# perspection-v1.net
KiCad netlist of a schematic drawn in EAGLE
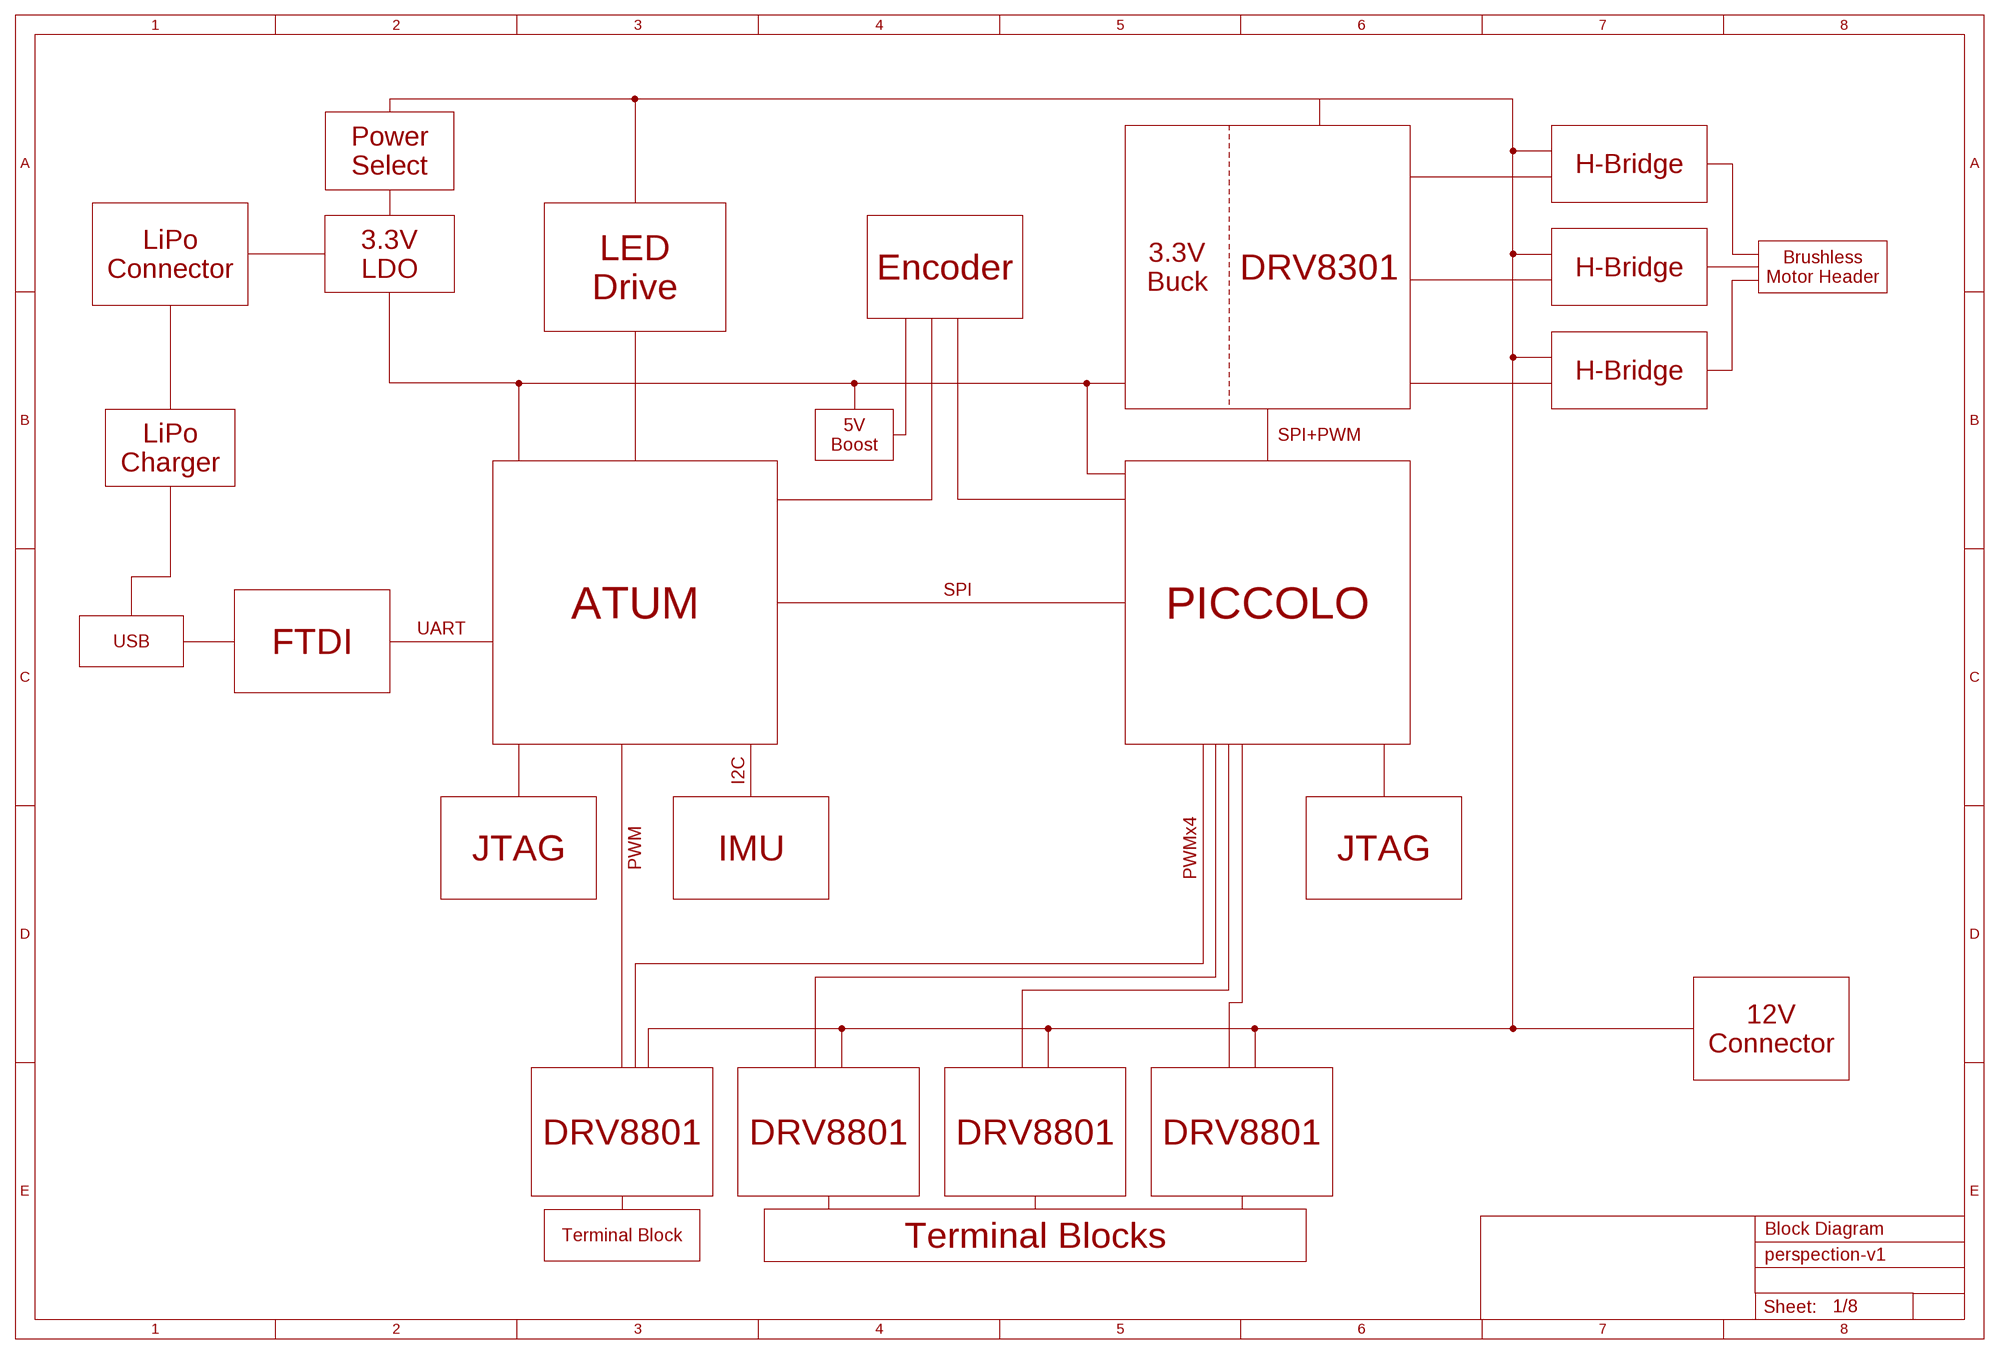
[diagram p0: schematic, sheet 1]
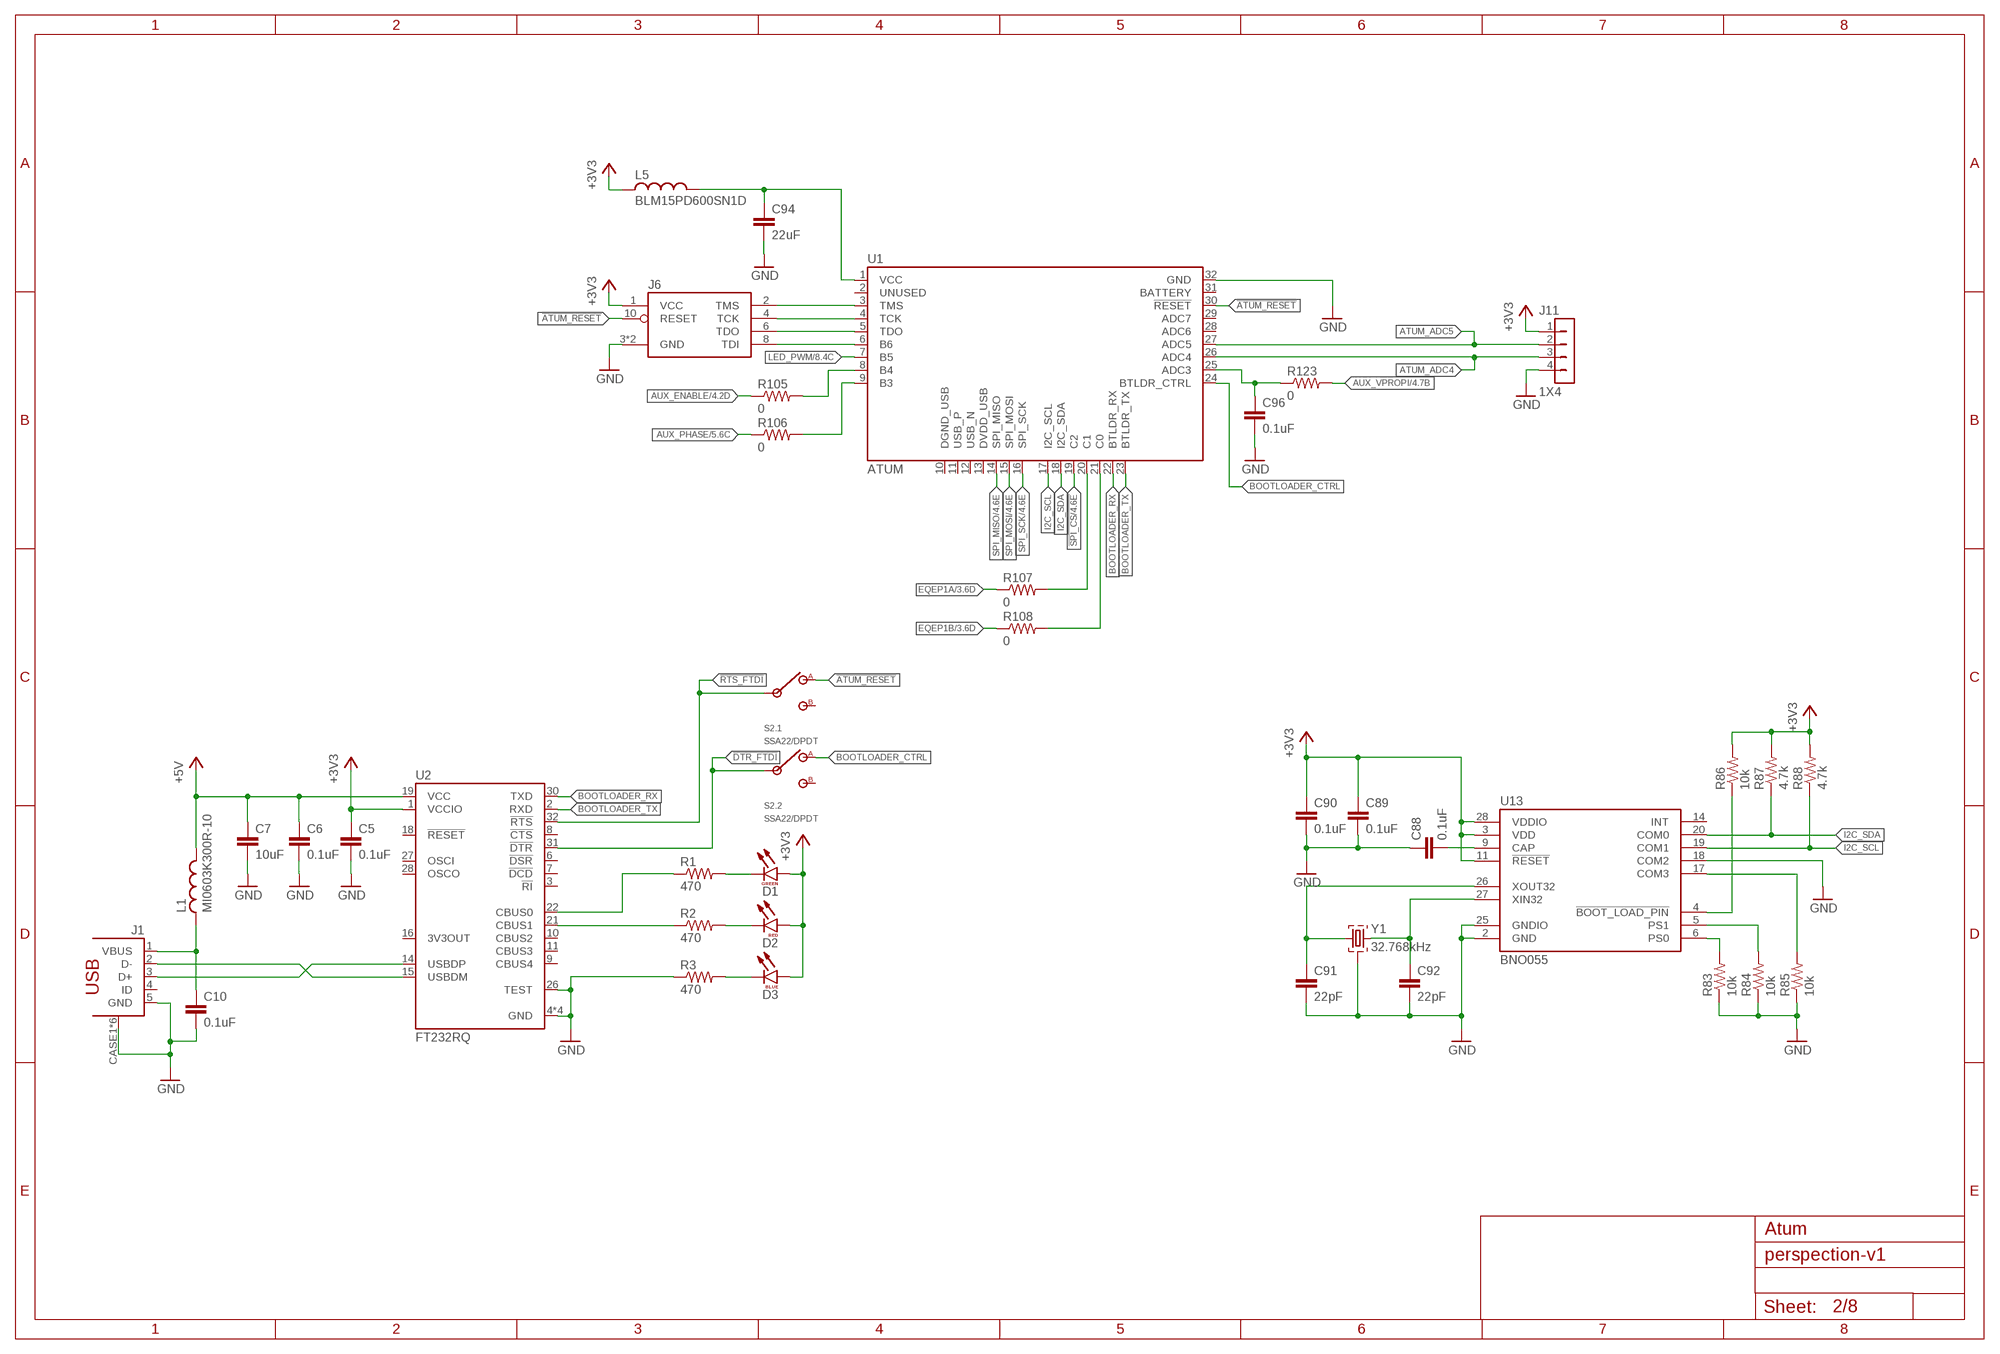
[diagram p1: schematic, sheet 2]
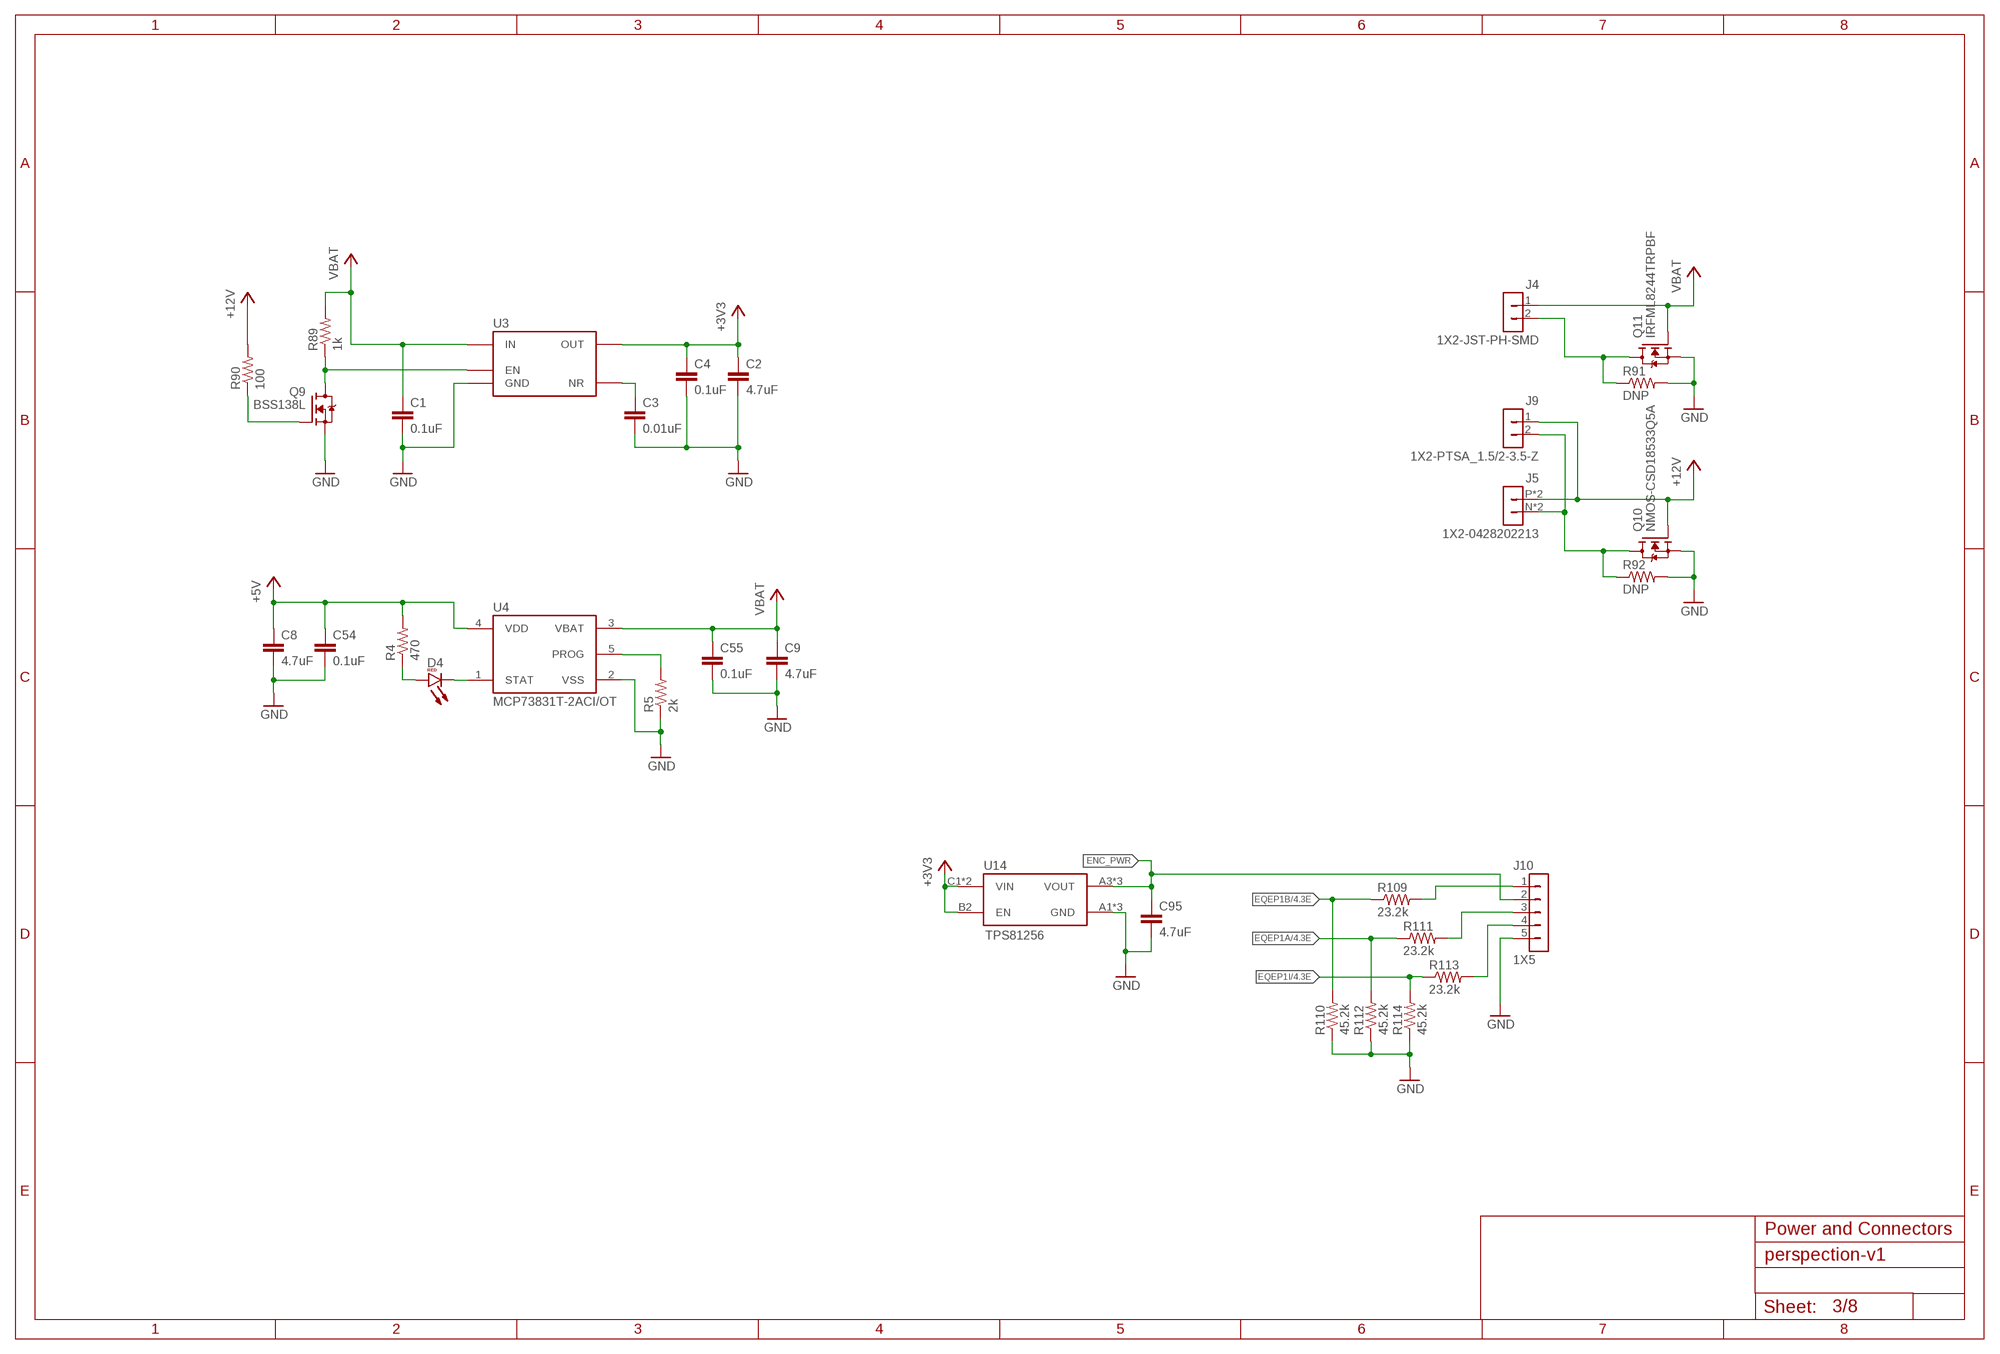
[diagram p2: schematic, sheet 3]
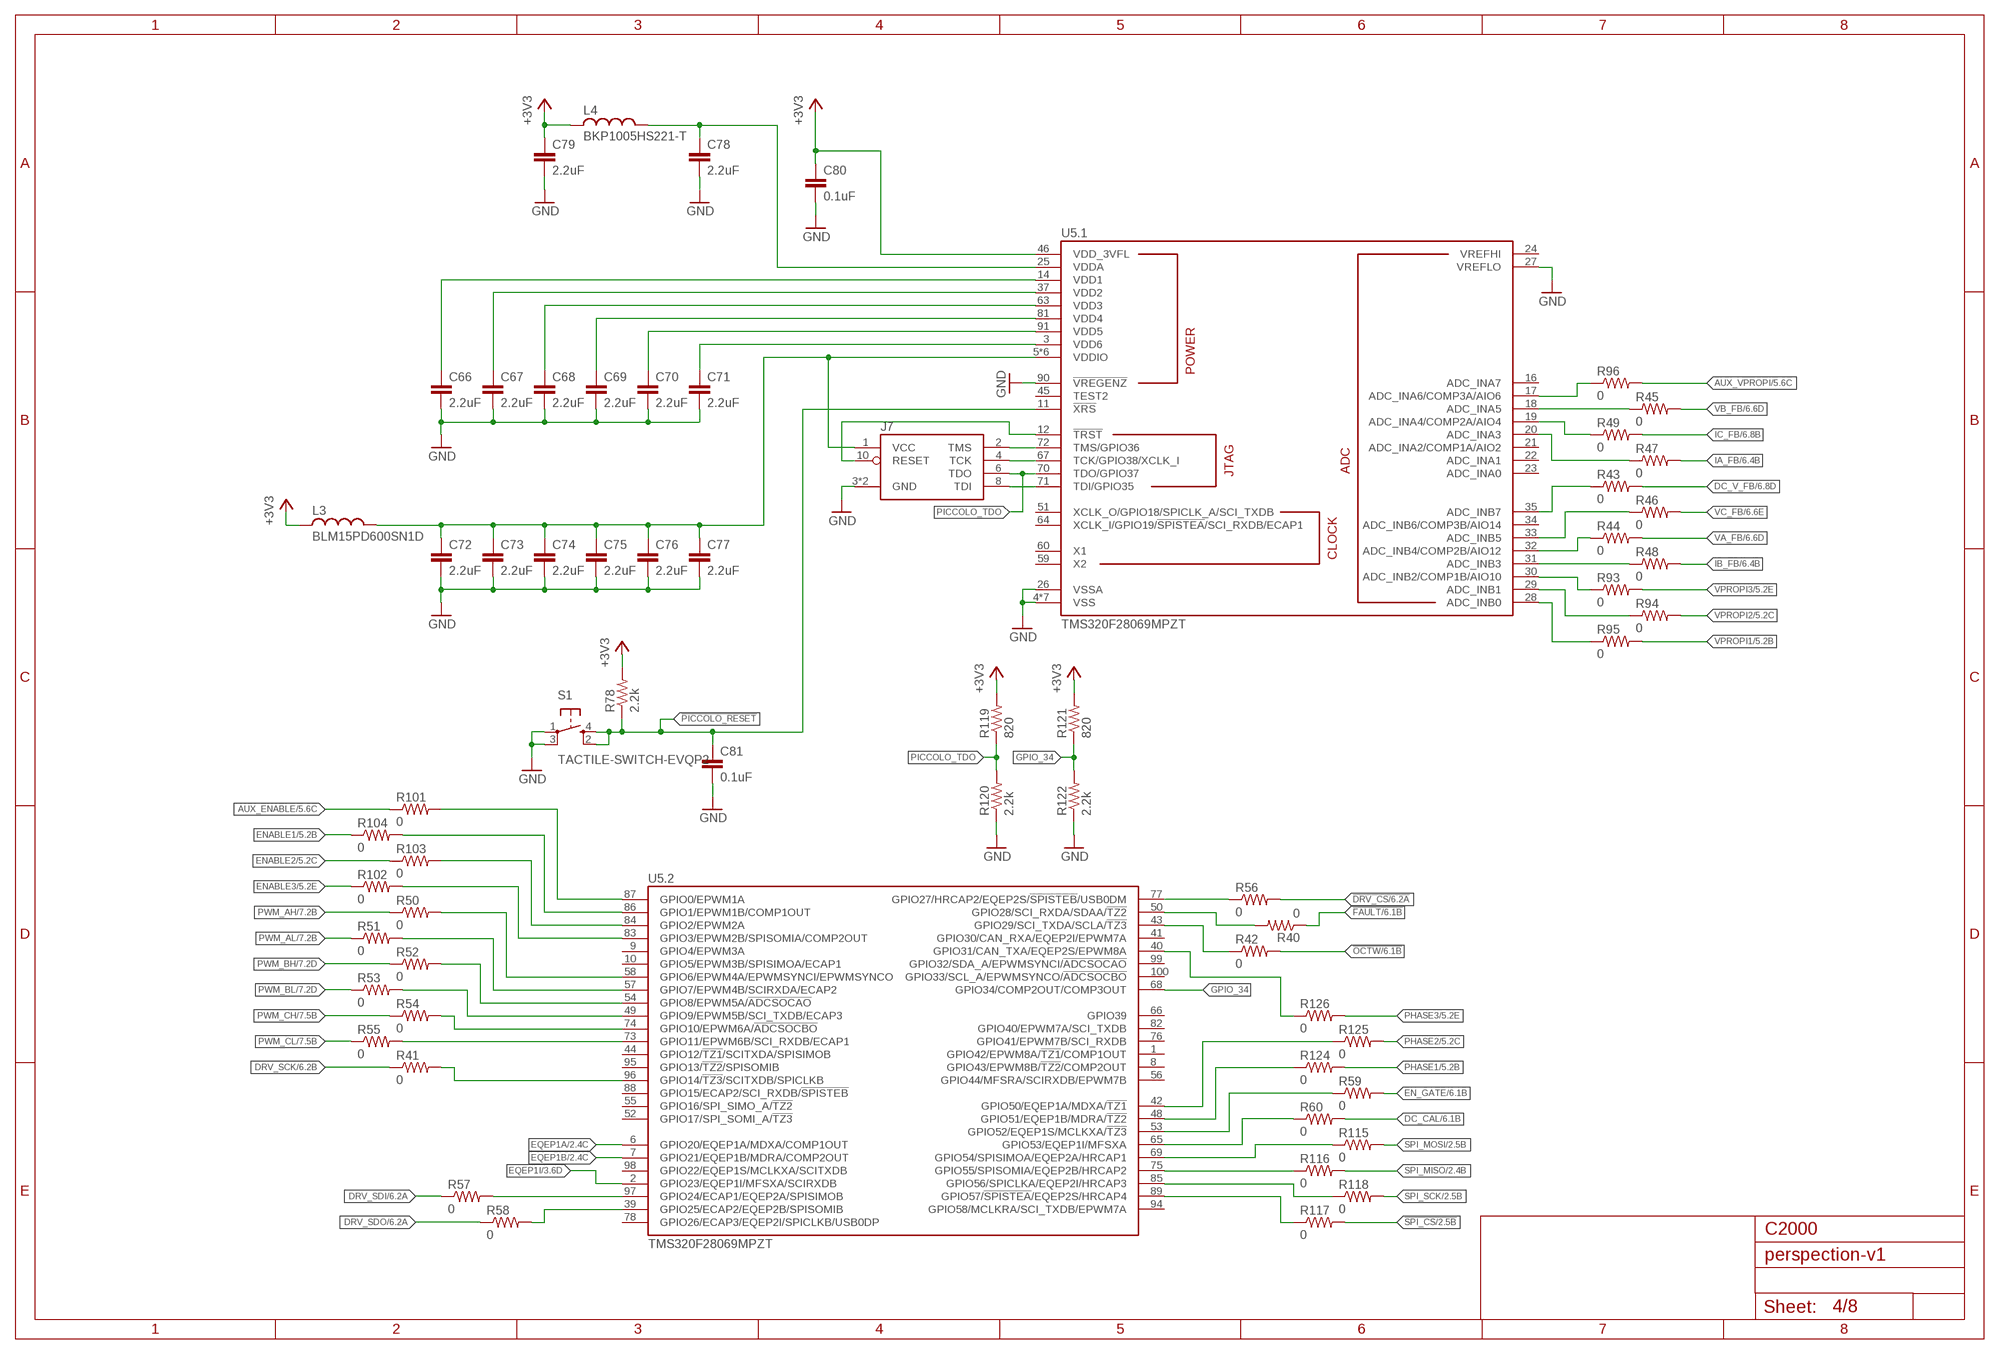
[diagram p3: schematic, sheet 4]
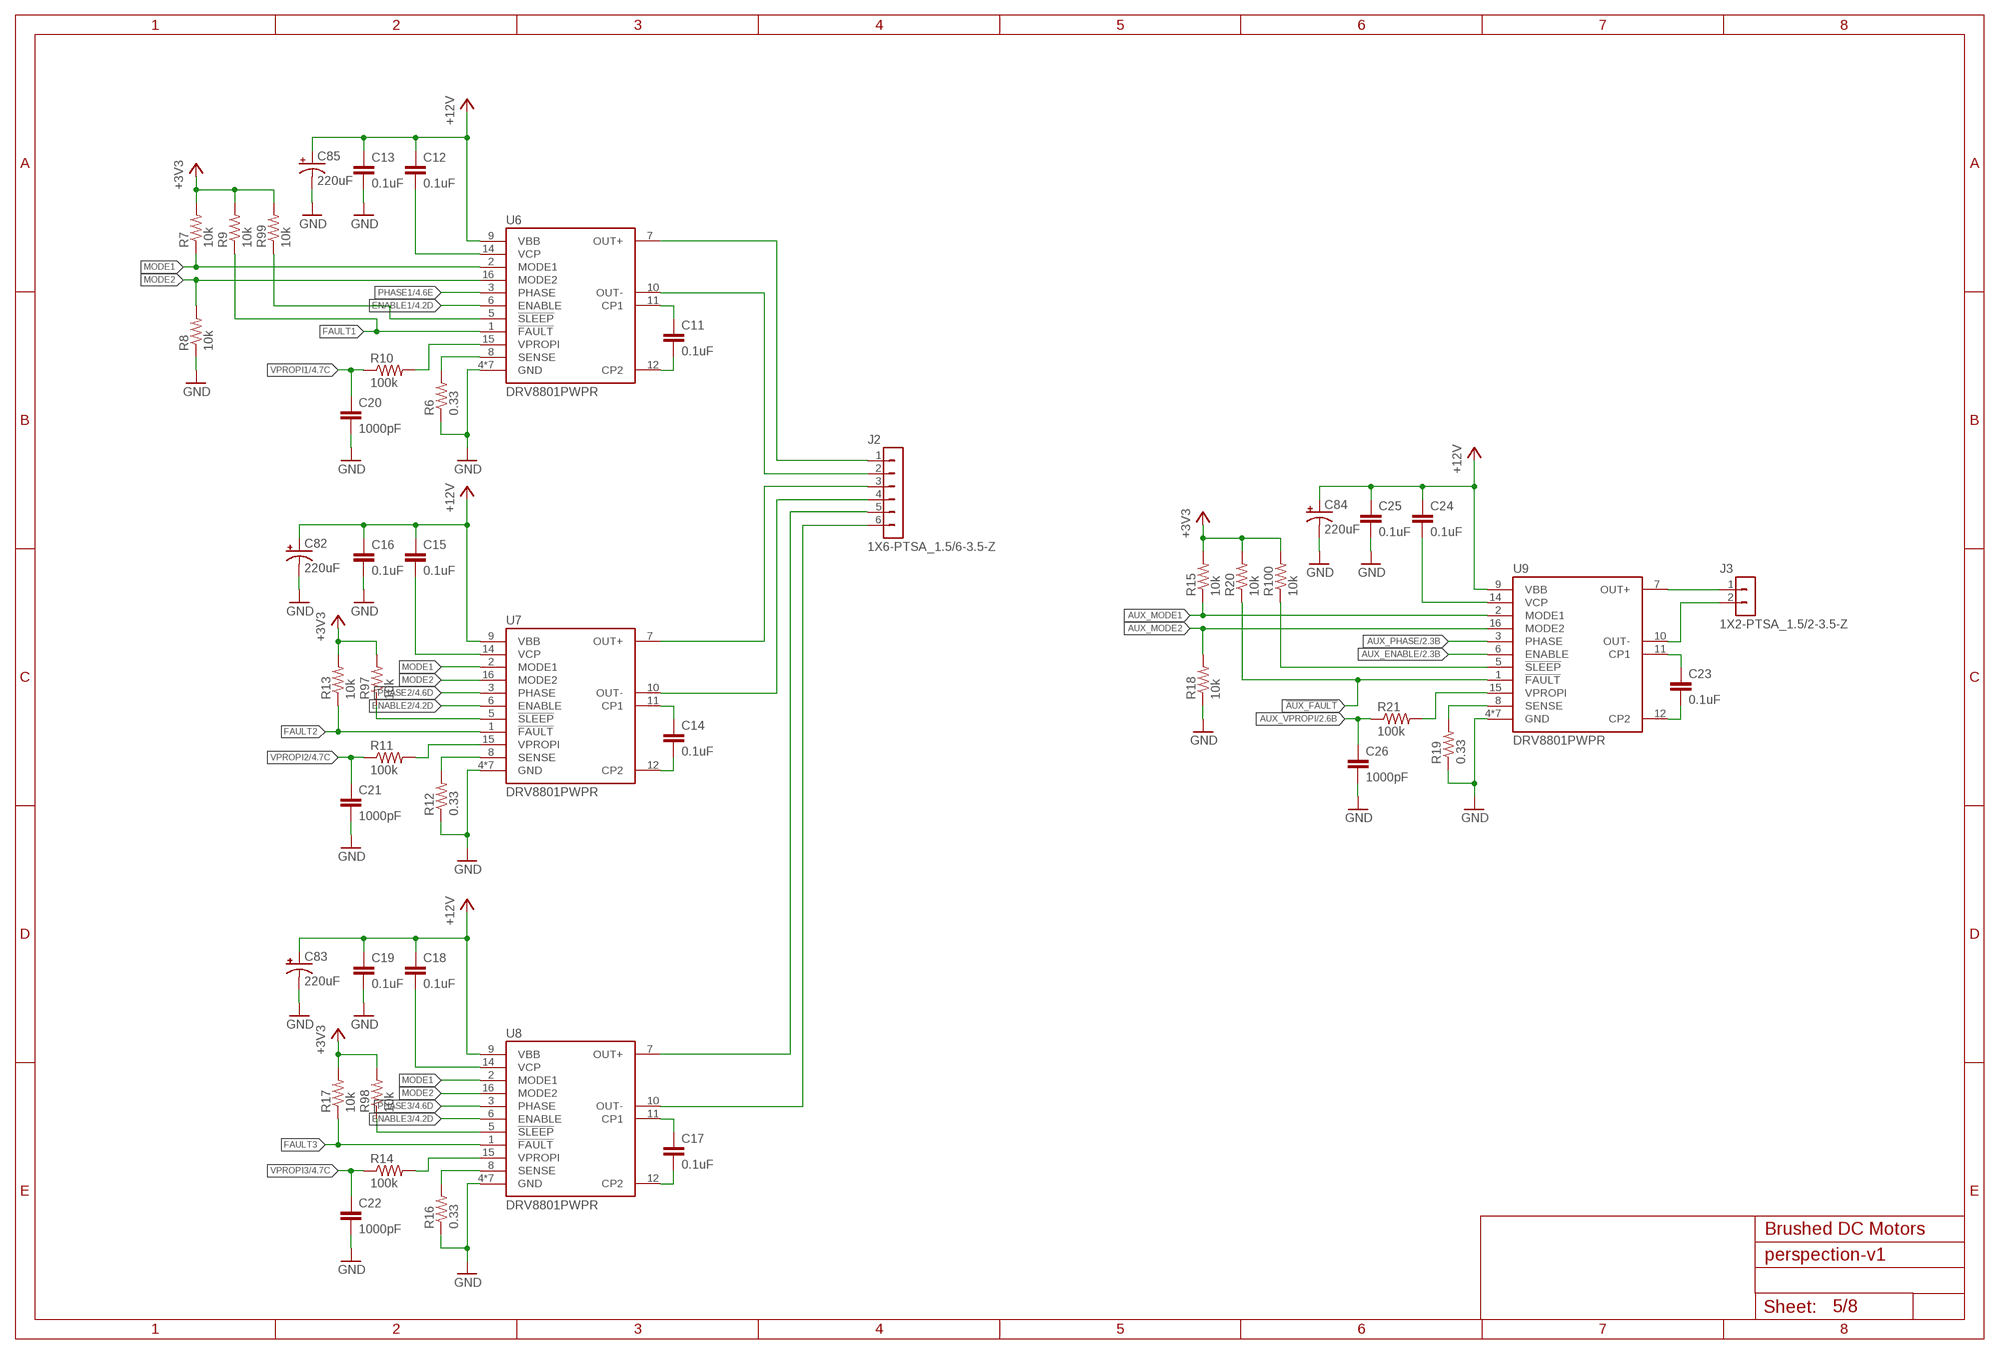
[diagram p4: schematic, sheet 5]
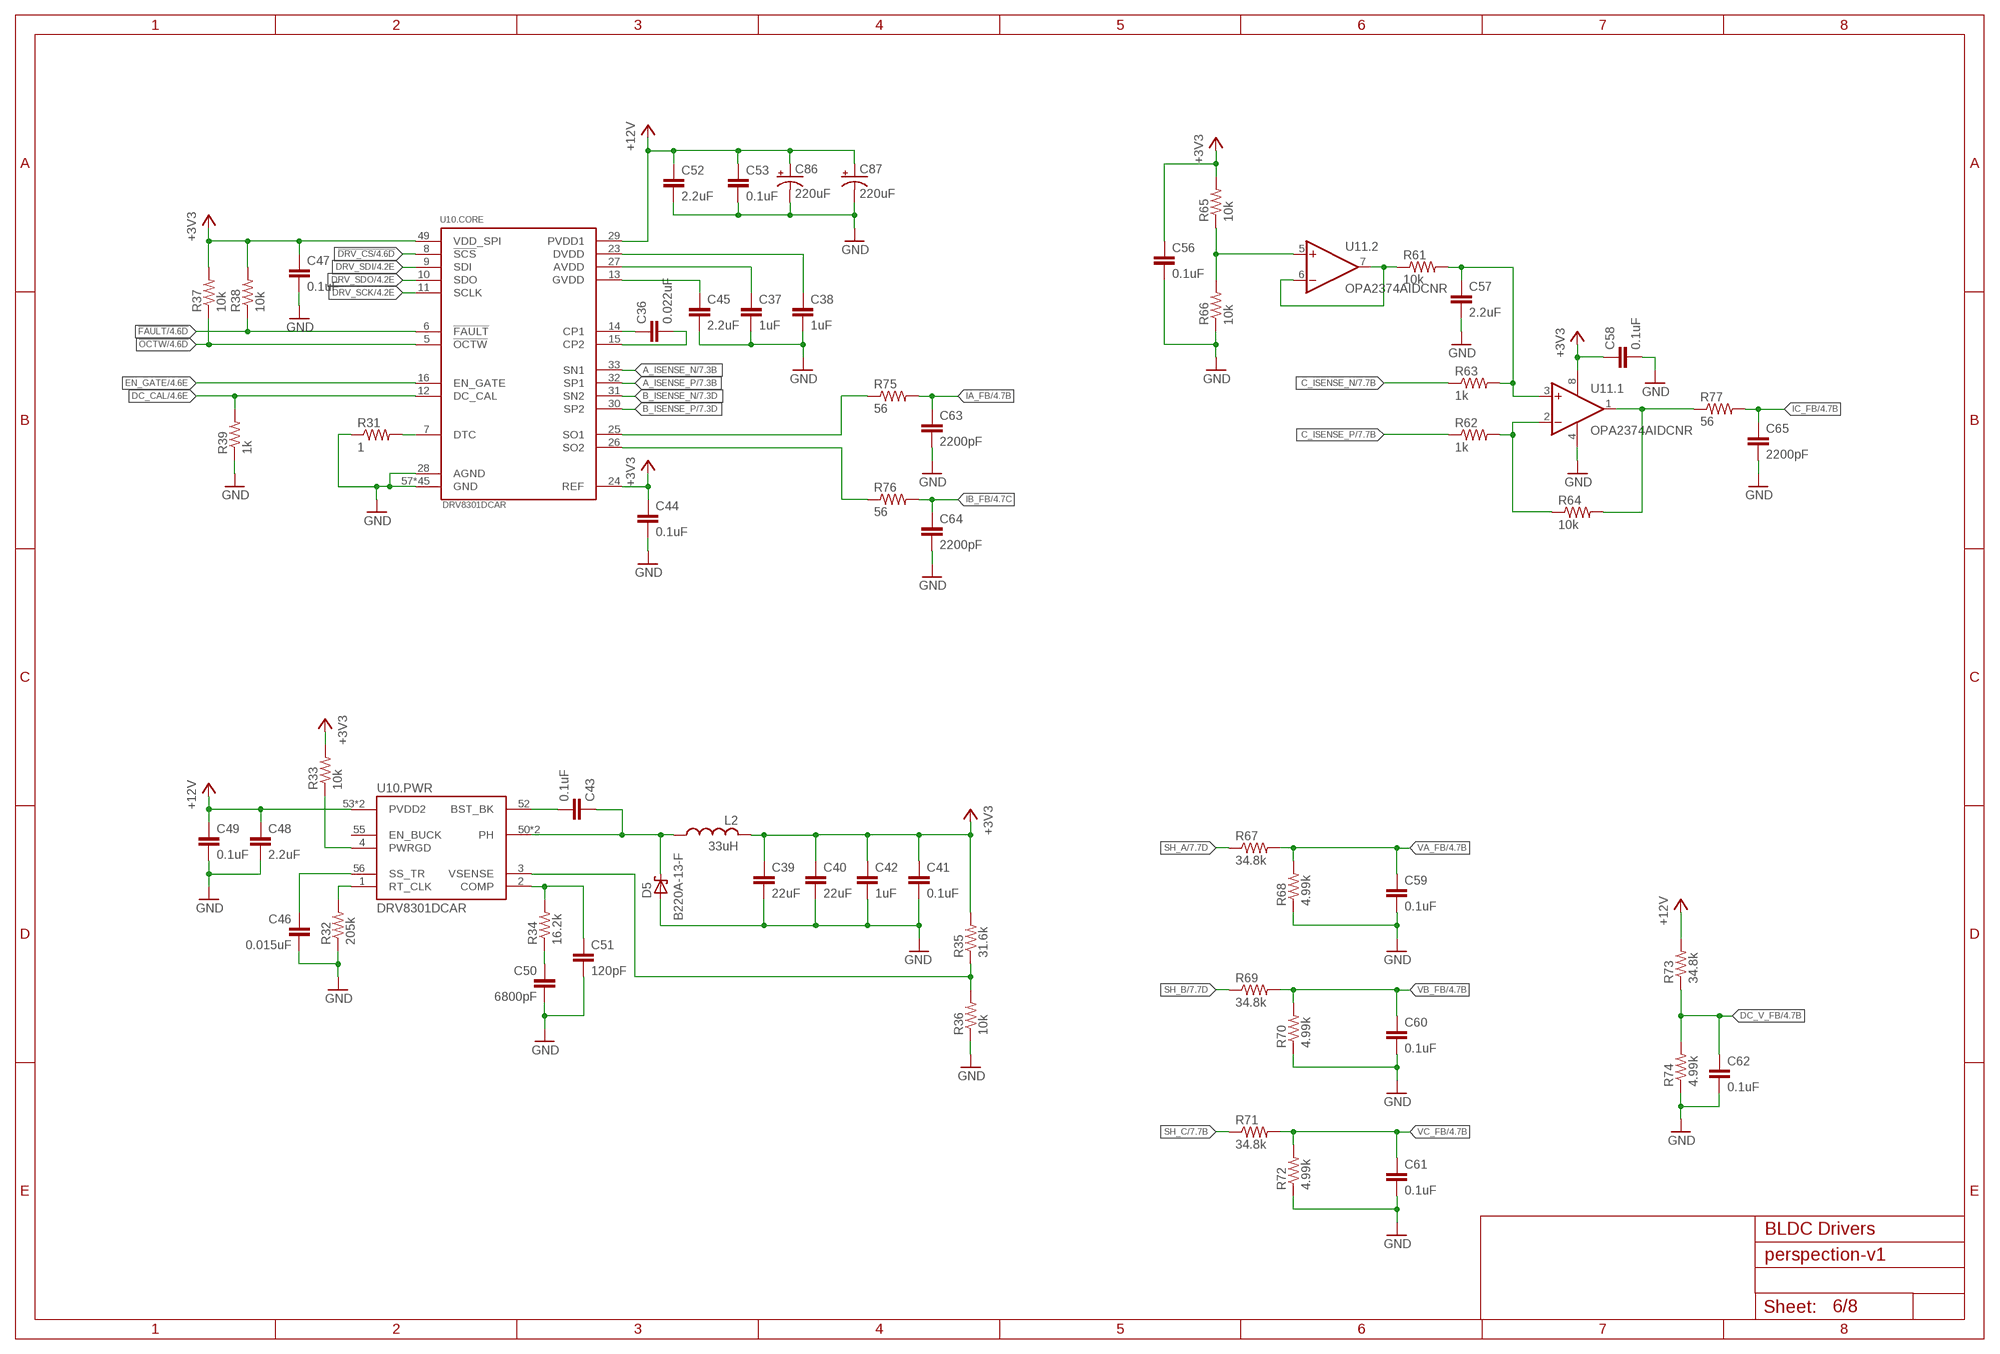
[diagram p5: schematic, sheet 6]
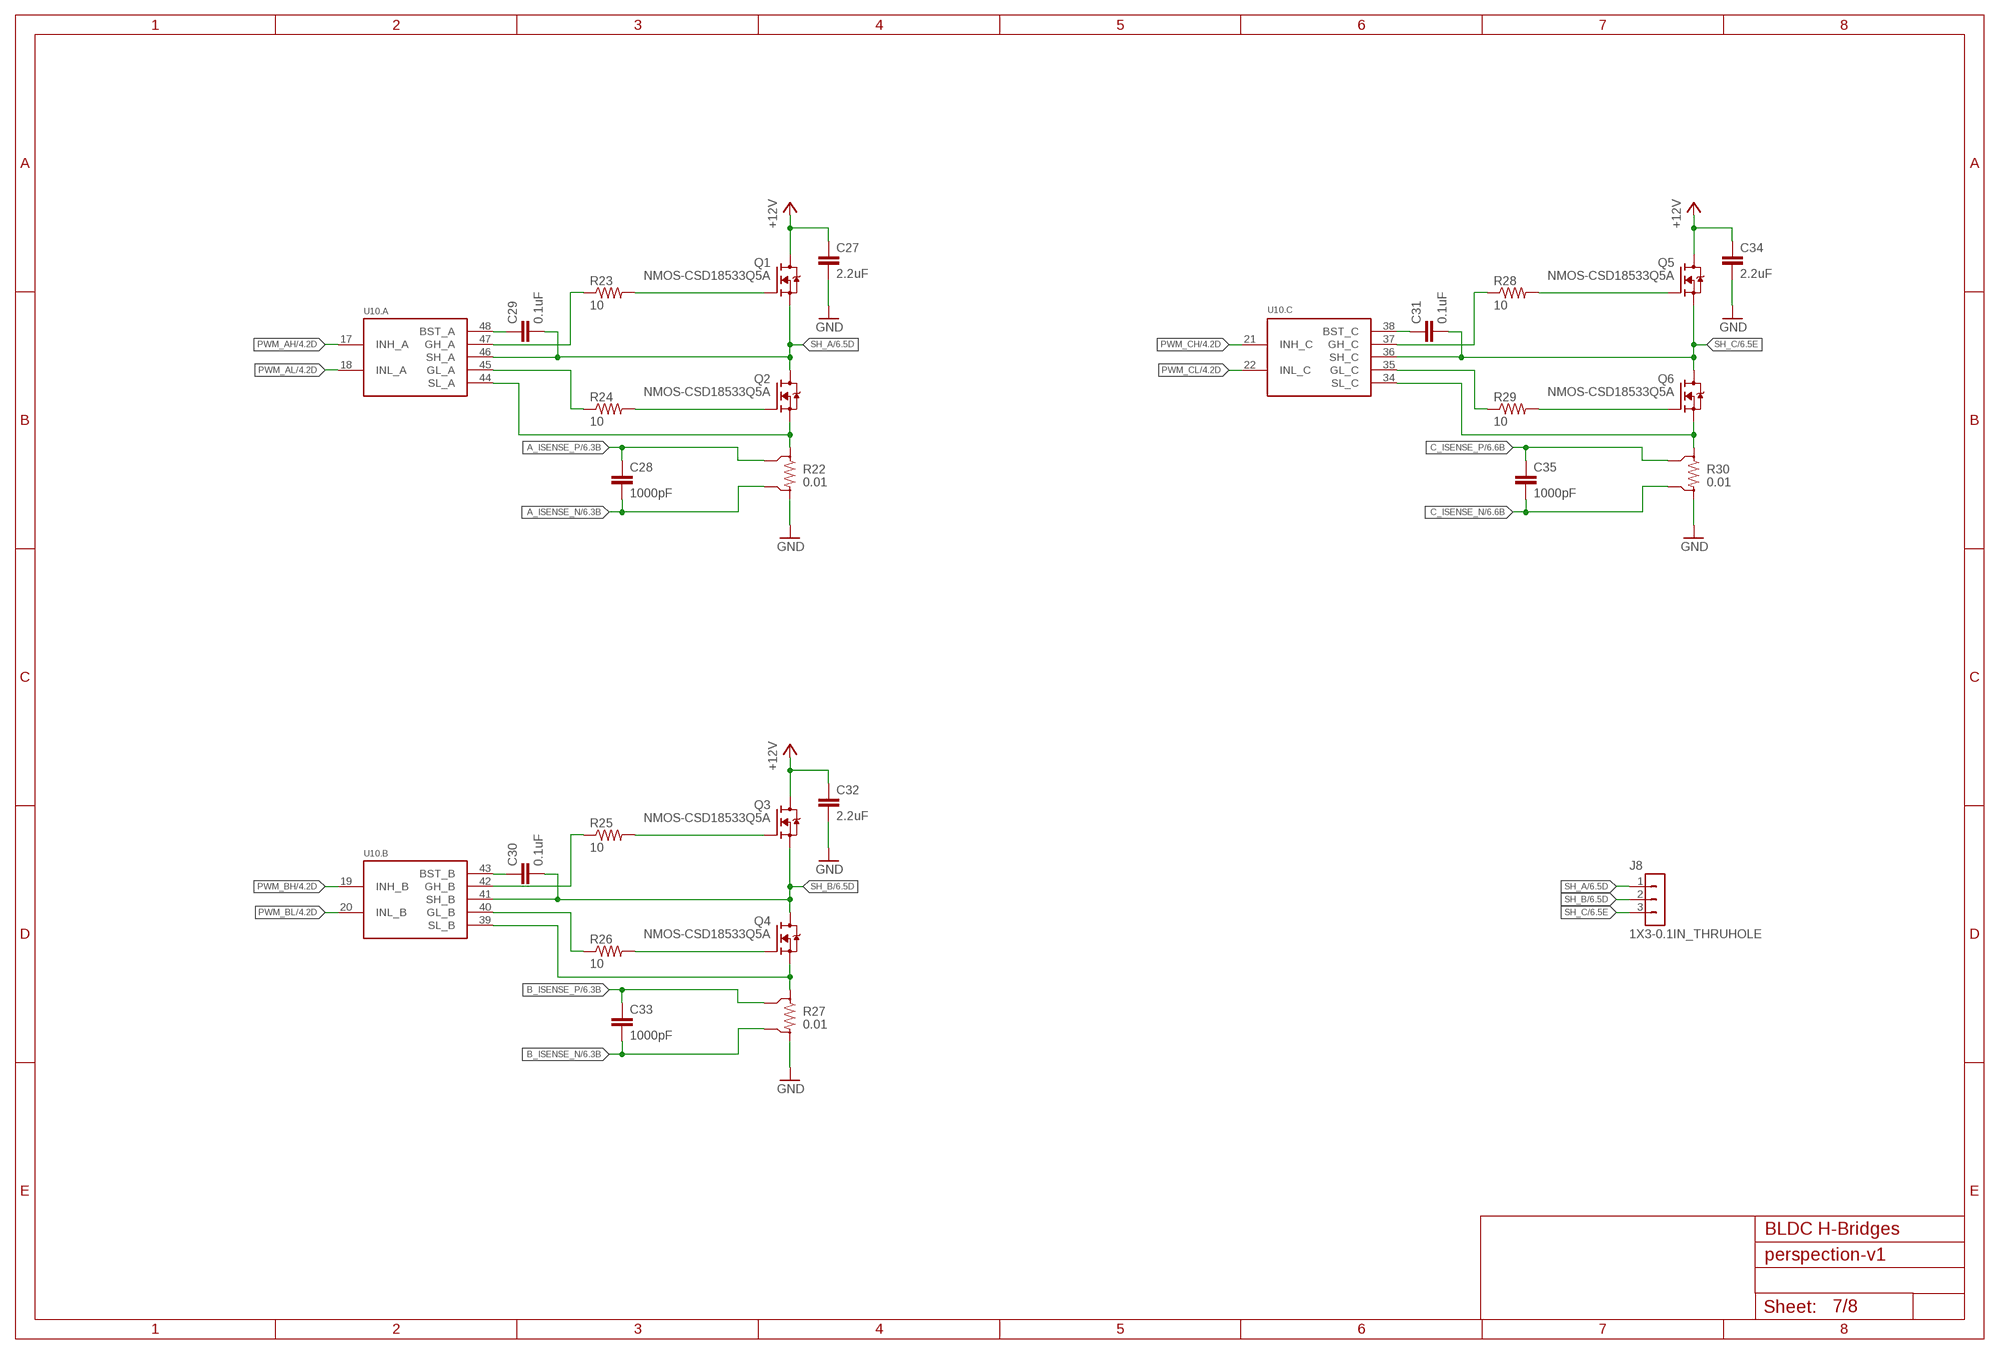
[diagram p6: schematic, sheet 7]
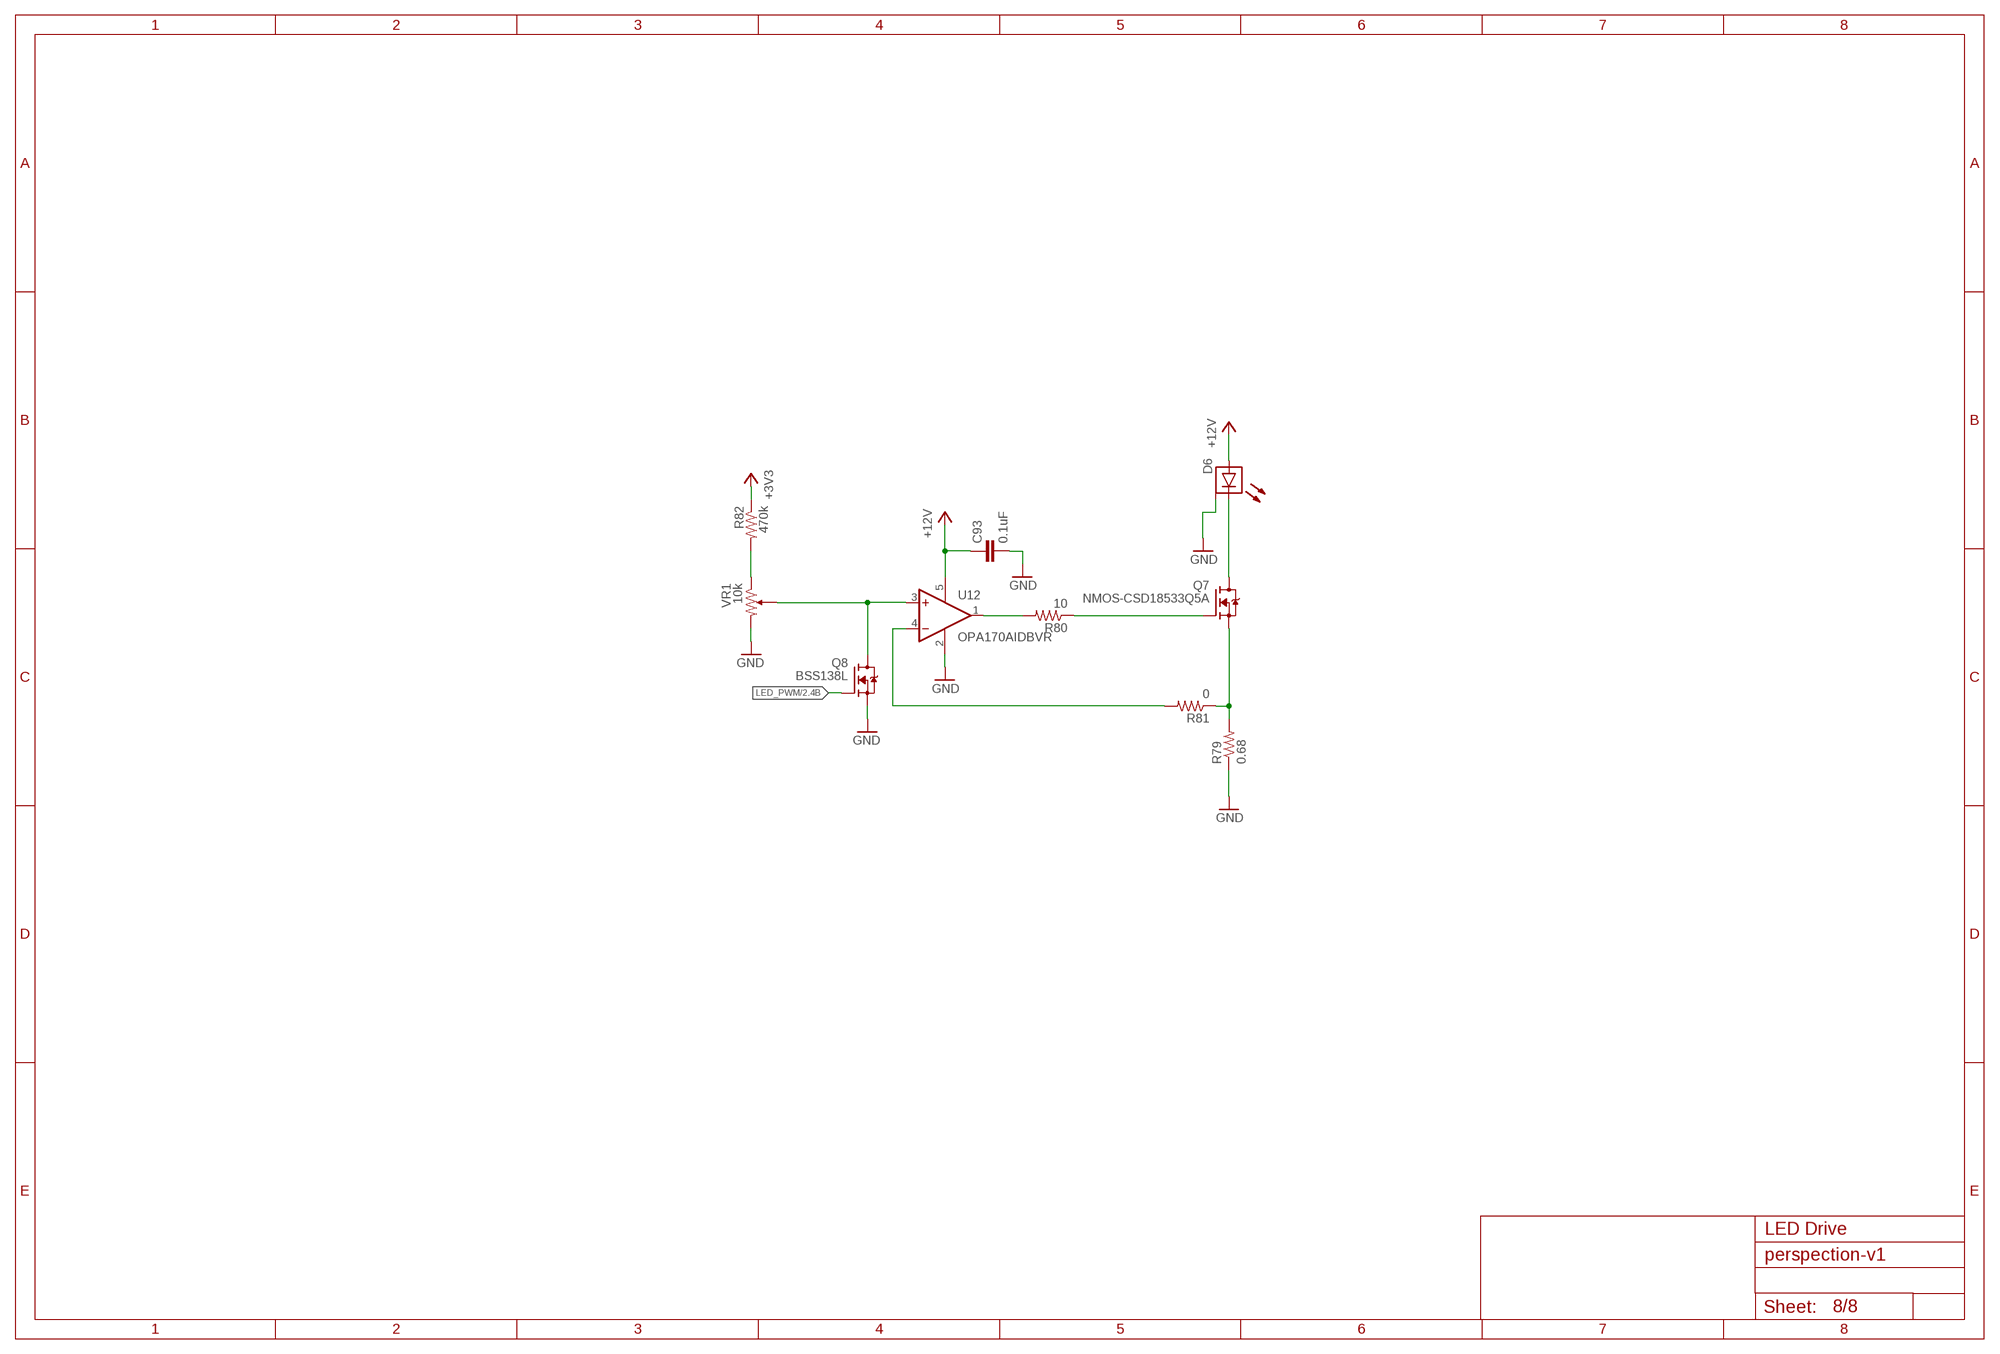
[diagram p7: schematic, sheet 8]

(export (version "E")
  (design (tool "Eeschema 10.0.6"))
  (components
    (comp (ref "C5")
      (value "0.1uF")
      (footprint "eagle-import:C0402")
      (libsource (lib "eagle-import") (part "C0402"))
    )
    (comp (ref "C6")
      (value "0.1uF")
      (footprint "eagle-import:C0402")
      (libsource (lib "eagle-import") (part "C0402"))
    )
    (comp (ref "C7")
      (value "10uF")
      (footprint "eagle-import:C1206")
      (libsource (lib "eagle-import") (part "C1206"))
    )
    (comp (ref "C10")
      (value "0.1uF")
      (footprint "eagle-import:C0402")
      (libsource (lib "eagle-import") (part "C0402"))
    )
    (comp (ref "C88")
      (value "0.1uF")
      (footprint "eagle-import:C0402")
      (libsource (lib "eagle-import") (part "C0402"))
    )
    (comp (ref "C89")
      (value "0.1uF")
      (footprint "eagle-import:C0402")
      (libsource (lib "eagle-import") (part "C0402"))
    )
    (comp (ref "C90")
      (value "0.1uF")
      (footprint "eagle-import:C0402")
      (libsource (lib "eagle-import") (part "C0402"))
    )
    (comp (ref "C91")
      (value "22pF")
      (footprint "eagle-import:C0402")
      (libsource (lib "eagle-import") (part "C0402"))
    )
    (comp (ref "C92")
      (value "22pF")
      (footprint "eagle-import:C0402")
      (libsource (lib "eagle-import") (part "C0402"))
    )
    (comp (ref "C94")
      (value "22uF")
      (footprint "eagle-import:C1206")
      (libsource (lib "eagle-import") (part "C1206"))
    )
    (comp (ref "C96")
      (value "0.1uF")
      (footprint "eagle-import:C0402")
      (libsource (lib "eagle-import") (part "C0402"))
    )
    (comp (ref "D1")
      (value "LED0603")
      (footprint "eagle-import:LED0603")
      (fields (field (name "COLOR") "GREEN"))
      (libsource (lib "eagle-import") (part "LED0603"))
    )
    (comp (ref "D2")
      (value "LED0603")
      (footprint "eagle-import:LED0603")
      (fields (field (name "COLOR") "RED"))
      (libsource (lib "eagle-import") (part "LED0603"))
    )
    (comp (ref "D3")
      (value "LED0603")
      (footprint "eagle-import:LED0603")
      (fields (field (name "COLOR") "BLUE"))
      (libsource (lib "eagle-import") (part "LED0603"))
    )
    (comp (ref "J1")
      (value "MICRO-USB-10118192-0001LF")
      (footprint "eagle-import:MICRO-USB")
      (libsource (lib "eagle-import") (part "MICRO-USB-10118192-0001LF"))
    )
    (comp (ref "J6")
      (value "JTAG-ARM_TC-10")
      (footprint "eagle-import:TC2050-IDC")
      (libsource (lib "eagle-import") (part "JTAG-ARM_TC-10"))
    )
    (comp (ref "J11")
      (value "1X4")
      (footprint "eagle-import:1X4_0.1IN_THRUHOLE")
      (libsource (lib "eagle-import") (part "1X4"))
    )
    (comp (ref "L1")
      (value "MI0603K300R-10")
      (footprint "eagle-import:L0603")
      (fields
        (field (name "DIST_NAME") "Digi-key")
        (field (name "DIST_PN") "240-2373-1-ND")
        (field (name "MFG_NAME") "Laird-Signal Integrity Products")
        (field (name "MFG_PN") "MI0603K300R-10")
      )
      (libsource (lib "eagle-import") (part "L0603"))
    )
    (comp (ref "L5")
      (value "BLM15PD600SN1D")
      (footprint "eagle-import:L0402")
      (fields
        (field (name "DIST_NAME") "Digi-key")
        (field (name "DIST_PN") "490-5201-1-ND")
        (field (name "MFG_NAME") "Murata Electronics North America")
        (field (name "MFG_PN") "BLM15PD600SN1D")
      )
      (libsource (lib "eagle-import") (part "L0402"))
    )
    (comp (ref "R1")
      (value "470")
      (footprint "eagle-import:R0402")
      (libsource (lib "eagle-import") (part "R0402"))
    )
    (comp (ref "R2")
      (value "470")
      (footprint "eagle-import:R0402")
      (libsource (lib "eagle-import") (part "R0402"))
    )
    (comp (ref "R3")
      (value "470")
      (footprint "eagle-import:R0402")
      (libsource (lib "eagle-import") (part "R0402"))
    )
    (comp (ref "R83")
      (value "10k")
      (footprint "eagle-import:R0402")
      (libsource (lib "eagle-import") (part "R0402"))
    )
    (comp (ref "R84")
      (value "10k")
      (footprint "eagle-import:R0402")
      (libsource (lib "eagle-import") (part "R0402"))
    )
    (comp (ref "R85")
      (value "10k")
      (footprint "eagle-import:R0402")
      (libsource (lib "eagle-import") (part "R0402"))
    )
    (comp (ref "R86")
      (value "10k")
      (footprint "eagle-import:R0402")
      (libsource (lib "eagle-import") (part "R0402"))
    )
    (comp (ref "R87")
      (value "4.7k")
      (footprint "eagle-import:R0402")
      (libsource (lib "eagle-import") (part "R0402"))
    )
    (comp (ref "R88")
      (value "4.7k")
      (footprint "eagle-import:R0402")
      (libsource (lib "eagle-import") (part "R0402"))
    )
    (comp (ref "R105")
      (value "0")
      (footprint "eagle-import:R0402")
      (libsource (lib "eagle-import") (part "R0402"))
    )
    (comp (ref "R106")
      (value "0")
      (footprint "eagle-import:R0402")
      (libsource (lib "eagle-import") (part "R0402"))
    )
    (comp (ref "R107")
      (value "0")
      (footprint "eagle-import:R0402")
      (libsource (lib "eagle-import") (part "R0402"))
    )
    (comp (ref "R108")
      (value "0")
      (footprint "eagle-import:R0402")
      (libsource (lib "eagle-import") (part "R0402"))
    )
    (comp (ref "R123")
      (value "0")
      (footprint "eagle-import:R0402")
      (libsource (lib "eagle-import") (part "R0402"))
    )
    (comp (ref "S2")
      (value "SSA22/DPDT")
      (footprint "eagle-import:SSA22_DPDT")
      (libsource (lib "eagle-import") (part "SSA22/DPDT"))
    )
    (comp (ref "U1")
      (value "ATUM")
      (footprint "eagle-import:ATUM")
      (libsource (lib "eagle-import") (part "ATUM"))
    )
    (comp (ref "U2")
      (value "FT232RQ")
      (footprint "eagle-import:QFN32")
      (libsource (lib "eagle-import") (part "FT232RQ"))
    )
    (comp (ref "U13")
      (value "BNO055")
      (footprint "eagle-import:LGA-28")
      (libsource (lib "eagle-import") (part "BNO055"))
    )
    (comp (ref "Y1")
      (value "32.768kHz")
      (footprint "eagle-import:SOJ-4")
      (libsource (lib "eagle-import") (part "CM200C32768HZFT"))
    )
    (comp (ref "C11")
      (value "0.1uF")
      (footprint "eagle-import:C0402")
      (libsource (lib "eagle-import") (part "C0402"))
    )
    (comp (ref "C12")
      (value "0.1uF")
      (footprint "eagle-import:C0402")
      (libsource (lib "eagle-import") (part "C0402"))
    )
    (comp (ref "C13")
      (value "0.1uF")
      (footprint "eagle-import:C0402")
      (libsource (lib "eagle-import") (part "C0402"))
    )
    (comp (ref "C14")
      (value "0.1uF")
      (footprint "eagle-import:C0402")
      (libsource (lib "eagle-import") (part "C0402"))
    )
    (comp (ref "C15")
      (value "0.1uF")
      (footprint "eagle-import:C0402")
      (libsource (lib "eagle-import") (part "C0402"))
    )
    (comp (ref "C16")
      (value "0.1uF")
      (footprint "eagle-import:C0402")
      (libsource (lib "eagle-import") (part "C0402"))
    )
    (comp (ref "C17")
      (value "0.1uF")
      (footprint "eagle-import:C0402")
      (libsource (lib "eagle-import") (part "C0402"))
    )
    (comp (ref "C18")
      (value "0.1uF")
      (footprint "eagle-import:C0402")
      (libsource (lib "eagle-import") (part "C0402"))
    )
    (comp (ref "C19")
      (value "0.1uF")
      (footprint "eagle-import:C0402")
      (libsource (lib "eagle-import") (part "C0402"))
    )
    (comp (ref "C20")
      (value "1000pF")
      (footprint "eagle-import:C0402")
      (libsource (lib "eagle-import") (part "C0402"))
    )
    (comp (ref "C21")
      (value "1000pF")
      (footprint "eagle-import:C0402")
      (libsource (lib "eagle-import") (part "C0402"))
    )
    (comp (ref "C22")
      (value "1000pF")
      (footprint "eagle-import:C0402")
      (libsource (lib "eagle-import") (part "C0402"))
    )
    (comp (ref "C23")
      (value "0.1uF")
      (footprint "eagle-import:C0402")
      (libsource (lib "eagle-import") (part "C0402"))
    )
    (comp (ref "C24")
      (value "0.1uF")
      (footprint "eagle-import:C0402")
      (libsource (lib "eagle-import") (part "C0402"))
    )
    (comp (ref "C25")
      (value "0.1uF")
      (footprint "eagle-import:C0402")
      (libsource (lib "eagle-import") (part "C0402"))
    )
    (comp (ref "C26")
      (value "1000pF")
      (footprint "eagle-import:C0402")
      (libsource (lib "eagle-import") (part "C0402"))
    )
    (comp (ref "C82")
      (value "220uF")
      (footprint "eagle-import:PANASONIC-6.3MM-SMD")
      (libsource (lib "eagle-import") (part "CPOL-PANASONIC-6.3MM-SMD-220UF-25V"))
    )
    (comp (ref "C83")
      (value "220uF")
      (footprint "eagle-import:PANASONIC-6.3MM-SMD")
      (libsource (lib "eagle-import") (part "CPOL-PANASONIC-6.3MM-SMD-220UF-25V"))
    )
    (comp (ref "C84")
      (value "220uF")
      (footprint "eagle-import:PANASONIC-6.3MM-SMD")
      (libsource (lib "eagle-import") (part "CPOL-PANASONIC-6.3MM-SMD-220UF-25V"))
    )
    (comp (ref "C85")
      (value "220uF")
      (footprint "eagle-import:PANASONIC-6.3MM-SMD")
      (libsource (lib "eagle-import") (part "CPOL-PANASONIC-6.3MM-SMD-220UF-25V"))
    )
    (comp (ref "J2")
      (value "1X6-PTSA_1.5/6-3.5-Z")
      (footprint "eagle-import:3.5MM_PTSA_1.5_6-3.5-Z")
      (libsource (lib "eagle-import") (part "1X6-PTSA_1.5/6-3.5-Z"))
    )
    (comp (ref "J3")
      (value "1X2-PTSA_1.5/2-3.5-Z")
      (footprint "eagle-import:3.5MM_PTSA_1.5_2-3.5-Z")
      (libsource (lib "eagle-import") (part "1X2-PTSA_1.5/2-3.5-Z"))
    )
    (comp (ref "R6")
      (value "0.33")
      (footprint "eagle-import:R1206")
      (fields
        (field (name "DIST_NAME") "Digi-key")
        (field (name "DIST_PN") "1276-6179-1-ND")
        (field (name "MFG_NAME") "Samsung Electro-Mechanics America, Inc.")
        (field (name "MFG_PN") "RUT3216FR330CS")
      )
      (libsource (lib "eagle-import") (part "R1206"))
    )
    (comp (ref "R7")
      (value "10k")
      (footprint "eagle-import:R0402")
      (libsource (lib "eagle-import") (part "R0402"))
    )
    (comp (ref "R8")
      (value "10k")
      (footprint "eagle-import:R0402")
      (libsource (lib "eagle-import") (part "R0402"))
    )
    (comp (ref "R9")
      (value "10k")
      (footprint "eagle-import:R0402")
      (libsource (lib "eagle-import") (part "R0402"))
    )
    (comp (ref "R10")
      (value "100k")
      (footprint "eagle-import:R0402")
      (libsource (lib "eagle-import") (part "R0402"))
    )
    (comp (ref "R11")
      (value "100k")
      (footprint "eagle-import:R0402")
      (libsource (lib "eagle-import") (part "R0402"))
    )
    (comp (ref "R12")
      (value "0.33")
      (footprint "eagle-import:R1206")
      (fields
        (field (name "DIST_NAME") "Digi-key")
        (field (name "DIST_PN") "1276-6179-1-ND")
        (field (name "MFG_NAME") "Samsung Electro-Mechanics America, Inc.")
        (field (name "MFG_PN") "RUT3216FR330CS")
      )
      (libsource (lib "eagle-import") (part "R1206"))
    )
    (comp (ref "R13")
      (value "10k")
      (footprint "eagle-import:R0402")
      (libsource (lib "eagle-import") (part "R0402"))
    )
    (comp (ref "R14")
      (value "100k")
      (footprint "eagle-import:R0402")
      (libsource (lib "eagle-import") (part "R0402"))
    )
    (comp (ref "R15")
      (value "10k")
      (footprint "eagle-import:R0402")
      (libsource (lib "eagle-import") (part "R0402"))
    )
    (comp (ref "R16")
      (value "0.33")
      (footprint "eagle-import:R1206")
      (fields
        (field (name "DIST_NAME") "Digi-key")
        (field (name "DIST_PN") "1276-6179-1-ND")
        (field (name "MFG_NAME") "Samsung Electro-Mechanics America, Inc.")
        (field (name "MFG_PN") "RUT3216FR330CS")
      )
      (libsource (lib "eagle-import") (part "R1206"))
    )
    (comp (ref "R17")
      (value "10k")
      (footprint "eagle-import:R0402")
      (libsource (lib "eagle-import") (part "R0402"))
    )
    (comp (ref "R18")
      (value "10k")
      (footprint "eagle-import:R0402")
      (libsource (lib "eagle-import") (part "R0402"))
    )
    (comp (ref "R19")
      (value "0.33")
      (footprint "eagle-import:R1206")
      (fields
        (field (name "DIST_NAME") "Digi-key")
        (field (name "DIST_PN") "1276-6179-1-ND")
        (field (name "MFG_NAME") "Samsung Electro-Mechanics America, Inc.")
        (field (name "MFG_PN") "RUT3216FR330CS")
      )
      (libsource (lib "eagle-import") (part "R1206"))
    )
    (comp (ref "R20")
      (value "10k")
      (footprint "eagle-import:R0402")
      (libsource (lib "eagle-import") (part "R0402"))
    )
    (comp (ref "R21")
      (value "100k")
      (footprint "eagle-import:R0402")
      (libsource (lib "eagle-import") (part "R0402"))
    )
    (comp (ref "R97")
      (value "10k")
      (footprint "eagle-import:R0402")
      (libsource (lib "eagle-import") (part "R0402"))
    )
    (comp (ref "R98")
      (value "10k")
      (footprint "eagle-import:R0402")
      (libsource (lib "eagle-import") (part "R0402"))
    )
    (comp (ref "R99")
      (value "10k")
      (footprint "eagle-import:R0402")
      (libsource (lib "eagle-import") (part "R0402"))
    )
    (comp (ref "R100")
      (value "10k")
      (footprint "eagle-import:R0402")
      (libsource (lib "eagle-import") (part "R0402"))
    )
    (comp (ref "U6")
      (value "DRV8801PWPR")
      (footprint "eagle-import:TI-HTSSOP-16")
      (libsource (lib "eagle-import") (part "DRV8801PWPR"))
    )
    (comp (ref "U7")
      (value "DRV8801PWPR")
      (footprint "eagle-import:TI-HTSSOP-16")
      (libsource (lib "eagle-import") (part "DRV8801PWPR"))
    )
    (comp (ref "U8")
      (value "DRV8801PWPR")
      (footprint "eagle-import:TI-HTSSOP-16")
      (libsource (lib "eagle-import") (part "DRV8801PWPR"))
    )
    (comp (ref "U9")
      (value "DRV8801PWPR")
      (footprint "eagle-import:TI-HTSSOP-16")
      (libsource (lib "eagle-import") (part "DRV8801PWPR"))
    )
    (comp (ref "C93")
      (value "0.1uF")
      (footprint "eagle-import:C0402")
      (libsource (lib "eagle-import") (part "C0402"))
    )
    (comp (ref "D6")
      (value "LED-PWR-XLAMP_MX3")
      (footprint "eagle-import:XLAMP-MX3")
      (libsource (lib "eagle-import") (part "LED-PWR-XLAMP_MX3"))
    )
    (comp (ref "Q7")
      (value "NMOS-CSD18533Q5A")
      (footprint "eagle-import:SON-5X6")
      (libsource (lib "eagle-import") (part "NMOS-CSD18533Q5A"))
    )
    (comp (ref "Q8")
      (value "BSS138L")
      (footprint "eagle-import:SOT23")
      (libsource (lib "eagle-import") (part "BSS138L"))
    )
    (comp (ref "R79")
      (value "0.68")
      (footprint "eagle-import:R0805")
      (libsource (lib "eagle-import") (part "R0805"))
    )
    (comp (ref "R80")
      (value "10")
      (footprint "eagle-import:R0402")
      (libsource (lib "eagle-import") (part "R0402"))
    )
    (comp (ref "R81")
      (value "0")
      (footprint "eagle-import:R0402")
      (libsource (lib "eagle-import") (part "R0402"))
    )
    (comp (ref "R82")
      (value "470k")
      (footprint "eagle-import:R0402")
      (libsource (lib "eagle-import") (part "R0402"))
    )
    (comp (ref "U12")
      (value "OPA170AIDBVR")
      (footprint "eagle-import:SOT23-5")
      (libsource (lib "eagle-import") (part "OPA170AIDBVR"))
    )
    (comp (ref "VR1")
      (value "10k")
      (footprint "eagle-import:ST-4EA")
      (libsource (lib "eagle-import") (part "R-TRIM-ST4ETA204"))
    )
    (comp (ref "C27")
      (value "2.2uF")
      (footprint "eagle-import:C1210")
      (libsource (lib "eagle-import") (part "C1210"))
    )
    (comp (ref "C28")
      (value "1000pF")
      (footprint "eagle-import:C0402")
      (libsource (lib "eagle-import") (part "C0402"))
    )
    (comp (ref "C29")
      (value "0.1uF")
      (footprint "eagle-import:C0402")
      (libsource (lib "eagle-import") (part "C0402"))
    )
    (comp (ref "C30")
      (value "0.1uF")
      (footprint "eagle-import:C0402")
      (libsource (lib "eagle-import") (part "C0402"))
    )
    (comp (ref "C31")
      (value "0.1uF")
      (footprint "eagle-import:C0402")
      (libsource (lib "eagle-import") (part "C0402"))
    )
    (comp (ref "C32")
      (value "2.2uF")
      (footprint "eagle-import:C1210")
      (libsource (lib "eagle-import") (part "C1210"))
    )
    (comp (ref "C33")
      (value "1000pF")
      (footprint "eagle-import:C0402")
      (libsource (lib "eagle-import") (part "C0402"))
    )
    (comp (ref "C34")
      (value "2.2uF")
      (footprint "eagle-import:C1210")
      (libsource (lib "eagle-import") (part "C1210"))
    )
    (comp (ref "C35")
      (value "1000pF")
      (footprint "eagle-import:C0402")
      (libsource (lib "eagle-import") (part "C0402"))
    )
    (comp (ref "J8")
      (value "1X3-0.1IN_THRUHOLE")
      (footprint "eagle-import:1X3_0.1IN_THRUHOLE")
      (libsource (lib "eagle-import") (part "1X3-0.1IN_THRUHOLE"))
    )
    (comp (ref "Q1")
      (value "NMOS-CSD18533Q5A")
      (footprint "eagle-import:SON-5X6")
      (libsource (lib "eagle-import") (part "NMOS-CSD18533Q5A"))
    )
    (comp (ref "Q2")
      (value "NMOS-CSD18533Q5A")
      (footprint "eagle-import:SON-5X6")
      (libsource (lib "eagle-import") (part "NMOS-CSD18533Q5A"))
    )
    (comp (ref "Q3")
      (value "NMOS-CSD18533Q5A")
      (footprint "eagle-import:SON-5X6")
      (libsource (lib "eagle-import") (part "NMOS-CSD18533Q5A"))
    )
    (comp (ref "Q4")
      (value "NMOS-CSD18533Q5A")
      (footprint "eagle-import:SON-5X6")
      (libsource (lib "eagle-import") (part "NMOS-CSD18533Q5A"))
    )
    (comp (ref "Q5")
      (value "NMOS-CSD18533Q5A")
      (footprint "eagle-import:SON-5X6")
      (libsource (lib "eagle-import") (part "NMOS-CSD18533Q5A"))
    )
    (comp (ref "Q6")
      (value "NMOS-CSD18533Q5A")
      (footprint "eagle-import:SON-5X6")
      (libsource (lib "eagle-import") (part "NMOS-CSD18533Q5A"))
    )
    (comp (ref "R22")
      (value "0.01")
      (footprint "eagle-import:R2010-4")
      (libsource (lib "eagle-import") (part "R-SENSE2010-0.01"))
    )
    (comp (ref "R23")
      (value "10")
      (footprint "eagle-import:R0402")
      (libsource (lib "eagle-import") (part "R0402"))
    )
    (comp (ref "R24")
      (value "10")
      (footprint "eagle-import:R0402")
      (libsource (lib "eagle-import") (part "R0402"))
    )
    (comp (ref "R25")
      (value "10")
      (footprint "eagle-import:R0402")
      (libsource (lib "eagle-import") (part "R0402"))
    )
    (comp (ref "R26")
      (value "10")
      (footprint "eagle-import:R0402")
      (libsource (lib "eagle-import") (part "R0402"))
    )
    (comp (ref "R27")
      (value "0.01")
      (footprint "eagle-import:R2010-4")
      (libsource (lib "eagle-import") (part "R-SENSE2010-0.01"))
    )
    (comp (ref "R28")
      (value "10")
      (footprint "eagle-import:R0402")
      (libsource (lib "eagle-import") (part "R0402"))
    )
    (comp (ref "R29")
      (value "10")
      (footprint "eagle-import:R0402")
      (libsource (lib "eagle-import") (part "R0402"))
    )
    (comp (ref "R30")
      (value "0.01")
      (footprint "eagle-import:R2010-4")
      (libsource (lib "eagle-import") (part "R-SENSE2010-0.01"))
    )
    (comp (ref "U10")
      (value "DRV8301DCAR")
      (footprint "eagle-import:TI-HTSSOP-56")
      (libsource (lib "eagle-import") (part "DRV8301DCAR"))
    )
    (comp (ref "C66")
      (value "2.2uF")
      (footprint "eagle-import:C0402")
      (libsource (lib "eagle-import") (part "C0402"))
    )
    (comp (ref "C67")
      (value "2.2uF")
      (footprint "eagle-import:C0402")
      (libsource (lib "eagle-import") (part "C0402"))
    )
    (comp (ref "C68")
      (value "2.2uF")
      (footprint "eagle-import:C0402")
      (libsource (lib "eagle-import") (part "C0402"))
    )
    (comp (ref "C69")
      (value "2.2uF")
      (footprint "eagle-import:C0402")
      (libsource (lib "eagle-import") (part "C0402"))
    )
    (comp (ref "C70")
      (value "2.2uF")
      (footprint "eagle-import:C0402")
      (libsource (lib "eagle-import") (part "C0402"))
    )
    (comp (ref "C71")
      (value "2.2uF")
      (footprint "eagle-import:C0402")
      (libsource (lib "eagle-import") (part "C0402"))
    )
    (comp (ref "C72")
      (value "2.2uF")
      (footprint "eagle-import:C0402")
      (libsource (lib "eagle-import") (part "C0402"))
    )
    (comp (ref "C73")
      (value "2.2uF")
      (footprint "eagle-import:C0402")
      (libsource (lib "eagle-import") (part "C0402"))
    )
    (comp (ref "C74")
      (value "2.2uF")
      (footprint "eagle-import:C0402")
      (libsource (lib "eagle-import") (part "C0402"))
    )
    (comp (ref "C75")
      (value "2.2uF")
      (footprint "eagle-import:C0402")
      (libsource (lib "eagle-import") (part "C0402"))
    )
    (comp (ref "C76")
      (value "2.2uF")
      (footprint "eagle-import:C0402")
      (libsource (lib "eagle-import") (part "C0402"))
    )
    (comp (ref "C77")
      (value "2.2uF")
      (footprint "eagle-import:C0402")
      (libsource (lib "eagle-import") (part "C0402"))
    )
    (comp (ref "C78")
      (value "2.2uF")
      (footprint "eagle-import:C0402")
      (libsource (lib "eagle-import") (part "C0402"))
    )
    (comp (ref "C79")
      (value "2.2uF")
      (footprint "eagle-import:C0402")
      (libsource (lib "eagle-import") (part "C0402"))
    )
    (comp (ref "C80")
      (value "0.1uF")
      (footprint "eagle-import:C0402")
      (libsource (lib "eagle-import") (part "C0402"))
    )
    (comp (ref "C81")
      (value "0.1uF")
      (footprint "eagle-import:C0402")
      (libsource (lib "eagle-import") (part "C0402"))
    )
    (comp (ref "J7")
      (value "JTAG-ARM_TC-10")
      (footprint "eagle-import:TC2050-IDC")
      (libsource (lib "eagle-import") (part "JTAG-ARM_TC-10"))
    )
    (comp (ref "L3")
      (value "BLM15PD600SN1D")
      (footprint "eagle-import:L0402")
      (fields
        (field (name "DIST_NAME") "Digi-key")
        (field (name "DIST_PN") "490-5201-1-ND")
        (field (name "MFG_NAME") "Murata Electronics North America")
        (field (name "MFG_PN") "BLM15PD600SN1D")
      )
      (libsource (lib "eagle-import") (part "L0402"))
    )
    (comp (ref "L4")
      (value "BKP1005HS221-T")
      (footprint "eagle-import:L0402")
      (libsource (lib "eagle-import") (part "L0402"))
    )
    (comp (ref "R40")
      (value "0")
      (footprint "eagle-import:R0402")
      (libsource (lib "eagle-import") (part "R0402"))
    )
    (comp (ref "R41")
      (value "0")
      (footprint "eagle-import:R0402")
      (libsource (lib "eagle-import") (part "R0402"))
    )
    (comp (ref "R42")
      (value "0")
      (footprint "eagle-import:R0402")
      (libsource (lib "eagle-import") (part "R0402"))
    )
    (comp (ref "R43")
      (value "0")
      (footprint "eagle-import:R0402")
      (libsource (lib "eagle-import") (part "R0402"))
    )
    (comp (ref "R44")
      (value "0")
      (footprint "eagle-import:R0402")
      (libsource (lib "eagle-import") (part "R0402"))
    )
    (comp (ref "R45")
      (value "0")
      (footprint "eagle-import:R0402")
      (libsource (lib "eagle-import") (part "R0402"))
    )
    (comp (ref "R46")
      (value "0")
      (footprint "eagle-import:R0402")
      (libsource (lib "eagle-import") (part "R0402"))
    )
    (comp (ref "R47")
      (value "0")
      (footprint "eagle-import:R0402")
      (libsource (lib "eagle-import") (part "R0402"))
    )
    (comp (ref "R48")
      (value "0")
      (footprint "eagle-import:R0402")
      (libsource (lib "eagle-import") (part "R0402"))
    )
    (comp (ref "R49")
      (value "0")
      (footprint "eagle-import:R0402")
      (libsource (lib "eagle-import") (part "R0402"))
    )
    (comp (ref "R50")
      (value "0")
      (footprint "eagle-import:R0402")
      (libsource (lib "eagle-import") (part "R0402"))
    )
    (comp (ref "R51")
      (value "0")
      (footprint "eagle-import:R0402")
      (libsource (lib "eagle-import") (part "R0402"))
    )
    (comp (ref "R52")
      (value "0")
      (footprint "eagle-import:R0402")
      (libsource (lib "eagle-import") (part "R0402"))
    )
    (comp (ref "R53")
      (value "0")
      (footprint "eagle-import:R0402")
      (libsource (lib "eagle-import") (part "R0402"))
    )
    (comp (ref "R54")
      (value "0")
      (footprint "eagle-import:R0402")
      (libsource (lib "eagle-import") (part "R0402"))
    )
    (comp (ref "R55")
      (value "0")
      (footprint "eagle-import:R0402")
      (libsource (lib "eagle-import") (part "R0402"))
    )
    (comp (ref "R56")
      (value "0")
      (footprint "eagle-import:R0402")
      (libsource (lib "eagle-import") (part "R0402"))
    )
    (comp (ref "R57")
      (value "0")
      (footprint "eagle-import:R0402")
      (libsource (lib "eagle-import") (part "R0402"))
    )
    (comp (ref "R58")
      (value "0")
      (footprint "eagle-import:R0402")
      (libsource (lib "eagle-import") (part "R0402"))
    )
    (comp (ref "R59")
      (value "0")
      (footprint "eagle-import:R0402")
      (libsource (lib "eagle-import") (part "R0402"))
    )
    (comp (ref "R60")
      (value "0")
      (footprint "eagle-import:R0402")
      (libsource (lib "eagle-import") (part "R0402"))
    )
    (comp (ref "R78")
      (value "2.2k")
      (footprint "eagle-import:R0402")
      (libsource (lib "eagle-import") (part "R0402"))
    )
    (comp (ref "R93")
      (value "0")
      (footprint "eagle-import:R0402")
      (libsource (lib "eagle-import") (part "R0402"))
    )
    (comp (ref "R94")
      (value "0")
      (footprint "eagle-import:R0402")
      (libsource (lib "eagle-import") (part "R0402"))
    )
    (comp (ref "R95")
      (value "0")
      (footprint "eagle-import:R0402")
      (libsource (lib "eagle-import") (part "R0402"))
    )
    (comp (ref "R96")
      (value "0")
      (footprint "eagle-import:R0402")
      (libsource (lib "eagle-import") (part "R0402"))
    )
    (comp (ref "R101")
      (value "0")
      (footprint "eagle-import:R0402")
      (libsource (lib "eagle-import") (part "R0402"))
    )
    (comp (ref "R102")
      (value "0")
      (footprint "eagle-import:R0402")
      (libsource (lib "eagle-import") (part "R0402"))
    )
    (comp (ref "R103")
      (value "0")
      (footprint "eagle-import:R0402")
      (libsource (lib "eagle-import") (part "R0402"))
    )
    (comp (ref "R104")
      (value "0")
      (footprint "eagle-import:R0402")
      (libsource (lib "eagle-import") (part "R0402"))
    )
    (comp (ref "R115")
      (value "0")
      (footprint "eagle-import:R0402")
      (libsource (lib "eagle-import") (part "R0402"))
    )
    (comp (ref "R116")
      (value "0")
      (footprint "eagle-import:R0402")
      (libsource (lib "eagle-import") (part "R0402"))
    )
    (comp (ref "R117")
      (value "0")
      (footprint "eagle-import:R0402")
      (libsource (lib "eagle-import") (part "R0402"))
    )
    (comp (ref "R118")
      (value "0")
      (footprint "eagle-import:R0402")
      (libsource (lib "eagle-import") (part "R0402"))
    )
    (comp (ref "R119")
      (value "820")
      (footprint "eagle-import:R0402")
      (libsource (lib "eagle-import") (part "R0402"))
    )
    (comp (ref "R120")
      (value "2.2k")
      (footprint "eagle-import:R0402")
      (libsource (lib "eagle-import") (part "R0402"))
    )
    (comp (ref "R121")
      (value "820")
      (footprint "eagle-import:R0402")
      (libsource (lib "eagle-import") (part "R0402"))
    )
    (comp (ref "R122")
      (value "2.2k")
      (footprint "eagle-import:R0402")
      (libsource (lib "eagle-import") (part "R0402"))
    )
    (comp (ref "R124")
      (value "0")
      (footprint "eagle-import:R0402")
      (libsource (lib "eagle-import") (part "R0402"))
    )
    (comp (ref "R125")
      (value "0")
      (footprint "eagle-import:R0402")
      (libsource (lib "eagle-import") (part "R0402"))
    )
    (comp (ref "R126")
      (value "0")
      (footprint "eagle-import:R0402")
      (libsource (lib "eagle-import") (part "R0402"))
    )
    (comp (ref "S1")
      (value "TACTILE-SWITCH-EVQP2")
      (footprint "eagle-import:EVQP2")
      (libsource (lib "eagle-import") (part "TACTILE-SWITCH-EVQP2"))
    )
    (comp (ref "U5")
      (value "TMS320F28069MPZT")
      (footprint "eagle-import:TI-LQFP-100")
      (libsource (lib "eagle-import") (part "TMS320F28069MPZT"))
    )
    (comp (ref "C36")
      (value "0.022uF")
      (footprint "eagle-import:C0402")
      (libsource (lib "eagle-import") (part "C0402"))
    )
    (comp (ref "C37")
      (value "1uF")
      (footprint "eagle-import:C0402")
      (libsource (lib "eagle-import") (part "C0402"))
    )
    (comp (ref "C38")
      (value "1uF")
      (footprint "eagle-import:C0402")
      (libsource (lib "eagle-import") (part "C0402"))
    )
    (comp (ref "C39")
      (value "22uF")
      (footprint "eagle-import:C1210")
      (libsource (lib "eagle-import") (part "C1210"))
    )
    (comp (ref "C40")
      (value "22uF")
      (footprint "eagle-import:C1210")
      (libsource (lib "eagle-import") (part "C1210"))
    )
    (comp (ref "C41")
      (value "0.1uF")
      (footprint "eagle-import:C0402")
      (libsource (lib "eagle-import") (part "C0402"))
    )
    (comp (ref "C42")
      (value "1uF")
      (footprint "eagle-import:C0805")
      (libsource (lib "eagle-import") (part "C0805"))
    )
    (comp (ref "C43")
      (value "0.1uF")
      (footprint "eagle-import:C0402")
      (libsource (lib "eagle-import") (part "C0402"))
    )
    (comp (ref "C44")
      (value "0.1uF")
      (footprint "eagle-import:C0402")
      (libsource (lib "eagle-import") (part "C0402"))
    )
    (comp (ref "C45")
      (value "2.2uF")
      (footprint "eagle-import:C0603")
      (libsource (lib "eagle-import") (part "C0603"))
    )
    (comp (ref "C46")
      (value "0.015uF")
      (footprint "eagle-import:C0402")
      (libsource (lib "eagle-import") (part "C0402"))
    )
    (comp (ref "C47")
      (value "0.1uF")
      (footprint "eagle-import:C0402")
      (libsource (lib "eagle-import") (part "C0402"))
    )
    (comp (ref "C48")
      (value "2.2uF")
      (footprint "eagle-import:C0805")
      (libsource (lib "eagle-import") (part "C0805"))
    )
    (comp (ref "C49")
      (value "0.1uF")
      (footprint "eagle-import:C0402")
      (libsource (lib "eagle-import") (part "C0402"))
    )
    (comp (ref "C50")
      (value "6800pF")
      (footprint "eagle-import:C0402")
      (libsource (lib "eagle-import") (part "C0402"))
    )
    (comp (ref "C51")
      (value "120pF")
      (footprint "eagle-import:C0402")
      (libsource (lib "eagle-import") (part "C0402"))
    )
    (comp (ref "C52")
      (value "2.2uF")
      (footprint "eagle-import:C0805")
      (libsource (lib "eagle-import") (part "C0805"))
    )
    (comp (ref "C53")
      (value "0.1uF")
      (footprint "eagle-import:C0402")
      (libsource (lib "eagle-import") (part "C0402"))
    )
    (comp (ref "C56")
      (value "0.1uF")
      (footprint "eagle-import:C0402")
      (libsource (lib "eagle-import") (part "C0402"))
    )
    (comp (ref "C57")
      (value "2.2uF")
      (footprint "eagle-import:C0402")
      (libsource (lib "eagle-import") (part "C0402"))
    )
    (comp (ref "C58")
      (value "0.1uF")
      (footprint "eagle-import:C0402")
      (libsource (lib "eagle-import") (part "C0402"))
    )
    (comp (ref "C59")
      (value "0.1uF")
      (footprint "eagle-import:C0402")
      (libsource (lib "eagle-import") (part "C0402"))
    )
    (comp (ref "C60")
      (value "0.1uF")
      (footprint "eagle-import:C0402")
      (libsource (lib "eagle-import") (part "C0402"))
    )
    (comp (ref "C61")
      (value "0.1uF")
      (footprint "eagle-import:C0402")
      (libsource (lib "eagle-import") (part "C0402"))
    )
    (comp (ref "C62")
      (value "0.1uF")
      (footprint "eagle-import:C0402")
      (libsource (lib "eagle-import") (part "C0402"))
    )
    (comp (ref "C63")
      (value "2200pF")
      (footprint "eagle-import:C0402")
      (libsource (lib "eagle-import") (part "C0402"))
    )
    (comp (ref "C64")
      (value "2200pF")
      (footprint "eagle-import:C0402")
      (libsource (lib "eagle-import") (part "C0402"))
    )
    (comp (ref "C65")
      (value "2200pF")
      (footprint "eagle-import:C0402")
      (libsource (lib "eagle-import") (part "C0402"))
    )
    (comp (ref "C86")
      (value "220uF")
      (footprint "eagle-import:PANASONIC-6.3MM-SMD")
      (libsource (lib "eagle-import") (part "CPOL-PANASONIC-6.3MM-SMD-220UF-25V"))
    )
    (comp (ref "C87")
      (value "220uF")
      (footprint "eagle-import:PANASONIC-6.3MM-SMD")
      (libsource (lib "eagle-import") (part "CPOL-PANASONIC-6.3MM-SMD-220UF-25V"))
    )
    (comp (ref "D5")
      (value "B220A-13-F")
      (footprint "eagle-import:SMB")
      (libsource (lib "eagle-import") (part "B220A-13-F"))
    )
    (comp (ref "L2")
      (value "33uH")
      (footprint "eagle-import:DR74")
      (libsource (lib "eagle-import") (part "DR74"))
    )
    (comp (ref "R31")
      (value "1")
      (footprint "eagle-import:R0402")
      (libsource (lib "eagle-import") (part "R0402"))
    )
    (comp (ref "R32")
      (value "205k")
      (footprint "eagle-import:R0402")
      (libsource (lib "eagle-import") (part "R0402"))
    )
    (comp (ref "R33")
      (value "10k")
      (footprint "eagle-import:R0402")
      (libsource (lib "eagle-import") (part "R0402"))
    )
    (comp (ref "R34")
      (value "16.2k")
      (footprint "eagle-import:R0402")
      (libsource (lib "eagle-import") (part "R0402"))
    )
    (comp (ref "R35")
      (value "31.6k")
      (footprint "eagle-import:R0402")
      (libsource (lib "eagle-import") (part "R0402"))
    )
    (comp (ref "R36")
      (value "10k")
      (footprint "eagle-import:R0402")
      (libsource (lib "eagle-import") (part "R0402"))
    )
    (comp (ref "R37")
      (value "10k")
      (footprint "eagle-import:R0402")
      (libsource (lib "eagle-import") (part "R0402"))
    )
    (comp (ref "R38")
      (value "10k")
      (footprint "eagle-import:R0402")
      (libsource (lib "eagle-import") (part "R0402"))
    )
    (comp (ref "R39")
      (value "1k")
      (footprint "eagle-import:R0402")
      (libsource (lib "eagle-import") (part "R0402"))
    )
    (comp (ref "R61")
      (value "10k")
      (footprint "eagle-import:R0402")
      (libsource (lib "eagle-import") (part "R0402"))
    )
    (comp (ref "R62")
      (value "1k")
      (footprint "eagle-import:R0402")
      (libsource (lib "eagle-import") (part "R0402"))
    )
    (comp (ref "R63")
      (value "1k")
      (footprint "eagle-import:R0402")
      (libsource (lib "eagle-import") (part "R0402"))
    )
    (comp (ref "R64")
      (value "10k")
      (footprint "eagle-import:R0402")
      (libsource (lib "eagle-import") (part "R0402"))
    )
    (comp (ref "R65")
      (value "10k")
      (footprint "eagle-import:R0402")
      (libsource (lib "eagle-import") (part "R0402"))
    )
    (comp (ref "R66")
      (value "10k")
      (footprint "eagle-import:R0402")
      (libsource (lib "eagle-import") (part "R0402"))
    )
    (comp (ref "R67")
      (value "34.8k")
      (footprint "eagle-import:R0402")
      (libsource (lib "eagle-import") (part "R0402"))
    )
    (comp (ref "R68")
      (value "4.99k")
      (footprint "eagle-import:R0402")
      (libsource (lib "eagle-import") (part "R0402"))
    )
    (comp (ref "R69")
      (value "34.8k")
      (footprint "eagle-import:R0402")
      (libsource (lib "eagle-import") (part "R0402"))
    )
    (comp (ref "R70")
      (value "4.99k")
      (footprint "eagle-import:R0402")
      (libsource (lib "eagle-import") (part "R0402"))
    )
    (comp (ref "R71")
      (value "34.8k")
      (footprint "eagle-import:R0402")
      (libsource (lib "eagle-import") (part "R0402"))
    )
    (comp (ref "R72")
      (value "4.99k")
      (footprint "eagle-import:R0402")
      (libsource (lib "eagle-import") (part "R0402"))
    )
    (comp (ref "R73")
      (value "34.8k")
      (footprint "eagle-import:R0402")
      (libsource (lib "eagle-import") (part "R0402"))
    )
    (comp (ref "R74")
      (value "4.99k")
      (footprint "eagle-import:R0402")
      (libsource (lib "eagle-import") (part "R0402"))
    )
    (comp (ref "R75")
      (value "56")
      (footprint "eagle-import:R0402")
      (libsource (lib "eagle-import") (part "R0402"))
    )
    (comp (ref "R76")
      (value "56")
      (footprint "eagle-import:R0402")
      (libsource (lib "eagle-import") (part "R0402"))
    )
    (comp (ref "R77")
      (value "56")
      (footprint "eagle-import:R0402")
      (libsource (lib "eagle-import") (part "R0402"))
    )
    (comp (ref "U11")
      (value "OPA2374AIDCNR")
      (footprint "eagle-import:TI-SOT23-8")
      (libsource (lib "eagle-import") (part "OPA2374AIDCNR"))
    )
    (comp (ref "C1")
      (value "0.1uF")
      (footprint "eagle-import:C0402")
      (libsource (lib "eagle-import") (part "C0402"))
    )
    (comp (ref "C2")
      (value "4.7uF")
      (footprint "eagle-import:C0805")
      (libsource (lib "eagle-import") (part "C0805"))
    )
    (comp (ref "C3")
      (value "0.01uF")
      (footprint "eagle-import:C0402")
      (libsource (lib "eagle-import") (part "C0402"))
    )
    (comp (ref "C4")
      (value "0.1uF")
      (footprint "eagle-import:C0402")
      (libsource (lib "eagle-import") (part "C0402"))
    )
    (comp (ref "C8")
      (value "4.7uF")
      (footprint "eagle-import:C0805")
      (libsource (lib "eagle-import") (part "C0805"))
    )
    (comp (ref "C9")
      (value "4.7uF")
      (footprint "eagle-import:C0805")
      (libsource (lib "eagle-import") (part "C0805"))
    )
    (comp (ref "C54")
      (value "0.1uF")
      (footprint "eagle-import:C0402")
      (libsource (lib "eagle-import") (part "C0402"))
    )
    (comp (ref "C55")
      (value "0.1uF")
      (footprint "eagle-import:C0402")
      (libsource (lib "eagle-import") (part "C0402"))
    )
    (comp (ref "C95")
      (value "4.7uF")
      (footprint "eagle-import:C0603")
      (libsource (lib "eagle-import") (part "C0603"))
    )
    (comp (ref "D4")
      (value "LED0603")
      (footprint "eagle-import:LED0603")
      (fields (field (name "COLOR") "RED"))
      (libsource (lib "eagle-import") (part "LED0603"))
    )
    (comp (ref "J4")
      (value "1X2-JST-PH-SMD")
      (footprint "eagle-import:JST-PH-2-SMD")
      (libsource (lib "eagle-import") (part "1X2-JST-PH-SMD"))
    )
    (comp (ref "J5")
      (value "1X2-0428202213")
      (footprint "eagle-import:MOLEX_SABRE_2POS")
      (libsource (lib "eagle-import") (part "1X2-0428202213"))
    )
    (comp (ref "J9")
      (value "1X2-PTSA_1.5/2-3.5-Z")
      (footprint "eagle-import:3.5MM_PTSA_1.5_2-3.5-Z")
      (libsource (lib "eagle-import") (part "1X2-PTSA_1.5/2-3.5-Z"))
    )
    (comp (ref "J10")
      (value "1X5")
      (footprint "eagle-import:1X5_0.1IN_THRUHOLE")
      (libsource (lib "eagle-import") (part "1X5"))
    )
    (comp (ref "Q9")
      (value "BSS138L")
      (footprint "eagle-import:SOT23")
      (libsource (lib "eagle-import") (part "BSS138L"))
    )
    (comp (ref "Q10")
      (value "NMOS-CSD18533Q5A")
      (footprint "eagle-import:SON-5X6")
      (libsource (lib "eagle-import") (part "NMOS-CSD18533Q5A"))
    )
    (comp (ref "Q11")
      (value "IRFML8244TRPBF")
      (footprint "eagle-import:SOT23")
      (libsource (lib "eagle-import") (part "IRFML8244TRPBF"))
    )
    (comp (ref "R4")
      (value "470")
      (footprint "eagle-import:R0402")
      (libsource (lib "eagle-import") (part "R0402"))
    )
    (comp (ref "R5")
      (value "2k")
      (footprint "eagle-import:R0402")
      (libsource (lib "eagle-import") (part "R0402"))
    )
    (comp (ref "R89")
      (value "1k")
      (footprint "eagle-import:R0402")
      (libsource (lib "eagle-import") (part "R0402"))
    )
    (comp (ref "R90")
      (value "100")
      (footprint "eagle-import:R0402")
      (libsource (lib "eagle-import") (part "R0402"))
    )
    (comp (ref "R91")
      (value "DNP")
      (footprint "eagle-import:R0402")
      (libsource (lib "eagle-import") (part "R0402"))
    )
    (comp (ref "R92")
      (value "DNP")
      (footprint "eagle-import:R0805")
      (libsource (lib "eagle-import") (part "R0805"))
    )
    (comp (ref "R109")
      (value "23.2k")
      (footprint "eagle-import:R0402")
      (libsource (lib "eagle-import") (part "R0402"))
    )
    (comp (ref "R110")
      (value "45.2k")
      (footprint "eagle-import:R0402")
      (libsource (lib "eagle-import") (part "R0402"))
    )
    (comp (ref "R111")
      (value "23.2k")
      (footprint "eagle-import:R0402")
      (libsource (lib "eagle-import") (part "R0402"))
    )
    (comp (ref "R112")
      (value "45.2k")
      (footprint "eagle-import:R0402")
      (libsource (lib "eagle-import") (part "R0402"))
    )
    (comp (ref "R113")
      (value "23.2k")
      (footprint "eagle-import:R0402")
      (libsource (lib "eagle-import") (part "R0402"))
    )
    (comp (ref "R114")
      (value "45.2k")
      (footprint "eagle-import:R0402")
      (libsource (lib "eagle-import") (part "R0402"))
    )
    (comp (ref "U3")
      (value "TPS79933DDCR")
      (footprint "eagle-import:SOT23-5")
      (libsource (lib "eagle-import") (part "TPS79933DDCR"))
    )
    (comp (ref "U4")
      (value "MCP73831T-2ACI/OT")
      (footprint "eagle-import:SOT23-5")
      (libsource (lib "eagle-import") (part "MCP73831T-2ACI/OT"))
    )
    (comp (ref "U14")
      (value "TPS81256")
      (footprint "eagle-import:TI-SIP-9")
      (libsource (lib "eagle-import") (part "TPS81256"))
    )
  )
  (nets
    (net (code "1") (name "+3V3") (class "Default")
      (node (ref "C2") (pin "1") (pinfunction "1_1") (pintype "passive"))
      (node (ref "C39") (pin "1") (pinfunction "1_1") (pintype "passive"))
      (node (ref "C4") (pin "1") (pinfunction "1_1") (pintype "passive"))
      (node (ref "C40") (pin "1") (pinfunction "1_1") (pintype "passive"))
      (node (ref "C41") (pin "1") (pinfunction "1_1") (pintype "passive"))
      (node (ref "C42") (pin "1") (pinfunction "1_1") (pintype "passive"))
      (node (ref "C44") (pin "1") (pinfunction "1_1") (pintype "passive"))
      (node (ref "C47") (pin "1") (pinfunction "1_1") (pintype "passive"))
      (node (ref "C5") (pin "1") (pinfunction "1_1") (pintype "passive"))
      (node (ref "C56") (pin "1") (pinfunction "1_1") (pintype "passive"))
      (node (ref "C58") (pin "1") (pinfunction "1_1") (pintype "passive"))
      (node (ref "C79") (pin "1") (pinfunction "1_1") (pintype "passive"))
      (node (ref "C80") (pin "1") (pinfunction "1_1") (pintype "passive"))
      (node (ref "C89") (pin "1") (pinfunction "1_1") (pintype "passive"))
      (node (ref "C90") (pin "1") (pinfunction "1_1") (pintype "passive"))
      (node (ref "D1") (pin "ANODE") (pinfunction "ANODE_ANODE") (pintype "bidirectional"))
      (node (ref "D2") (pin "ANODE") (pinfunction "ANODE_ANODE") (pintype "bidirectional"))
      (node (ref "D3") (pin "ANODE") (pinfunction "ANODE_ANODE") (pintype "bidirectional"))
      (node (ref "J11") (pin "1") (pinfunction "1_1") (pintype "passive"))
      (node (ref "J6") (pin "1") (pinfunction "VCC_1") (pintype "bidirectional"))
      (node (ref "L2") (pin "1") (pinfunction "1_1") (pintype "passive"))
      (node (ref "L3") (pin "1") (pinfunction "1_1") (pintype "passive"))
      (node (ref "L4") (pin "1") (pinfunction "1_1") (pintype "passive"))
      (node (ref "L5") (pin "1") (pinfunction "1_1") (pintype "passive"))
      (node (ref "R100") (pin "2") (pinfunction "2_2") (pintype "passive"))
      (node (ref "R119") (pin "2") (pinfunction "2_2") (pintype "passive"))
      (node (ref "R121") (pin "2") (pinfunction "2_2") (pintype "passive"))
      (node (ref "R13") (pin "2") (pinfunction "2_2") (pintype "passive"))
      (node (ref "R15") (pin "2") (pinfunction "2_2") (pintype "passive"))
      (node (ref "R17") (pin "2") (pinfunction "2_2") (pintype "passive"))
      (node (ref "R20") (pin "2") (pinfunction "2_2") (pintype "passive"))
      (node (ref "R33") (pin "2") (pinfunction "2_2") (pintype "passive"))
      (node (ref "R35") (pin "2") (pinfunction "2_2") (pintype "passive"))
      (node (ref "R37") (pin "2") (pinfunction "2_2") (pintype "passive"))
      (node (ref "R38") (pin "2") (pinfunction "2_2") (pintype "passive"))
      (node (ref "R65") (pin "2") (pinfunction "2_2") (pintype "passive"))
      (node (ref "R7") (pin "2") (pinfunction "2_2") (pintype "passive"))
      (node (ref "R78") (pin "2") (pinfunction "2_2") (pintype "passive"))
      (node (ref "R82") (pin "1") (pinfunction "1_1") (pintype "passive"))
      (node (ref "R86") (pin "2") (pinfunction "2_2") (pintype "passive"))
      (node (ref "R87") (pin "2") (pinfunction "2_2") (pintype "passive"))
      (node (ref "R88") (pin "2") (pinfunction "2_2") (pintype "passive"))
      (node (ref "R9") (pin "2") (pinfunction "2_2") (pintype "passive"))
      (node (ref "R97") (pin "2") (pinfunction "2_2") (pintype "passive"))
      (node (ref "R98") (pin "2") (pinfunction "2_2") (pintype "passive"))
      (node (ref "R99") (pin "2") (pinfunction "2_2") (pintype "passive"))
      (node (ref "U10") (pin "24") (pinfunction "REF_24") (pintype "bidirectional"))
      (node (ref "U10") (pin "49") (pinfunction "VDD_SPI_49") (pintype "bidirectional"))
      (node (ref "U11") (pin "8") (pinfunction "V+_8") (pintype "bidirectional"))
      (node (ref "U13") (pin "11") (pinfunction "~{RESET}_11") (pintype "bidirectional"))
      (node (ref "U13") (pin "28") (pinfunction "VDDIO_28") (pintype "bidirectional"))
      (node (ref "U13") (pin "3") (pinfunction "VDD_3") (pintype "bidirectional"))
      (node (ref "U14") (pin "B2") (pinfunction "EN_B2") (pintype "bidirectional"))
      (node (ref "U14") (pin "C1") (pinfunction "VIN_C1") (pintype "bidirectional"))
      (node (ref "U14") (pin "C2") (pinfunction "VIN_C2") (pintype "bidirectional"))
      (node (ref "U2") (pin "1") (pinfunction "VCCIO_1") (pintype "bidirectional"))
      (node (ref "U3") (pin "5") (pinfunction "OUT_5") (pintype "bidirectional"))
      (node (ref "U5") (pin "46") (pinfunction "VDD_3VFL_46") (pintype "bidirectional"))
    )
    (net (code "2") (name "+5V") (class "Default")
      (node (ref "C54") (pin "1") (pinfunction "1_1") (pintype "passive"))
      (node (ref "C6") (pin "1") (pinfunction "1_1") (pintype "passive"))
      (node (ref "C7") (pin "1") (pinfunction "1_1") (pintype "passive"))
      (node (ref "C8") (pin "1") (pinfunction "1_1") (pintype "passive"))
      (node (ref "L1") (pin "2") (pinfunction "2_2") (pintype "passive"))
      (node (ref "R4") (pin "2") (pinfunction "2_2") (pintype "passive"))
      (node (ref "U2") (pin "19") (pinfunction "VCC_19") (pintype "bidirectional"))
      (node (ref "U4") (pin "4") (pinfunction "VDD_4") (pintype "bidirectional"))
    )
    (net (code "3") (name "+12V") (class "Default")
      (node (ref "C12") (pin "1") (pinfunction "1_1") (pintype "passive"))
      (node (ref "C13") (pin "1") (pinfunction "1_1") (pintype "passive"))
      (node (ref "C15") (pin "1") (pinfunction "1_1") (pintype "passive"))
      (node (ref "C16") (pin "1") (pinfunction "1_1") (pintype "passive"))
      (node (ref "C18") (pin "1") (pinfunction "1_1") (pintype "passive"))
      (node (ref "C19") (pin "1") (pinfunction "1_1") (pintype "passive"))
      (node (ref "C24") (pin "1") (pinfunction "1_1") (pintype "passive"))
      (node (ref "C25") (pin "1") (pinfunction "1_1") (pintype "passive"))
      (node (ref "C27") (pin "1") (pinfunction "1_1") (pintype "passive"))
      (node (ref "C32") (pin "1") (pinfunction "1_1") (pintype "passive"))
      (node (ref "C34") (pin "1") (pinfunction "1_1") (pintype "passive"))
      (node (ref "C48") (pin "1") (pinfunction "1_1") (pintype "passive"))
      (node (ref "C49") (pin "1") (pinfunction "1_1") (pintype "passive"))
      (node (ref "C52") (pin "1") (pinfunction "1_1") (pintype "passive"))
      (node (ref "C53") (pin "1") (pinfunction "1_1") (pintype "passive"))
      (node (ref "C82") (pin "POS") (pinfunction "+_POS") (pintype "passive"))
      (node (ref "C83") (pin "POS") (pinfunction "+_POS") (pintype "passive"))
      (node (ref "C84") (pin "POS") (pinfunction "+_POS") (pintype "passive"))
      (node (ref "C85") (pin "POS") (pinfunction "+_POS") (pintype "passive"))
      (node (ref "C86") (pin "POS") (pinfunction "+_POS") (pintype "passive"))
      (node (ref "C87") (pin "POS") (pinfunction "+_POS") (pintype "passive"))
      (node (ref "C93") (pin "1") (pinfunction "1_1") (pintype "passive"))
      (node (ref "D6") (pin "ANODE") (pinfunction "ANODE_ANODE") (pintype "bidirectional"))
      (node (ref "J5") (pin "P") (pinfunction "1_P") (pintype "passive"))
      (node (ref "J5") (pin "P2") (pinfunction "1_P2") (pintype "passive"))
      (node (ref "J9") (pin "1") (pinfunction "1_1") (pintype "passive"))
      (node (ref "Q1") (pin "D") (pinfunction "D_D") (pintype "passive"))
      (node (ref "Q10") (pin "G") (pinfunction "G_G") (pintype "passive"))
      (node (ref "Q3") (pin "D") (pinfunction "D_D") (pintype "passive"))
      (node (ref "Q5") (pin "D") (pinfunction "D_D") (pintype "passive"))
      (node (ref "R73") (pin "2") (pinfunction "2_2") (pintype "passive"))
      (node (ref "R90") (pin "2") (pinfunction "2_2") (pintype "passive"))
      (node (ref "U10") (pin "29") (pinfunction "PVDD1_29") (pintype "bidirectional"))
      (node (ref "U10") (pin "53") (pinfunction "PVDD2_53") (pintype "bidirectional"))
      (node (ref "U10") (pin "54") (pinfunction "PVDD2_54") (pintype "bidirectional"))
      (node (ref "U12") (pin "5") (pinfunction "V+_5") (pintype "bidirectional"))
      (node (ref "U6") (pin "9") (pinfunction "VBB_9") (pintype "bidirectional"))
      (node (ref "U7") (pin "9") (pinfunction "VBB_9") (pintype "bidirectional"))
      (node (ref "U8") (pin "9") (pinfunction "VBB_9") (pintype "bidirectional"))
      (node (ref "U9") (pin "9") (pinfunction "VBB_9") (pintype "bidirectional"))
    )
    (net (code "4") (name "ATUM_ADC4") (class "Default")
      (node (ref "J11") (pin "3") (pinfunction "3_3") (pintype "passive"))
      (node (ref "U1") (pin "26") (pinfunction "ADC4_26") (pintype "bidirectional"))
    )
    (net (code "5") (name "ATUM_ADC5") (class "Default")
      (node (ref "J11") (pin "2") (pinfunction "2_2") (pintype "passive"))
      (node (ref "U1") (pin "27") (pinfunction "ADC5_27") (pintype "bidirectional"))
    )
    (net (code "6") (name "AUX_ENABLE") (class "Default")
      (node (ref "R101") (pin "1") (pinfunction "1_1") (pintype "passive"))
      (node (ref "R105") (pin "1") (pinfunction "1_1") (pintype "passive"))
      (node (ref "U9") (pin "6") (pinfunction "ENABLE_6") (pintype "bidirectional"))
    )
    (net (code "7") (name "AUX_MODE1") (class "Default")
      (node (ref "R15") (pin "1") (pinfunction "1_1") (pintype "passive"))
      (node (ref "U9") (pin "2") (pinfunction "MODE1_2") (pintype "bidirectional"))
    )
    (net (code "8") (name "AUX_MODE2") (class "Default")
      (node (ref "R18") (pin "2") (pinfunction "2_2") (pintype "passive"))
      (node (ref "U9") (pin "16") (pinfunction "MODE2_16") (pintype "bidirectional"))
    )
    (net (code "9") (name "AUX_PHASE") (class "Default")
      (node (ref "R106") (pin "1") (pinfunction "1_1") (pintype "passive"))
      (node (ref "U9") (pin "3") (pinfunction "PHASE_3") (pintype "bidirectional"))
    )
    (net (code "10") (name "AUX_VPROPI") (class "Default")
      (node (ref "C26") (pin "1") (pinfunction "1_1") (pintype "passive"))
      (node (ref "R123") (pin "2") (pinfunction "2_2") (pintype "passive"))
      (node (ref "R21") (pin "1") (pinfunction "1_1") (pintype "passive"))
      (node (ref "R96") (pin "2") (pinfunction "2_2") (pintype "passive"))
    )
    (net (code "11") (name "A_ISENSE_N") (class "Default")
      (node (ref "C28") (pin "2") (pinfunction "2_2") (pintype "passive"))
      (node (ref "R22") (pin "V2") (pinfunction "S2_V2") (pintype "passive"))
      (node (ref "U10") (pin "33") (pinfunction "SN1_33") (pintype "bidirectional"))
    )
    (net (code "12") (name "A_ISENSE_P") (class "Default")
      (node (ref "C28") (pin "1") (pinfunction "1_1") (pintype "passive"))
      (node (ref "R22") (pin "V1") (pinfunction "S1_V1") (pintype "passive"))
      (node (ref "U10") (pin "32") (pinfunction "SP1_32") (pintype "bidirectional"))
    )
    (net (code "13") (name "BOOTLOADER_CTRL") (class "Default")
      (node (ref "S2") (pin "A2") (pinfunction "1_A2") (pintype "bidirectional"))
      (node (ref "U1") (pin "24") (pinfunction "BTLDR_CTRL_24") (pintype "bidirectional"))
    )
    (net (code "14") (name "BOOTLOADER_RX") (class "Default")
      (node (ref "U1") (pin "22") (pinfunction "BTLDR_RX_22") (pintype "bidirectional"))
      (node (ref "U2") (pin "30") (pinfunction "TXD_30") (pintype "bidirectional"))
    )
    (net (code "15") (name "BOOTLOADER_TX") (class "Default")
      (node (ref "U1") (pin "23") (pinfunction "BTLDR_TX_23") (pintype "bidirectional"))
      (node (ref "U2") (pin "2") (pinfunction "RXD_2") (pintype "bidirectional"))
    )
    (net (code "16") (name "B_ISENSE_N") (class "Default")
      (node (ref "C33") (pin "2") (pinfunction "2_2") (pintype "passive"))
      (node (ref "R27") (pin "V2") (pinfunction "S2_V2") (pintype "passive"))
      (node (ref "U10") (pin "31") (pinfunction "SN2_31") (pintype "bidirectional"))
    )
    (net (code "17") (name "B_ISENSE_P") (class "Default")
      (node (ref "C33") (pin "1") (pinfunction "1_1") (pintype "passive"))
      (node (ref "R27") (pin "V1") (pinfunction "S1_V1") (pintype "passive"))
      (node (ref "U10") (pin "30") (pinfunction "SP2_30") (pintype "bidirectional"))
    )
    (net (code "18") (name "C_ISENSE_N") (class "Default")
      (node (ref "C35") (pin "2") (pinfunction "2_2") (pintype "passive"))
      (node (ref "R30") (pin "V2") (pinfunction "S2_V2") (pintype "passive"))
      (node (ref "R63") (pin "1") (pinfunction "1_1") (pintype "passive"))
    )
    (net (code "19") (name "C_ISENSE_P") (class "Default")
      (node (ref "C35") (pin "1") (pinfunction "1_1") (pintype "passive"))
      (node (ref "R30") (pin "V1") (pinfunction "S1_V1") (pintype "passive"))
      (node (ref "R62") (pin "1") (pinfunction "1_1") (pintype "passive"))
    )
    (net (code "20") (name "DC_CAL") (class "Default")
      (node (ref "R39") (pin "2") (pinfunction "2_2") (pintype "passive"))
      (node (ref "R60") (pin "2") (pinfunction "2_2") (pintype "passive"))
      (node (ref "U10") (pin "12") (pinfunction "DC_CAL_12") (pintype "bidirectional"))
    )
    (net (code "21") (name "DC_V_FB") (class "Default")
      (node (ref "C62") (pin "1") (pinfunction "1_1") (pintype "passive"))
      (node (ref "R43") (pin "2") (pinfunction "2_2") (pintype "passive"))
      (node (ref "R73") (pin "1") (pinfunction "1_1") (pintype "passive"))
      (node (ref "R74") (pin "2") (pinfunction "2_2") (pintype "passive"))
    )
    (net (code "22") (name "DRV_SCK") (class "Default")
      (node (ref "R41") (pin "1") (pinfunction "1_1") (pintype "passive"))
      (node (ref "U10") (pin "11") (pinfunction "SCLK_11") (pintype "bidirectional"))
    )
    (net (code "23") (name "DRV_SDI") (class "Default")
      (node (ref "R57") (pin "1") (pinfunction "1_1") (pintype "passive"))
      (node (ref "U10") (pin "9") (pinfunction "SDI_9") (pintype "bidirectional"))
    )
    (net (code "24") (name "DRV_SDO") (class "Default")
      (node (ref "R58") (pin "1") (pinfunction "1_1") (pintype "passive"))
      (node (ref "U10") (pin "10") (pinfunction "SDO_10") (pintype "bidirectional"))
    )
    (net (code "25") (name "ENABLE1") (class "Default")
      (node (ref "R104") (pin "1") (pinfunction "1_1") (pintype "passive"))
      (node (ref "U6") (pin "6") (pinfunction "ENABLE_6") (pintype "bidirectional"))
    )
    (net (code "26") (name "ENABLE2") (class "Default")
      (node (ref "R103") (pin "1") (pinfunction "1_1") (pintype "passive"))
      (node (ref "U7") (pin "6") (pinfunction "ENABLE_6") (pintype "bidirectional"))
    )
    (net (code "27") (name "ENABLE3") (class "Default")
      (node (ref "R102") (pin "1") (pinfunction "1_1") (pintype "passive"))
      (node (ref "U8") (pin "6") (pinfunction "ENABLE_6") (pintype "bidirectional"))
    )
    (net (code "28") (name "ENC_PWR") (class "Default")
      (node (ref "C95") (pin "1") (pinfunction "1_1") (pintype "passive"))
      (node (ref "J10") (pin "2") (pinfunction "2_2") (pintype "passive"))
      (node (ref "U14") (pin "A3") (pinfunction "VOUT_A3") (pintype "bidirectional"))
      (node (ref "U14") (pin "B3") (pinfunction "VOUT_B3") (pintype "bidirectional"))
      (node (ref "U14") (pin "C3") (pinfunction "VOUT_C3") (pintype "bidirectional"))
    )
    (net (code "29") (name "EN_GATE") (class "Default")
      (node (ref "R59") (pin "2") (pinfunction "2_2") (pintype "passive"))
      (node (ref "U10") (pin "16") (pinfunction "EN_GATE_16") (pintype "bidirectional"))
    )
    (net (code "30") (name "EQEP1A") (class "Default")
      (node (ref "R107") (pin "1") (pinfunction "1_1") (pintype "passive"))
      (node (ref "R111") (pin "1") (pinfunction "1_1") (pintype "passive"))
      (node (ref "R112") (pin "2") (pinfunction "2_2") (pintype "passive"))
      (node (ref "U5") (pin "6") (pinfunction "GPIO20/EQEP1A/MDXA/COMP1OUT_6") (pintype "bidirectional"))
    )
    (net (code "31") (name "EQEP1B") (class "Default")
      (node (ref "R108") (pin "1") (pinfunction "1_1") (pintype "passive"))
      (node (ref "R109") (pin "1") (pinfunction "1_1") (pintype "passive"))
      (node (ref "R110") (pin "2") (pinfunction "2_2") (pintype "passive"))
      (node (ref "U5") (pin "7") (pinfunction "GPIO21/EQEP1B/MDRA/COMP2OUT_7") (pintype "bidirectional"))
    )
    (net (code "32") (name "EQEP1I") (class "Default")
      (node (ref "R113") (pin "1") (pinfunction "1_1") (pintype "passive"))
      (node (ref "R114") (pin "2") (pinfunction "2_2") (pintype "passive"))
      (node (ref "U5") (pin "2") (pinfunction "GPIO23/EQEP1I/MFSXA/SCIRXDB_2") (pintype "bidirectional"))
    )
    (net (code "33") (name "FAULT1") (class "Default")
      (node (ref "R9") (pin "1") (pinfunction "1_1") (pintype "passive"))
      (node (ref "U6") (pin "1") (pinfunction "~{FAULT}_1") (pintype "bidirectional"))
    )
    (net (code "34") (name "FAULT2") (class "Default")
      (node (ref "R13") (pin "1") (pinfunction "1_1") (pintype "passive"))
      (node (ref "U7") (pin "1") (pinfunction "~{FAULT}_1") (pintype "bidirectional"))
    )
    (net (code "35") (name "FAULT3") (class "Default")
      (node (ref "R17") (pin "1") (pinfunction "1_1") (pintype "passive"))
      (node (ref "U8") (pin "1") (pinfunction "~{FAULT}_1") (pintype "bidirectional"))
    )
    (net (code "36") (name "GND") (class "Default")
      (node (ref "C1") (pin "2") (pinfunction "2_2") (pintype "passive"))
      (node (ref "C10") (pin "2") (pinfunction "2_2") (pintype "passive"))
      (node (ref "C13") (pin "2") (pinfunction "2_2") (pintype "passive"))
      (node (ref "C16") (pin "2") (pinfunction "2_2") (pintype "passive"))
      (node (ref "C19") (pin "2") (pinfunction "2_2") (pintype "passive"))
      (node (ref "C2") (pin "2") (pinfunction "2_2") (pintype "passive"))
      (node (ref "C20") (pin "2") (pinfunction "2_2") (pintype "passive"))
      (node (ref "C21") (pin "2") (pinfunction "2_2") (pintype "passive"))
      (node (ref "C22") (pin "2") (pinfunction "2_2") (pintype "passive"))
      (node (ref "C25") (pin "2") (pinfunction "2_2") (pintype "passive"))
      (node (ref "C26") (pin "2") (pinfunction "2_2") (pintype "passive"))
      (node (ref "C27") (pin "2") (pinfunction "2_2") (pintype "passive"))
      (node (ref "C3") (pin "2") (pinfunction "2_2") (pintype "passive"))
      (node (ref "C32") (pin "2") (pinfunction "2_2") (pintype "passive"))
      (node (ref "C34") (pin "2") (pinfunction "2_2") (pintype "passive"))
      (node (ref "C37") (pin "2") (pinfunction "2_2") (pintype "passive"))
      (node (ref "C38") (pin "2") (pinfunction "2_2") (pintype "passive"))
      (node (ref "C39") (pin "2") (pinfunction "2_2") (pintype "passive"))
      (node (ref "C4") (pin "2") (pinfunction "2_2") (pintype "passive"))
      (node (ref "C40") (pin "2") (pinfunction "2_2") (pintype "passive"))
      (node (ref "C41") (pin "2") (pinfunction "2_2") (pintype "passive"))
      (node (ref "C42") (pin "2") (pinfunction "2_2") (pintype "passive"))
      (node (ref "C44") (pin "2") (pinfunction "2_2") (pintype "passive"))
      (node (ref "C45") (pin "2") (pinfunction "2_2") (pintype "passive"))
      (node (ref "C46") (pin "2") (pinfunction "2_2") (pintype "passive"))
      (node (ref "C47") (pin "2") (pinfunction "2_2") (pintype "passive"))
      (node (ref "C48") (pin "2") (pinfunction "2_2") (pintype "passive"))
      (node (ref "C49") (pin "2") (pinfunction "2_2") (pintype "passive"))
      (node (ref "C5") (pin "2") (pinfunction "2_2") (pintype "passive"))
      (node (ref "C50") (pin "2") (pinfunction "2_2") (pintype "passive"))
      (node (ref "C51") (pin "2") (pinfunction "2_2") (pintype "passive"))
      (node (ref "C52") (pin "2") (pinfunction "2_2") (pintype "passive"))
      (node (ref "C53") (pin "2") (pinfunction "2_2") (pintype "passive"))
      (node (ref "C54") (pin "2") (pinfunction "2_2") (pintype "passive"))
      (node (ref "C55") (pin "2") (pinfunction "2_2") (pintype "passive"))
      (node (ref "C56") (pin "2") (pinfunction "2_2") (pintype "passive"))
      (node (ref "C57") (pin "2") (pinfunction "2_2") (pintype "passive"))
      (node (ref "C58") (pin "2") (pinfunction "2_2") (pintype "passive"))
      (node (ref "C59") (pin "2") (pinfunction "2_2") (pintype "passive"))
      (node (ref "C6") (pin "2") (pinfunction "2_2") (pintype "passive"))
      (node (ref "C60") (pin "2") (pinfunction "2_2") (pintype "passive"))
      (node (ref "C61") (pin "2") (pinfunction "2_2") (pintype "passive"))
      (node (ref "C62") (pin "2") (pinfunction "2_2") (pintype "passive"))
      (node (ref "C63") (pin "2") (pinfunction "2_2") (pintype "passive"))
      (node (ref "C64") (pin "2") (pinfunction "2_2") (pintype "passive"))
      (node (ref "C65") (pin "2") (pinfunction "2_2") (pintype "passive"))
      (node (ref "C66") (pin "2") (pinfunction "2_2") (pintype "passive"))
      (node (ref "C67") (pin "2") (pinfunction "2_2") (pintype "passive"))
      (node (ref "C68") (pin "2") (pinfunction "2_2") (pintype "passive"))
      (node (ref "C69") (pin "2") (pinfunction "2_2") (pintype "passive"))
      (node (ref "C7") (pin "2") (pinfunction "2_2") (pintype "passive"))
      (node (ref "C70") (pin "2") (pinfunction "2_2") (pintype "passive"))
      (node (ref "C71") (pin "2") (pinfunction "2_2") (pintype "passive"))
      (node (ref "C72") (pin "2") (pinfunction "2_2") (pintype "passive"))
      (node (ref "C73") (pin "2") (pinfunction "2_2") (pintype "passive"))
      (node (ref "C74") (pin "2") (pinfunction "2_2") (pintype "passive"))
      (node (ref "C75") (pin "2") (pinfunction "2_2") (pintype "passive"))
      (node (ref "C76") (pin "2") (pinfunction "2_2") (pintype "passive"))
      (node (ref "C77") (pin "2") (pinfunction "2_2") (pintype "passive"))
      (node (ref "C78") (pin "2") (pinfunction "2_2") (pintype "passive"))
      (node (ref "C79") (pin "2") (pinfunction "2_2") (pintype "passive"))
      (node (ref "C8") (pin "2") (pinfunction "2_2") (pintype "passive"))
      (node (ref "C80") (pin "2") (pinfunction "2_2") (pintype "passive"))
      (node (ref "C81") (pin "2") (pinfunction "2_2") (pintype "passive"))
      (node (ref "C82") (pin "NEG") (pinfunction "-_NEG") (pintype "passive"))
      (node (ref "C83") (pin "NEG") (pinfunction "-_NEG") (pintype "passive"))
      (node (ref "C84") (pin "NEG") (pinfunction "-_NEG") (pintype "passive"))
      (node (ref "C85") (pin "NEG") (pinfunction "-_NEG") (pintype "passive"))
      (node (ref "C86") (pin "NEG") (pinfunction "-_NEG") (pintype "passive"))
      (node (ref "C87") (pin "NEG") (pinfunction "-_NEG") (pintype "passive"))
      (node (ref "C88") (pin "1") (pinfunction "1_1") (pintype "passive"))
      (node (ref "C89") (pin "2") (pinfunction "2_2") (pintype "passive"))
      (node (ref "C9") (pin "2") (pinfunction "2_2") (pintype "passive"))
      (node (ref "C90") (pin "2") (pinfunction "2_2") (pintype "passive"))
      (node (ref "C91") (pin "2") (pinfunction "2_2") (pintype "passive"))
      (node (ref "C92") (pin "2") (pinfunction "2_2") (pintype "passive"))
      (node (ref "C93") (pin "2") (pinfunction "2_2") (pintype "passive"))
      (node (ref "C94") (pin "2") (pinfunction "2_2") (pintype "passive"))
      (node (ref "C95") (pin "2") (pinfunction "2_2") (pintype "passive"))
      (node (ref "C96") (pin "2") (pinfunction "2_2") (pintype "passive"))
      (node (ref "D5") (pin "A") (pinfunction "A_A") (pintype "passive"))
      (node (ref "D6") (pin "THERM") (pinfunction "HEAT_THERM") (pintype "bidirectional"))
      (node (ref "D6") (pin "THERM1") (pinfunction "HEAT_THERM1") (pintype "bidirectional"))
      (node (ref "D6") (pin "THERM10") (pinfunction "HEAT_THERM10") (pintype "bidirectional"))
      (node (ref "D6") (pin "THERM11") (pinfunction "HEAT_THERM11") (pintype "bidirectional"))
      (node (ref "D6") (pin "THERM2") (pinfunction "HEAT_THERM2") (pintype "bidirectional"))
      (node (ref "D6") (pin "THERM3") (pinfunction "HEAT_THERM3") (pintype "bidirectional"))
      (node (ref "D6") (pin "THERM4") (pinfunction "HEAT_THERM4") (pintype "bidirectional"))
      (node (ref "D6") (pin "THERM5") (pinfunction "HEAT_THERM5") (pintype "bidirectional"))
      (node (ref "D6") (pin "THERM6") (pinfunction "HEAT_THERM6") (pintype "bidirectional"))
      (node (ref "D6") (pin "THERM7") (pinfunction "HEAT_THERM7") (pintype "bidirectional"))
      (node (ref "D6") (pin "THERM8") (pinfunction "HEAT_THERM8") (pintype "bidirectional"))
      (node (ref "D6") (pin "THERM9") (pinfunction "HEAT_THERM9") (pintype "bidirectional"))
      (node (ref "J1") (pin "5") (pinfunction "GND_5") (pintype "bidirectional"))
      (node (ref "J1") (pin "CASE1") (pinfunction "MTN4_CASE1") (pintype "bidirectional"))
      (node (ref "J1") (pin "CASE2") (pinfunction "MTN4_CASE2") (pintype "bidirectional"))
      (node (ref "J1") (pin "CASE3") (pinfunction "MTN4_CASE3") (pintype "bidirectional"))
      (node (ref "J1") (pin "CASE4") (pinfunction "MTN4_CASE4") (pintype "bidirectional"))
      (node (ref "J1") (pin "CASE5") (pinfunction "MTN4_CASE5") (pintype "bidirectional"))
      (node (ref "J1") (pin "CASE6") (pinfunction "MTN4_CASE6") (pintype "bidirectional"))
      (node (ref "J10") (pin "5") (pinfunction "5_5") (pintype "passive"))
      (node (ref "J11") (pin "4") (pinfunction "4_4") (pintype "passive"))
      (node (ref "J6") (pin "3") (pinfunction "GND_3") (pintype "bidirectional"))
      (node (ref "J6") (pin "9") (pinfunction "GND_9") (pintype "bidirectional"))
      (node (ref "J7") (pin "3") (pinfunction "GND_3") (pintype "bidirectional"))
      (node (ref "J7") (pin "9") (pinfunction "GND_9") (pintype "bidirectional"))
      (node (ref "Q10") (pin "S1") (pinfunction "S_S1") (pintype "passive"))
      (node (ref "Q10") (pin "S2") (pinfunction "S_S2") (pintype "passive"))
      (node (ref "Q10") (pin "S3") (pinfunction "S_S3") (pintype "passive"))
      (node (ref "Q11") (pin "2") (pinfunction "S_2") (pintype "passive"))
      (node (ref "Q8") (pin "2") (pinfunction "S_2") (pintype "passive"))
      (node (ref "Q9") (pin "2") (pinfunction "S_2") (pintype "passive"))
      (node (ref "R110") (pin "1") (pinfunction "1_1") (pintype "passive"))
      (node (ref "R112") (pin "1") (pinfunction "1_1") (pintype "passive"))
      (node (ref "R114") (pin "1") (pinfunction "1_1") (pintype "passive"))
      (node (ref "R12") (pin "1") (pinfunction "1_1") (pintype "passive"))
      (node (ref "R120") (pin "1") (pinfunction "1_1") (pintype "passive"))
      (node (ref "R122") (pin "1") (pinfunction "1_1") (pintype "passive"))
      (node (ref "R16") (pin "1") (pinfunction "1_1") (pintype "passive"))
      (node (ref "R18") (pin "1") (pinfunction "1_1") (pintype "passive"))
      (node (ref "R19") (pin "1") (pinfunction "1_1") (pintype "passive"))
      (node (ref "R22") (pin "I2") (pinfunction "2_I2") (pintype "passive"))
      (node (ref "R27") (pin "I2") (pinfunction "2_I2") (pintype "passive"))
      (node (ref "R3") (pin "1") (pinfunction "1_1") (pintype "passive"))
      (node (ref "R30") (pin "I2") (pinfunction "2_I2") (pintype "passive"))
      (node (ref "R31") (pin "1") (pinfunction "1_1") (pintype "passive"))
      (node (ref "R32") (pin "1") (pinfunction "1_1") (pintype "passive"))
      (node (ref "R36") (pin "1") (pinfunction "1_1") (pintype "passive"))
      (node (ref "R39") (pin "1") (pinfunction "1_1") (pintype "passive"))
      (node (ref "R5") (pin "1") (pinfunction "1_1") (pintype "passive"))
      (node (ref "R6") (pin "1") (pinfunction "1_1") (pintype "passive"))
      (node (ref "R66") (pin "1") (pinfunction "1_1") (pintype "passive"))
      (node (ref "R68") (pin "1") (pinfunction "1_1") (pintype "passive"))
      (node (ref "R70") (pin "1") (pinfunction "1_1") (pintype "passive"))
      (node (ref "R72") (pin "1") (pinfunction "1_1") (pintype "passive"))
      (node (ref "R74") (pin "1") (pinfunction "1_1") (pintype "passive"))
      (node (ref "R79") (pin "1") (pinfunction "1_1") (pintype "passive"))
      (node (ref "R8") (pin "1") (pinfunction "1_1") (pintype "passive"))
      (node (ref "R83") (pin "1") (pinfunction "1_1") (pintype "passive"))
      (node (ref "R84") (pin "1") (pinfunction "1_1") (pintype "passive"))
      (node (ref "R85") (pin "1") (pinfunction "1_1") (pintype "passive"))
      (node (ref "R91") (pin "2") (pinfunction "2_2") (pintype "passive"))
      (node (ref "R92") (pin "2") (pinfunction "2_2") (pintype "passive"))
      (node (ref "S1") (pin "1") (pinfunction "1_1") (pintype "passive"))
      (node (ref "S1") (pin "3") (pinfunction "2_3") (pintype "passive"))
      (node (ref "U1") (pin "32") (pinfunction "GND_32") (pintype "bidirectional"))
      (node (ref "U10") (pin "28") (pinfunction "AGND_28") (pintype "bidirectional"))
      (node (ref "U10") (pin "57") (pinfunction "GND_57") (pintype "bidirectional"))
      (node (ref "U10") (pin "P$100") (pinfunction "GND_P$100") (pintype "bidirectional"))
      (node (ref "U10") (pin "P$101") (pinfunction "GND_P$101") (pintype "bidirectional"))
      (node (ref "U10") (pin "P$58") (pinfunction "GND_P$58") (pintype "bidirectional"))
      (node (ref "U10") (pin "P$59") (pinfunction "GND_P$59") (pintype "bidirectional"))
      (node (ref "U10") (pin "P$60") (pinfunction "GND_P$60") (pintype "bidirectional"))
      (node (ref "U10") (pin "P$61") (pinfunction "GND_P$61") (pintype "bidirectional"))
      (node (ref "U10") (pin "P$62") (pinfunction "GND_P$62") (pintype "bidirectional"))
      (node (ref "U10") (pin "P$63") (pinfunction "GND_P$63") (pintype "bidirectional"))
      (node (ref "U10") (pin "P$64") (pinfunction "GND_P$64") (pintype "bidirectional"))
      (node (ref "U10") (pin "P$65") (pinfunction "GND_P$65") (pintype "bidirectional"))
      (node (ref "U10") (pin "P$66") (pinfunction "GND_P$66") (pintype "bidirectional"))
      (node (ref "U10") (pin "P$67") (pinfunction "GND_P$67") (pintype "bidirectional"))
      (node (ref "U10") (pin "P$68") (pinfunction "GND_P$68") (pintype "bidirectional"))
      (node (ref "U10") (pin "P$69") (pinfunction "GND_P$69") (pintype "bidirectional"))
      (node (ref "U10") (pin "P$70") (pinfunction "GND_P$70") (pintype "bidirectional"))
      (node (ref "U10") (pin "P$71") (pinfunction "GND_P$71") (pintype "bidirectional"))
      (node (ref "U10") (pin "P$72") (pinfunction "GND_P$72") (pintype "bidirectional"))
      (node (ref "U10") (pin "P$73") (pinfunction "GND_P$73") (pintype "bidirectional"))
      (node (ref "U10") (pin "P$74") (pinfunction "GND_P$74") (pintype "bidirectional"))
      (node (ref "U10") (pin "P$75") (pinfunction "GND_P$75") (pintype "bidirectional"))
      (node (ref "U10") (pin "P$76") (pinfunction "GND_P$76") (pintype "bidirectional"))
      (node (ref "U10") (pin "P$77") (pinfunction "GND_P$77") (pintype "bidirectional"))
      (node (ref "U10") (pin "P$78") (pinfunction "GND_P$78") (pintype "bidirectional"))
      (node (ref "U10") (pin "P$79") (pinfunction "GND_P$79") (pintype "bidirectional"))
      (node (ref "U10") (pin "P$80") (pinfunction "GND_P$80") (pintype "bidirectional"))
      (node (ref "U10") (pin "P$81") (pinfunction "GND_P$81") (pintype "bidirectional"))
      (node (ref "U10") (pin "P$82") (pinfunction "GND_P$82") (pintype "bidirectional"))
      (node (ref "U10") (pin "P$83") (pinfunction "GND_P$83") (pintype "bidirectional"))
      (node (ref "U10") (pin "P$84") (pinfunction "GND_P$84") (pintype "bidirectional"))
      (node (ref "U10") (pin "P$85") (pinfunction "GND_P$85") (pintype "bidirectional"))
      (node (ref "U10") (pin "P$86") (pinfunction "GND_P$86") (pintype "bidirectional"))
      (node (ref "U10") (pin "P$87") (pinfunction "GND_P$87") (pintype "bidirectional"))
      (node (ref "U10") (pin "P$88") (pinfunction "GND_P$88") (pintype "bidirectional"))
      (node (ref "U10") (pin "P$89") (pinfunction "GND_P$89") (pintype "bidirectional"))
      (node (ref "U10") (pin "P$90") (pinfunction "GND_P$90") (pintype "bidirectional"))
      (node (ref "U10") (pin "P$91") (pinfunction "GND_P$91") (pintype "bidirectional"))
      (node (ref "U10") (pin "P$92") (pinfunction "GND_P$92") (pintype "bidirectional"))
      (node (ref "U10") (pin "P$93") (pinfunction "GND_P$93") (pintype "bidirectional"))
      (node (ref "U10") (pin "P$94") (pinfunction "GND_P$94") (pintype "bidirectional"))
      (node (ref "U10") (pin "P$95") (pinfunction "GND_P$95") (pintype "bidirectional"))
      (node (ref "U10") (pin "P$96") (pinfunction "GND_P$96") (pintype "bidirectional"))
      (node (ref "U10") (pin "P$97") (pinfunction "GND_P$97") (pintype "bidirectional"))
      (node (ref "U10") (pin "P$98") (pinfunction "GND_P$98") (pintype "bidirectional"))
      (node (ref "U10") (pin "P$99") (pinfunction "GND_P$99") (pintype "bidirectional"))
      (node (ref "U11") (pin "4") (pinfunction "V-_4") (pintype "bidirectional"))
      (node (ref "U12") (pin "2") (pinfunction "V-_2") (pintype "bidirectional"))
      (node (ref "U13") (pin "18") (pinfunction "COM2_18") (pintype "bidirectional"))
      (node (ref "U13") (pin "2") (pinfunction "GND_2") (pintype "bidirectional"))
      (node (ref "U13") (pin "25") (pinfunction "GNDIO_25") (pintype "bidirectional"))
      (node (ref "U14") (pin "A1") (pinfunction "GND_A1") (pintype "bidirectional"))
      (node (ref "U14") (pin "A2") (pinfunction "GND_A2") (pintype "bidirectional"))
      (node (ref "U14") (pin "B1") (pinfunction "GND_B1") (pintype "bidirectional"))
      (node (ref "U2") (pin "17") (pinfunction "GND_17") (pintype "bidirectional"))
      (node (ref "U2") (pin "20") (pinfunction "GND_20") (pintype "bidirectional"))
      (node (ref "U2") (pin "24") (pinfunction "GND_24") (pintype "bidirectional"))
      (node (ref "U2") (pin "26") (pinfunction "TEST_26") (pintype "input"))
      (node (ref "U2") (pin "4") (pinfunction "GND_4") (pintype "bidirectional"))
      (node (ref "U3") (pin "2") (pinfunction "GND_2") (pintype "bidirectional"))
      (node (ref "U4") (pin "2") (pinfunction "VSS_2") (pintype "bidirectional"))
      (node (ref "U5") (pin "15") (pinfunction "VSS_15") (pintype "bidirectional"))
      (node (ref "U5") (pin "26") (pinfunction "VSSA_26") (pintype "bidirectional"))
      (node (ref "U5") (pin "27") (pinfunction "VREFLO_27") (pintype "bidirectional"))
      (node (ref "U5") (pin "36") (pinfunction "VSS_36") (pintype "bidirectional"))
      (node (ref "U5") (pin "4") (pinfunction "VSS_4") (pintype "bidirectional"))
      (node (ref "U5") (pin "47") (pinfunction "VSS_47") (pintype "bidirectional"))
      (node (ref "U5") (pin "62") (pinfunction "VSS_62") (pintype "bidirectional"))
      (node (ref "U5") (pin "80") (pinfunction "VSS_80") (pintype "bidirectional"))
      (node (ref "U5") (pin "90") (pinfunction "~{VREGENZ}_90") (pintype "bidirectional"))
      (node (ref "U5") (pin "92") (pinfunction "VSS_92") (pintype "bidirectional"))
      (node (ref "U6") (pin "13") (pinfunction "GND_13") (pintype "bidirectional"))
      (node (ref "U6") (pin "4") (pinfunction "GND_4") (pintype "bidirectional"))
      (node (ref "U6") (pin "PAD") (pinfunction "GND_PAD") (pintype "bidirectional"))
      (node (ref "U6") (pin "THERM1") (pinfunction "GND_THERM1") (pintype "bidirectional"))
      (node (ref "U6") (pin "THERM2") (pinfunction "GND_THERM2") (pintype "bidirectional"))
      (node (ref "U6") (pin "THERM3") (pinfunction "GND_THERM3") (pintype "bidirectional"))
      (node (ref "U6") (pin "THERM4") (pinfunction "GND_THERM4") (pintype "bidirectional"))
      (node (ref "U7") (pin "13") (pinfunction "GND_13") (pintype "bidirectional"))
      (node (ref "U7") (pin "4") (pinfunction "GND_4") (pintype "bidirectional"))
      (node (ref "U7") (pin "PAD") (pinfunction "GND_PAD") (pintype "bidirectional"))
      (node (ref "U7") (pin "THERM1") (pinfunction "GND_THERM1") (pintype "bidirectional"))
      (node (ref "U7") (pin "THERM2") (pinfunction "GND_THERM2") (pintype "bidirectional"))
      (node (ref "U7") (pin "THERM3") (pinfunction "GND_THERM3") (pintype "bidirectional"))
      (node (ref "U7") (pin "THERM4") (pinfunction "GND_THERM4") (pintype "bidirectional"))
      (node (ref "U8") (pin "13") (pinfunction "GND_13") (pintype "bidirectional"))
      (node (ref "U8") (pin "4") (pinfunction "GND_4") (pintype "bidirectional"))
      (node (ref "U8") (pin "PAD") (pinfunction "GND_PAD") (pintype "bidirectional"))
      (node (ref "U8") (pin "THERM1") (pinfunction "GND_THERM1") (pintype "bidirectional"))
      (node (ref "U8") (pin "THERM2") (pinfunction "GND_THERM2") (pintype "bidirectional"))
      (node (ref "U8") (pin "THERM3") (pinfunction "GND_THERM3") (pintype "bidirectional"))
      (node (ref "U8") (pin "THERM4") (pinfunction "GND_THERM4") (pintype "bidirectional"))
      (node (ref "U9") (pin "13") (pinfunction "GND_13") (pintype "bidirectional"))
      (node (ref "U9") (pin "4") (pinfunction "GND_4") (pintype "bidirectional"))
      (node (ref "U9") (pin "PAD") (pinfunction "GND_PAD") (pintype "bidirectional"))
      (node (ref "U9") (pin "THERM1") (pinfunction "GND_THERM1") (pintype "bidirectional"))
      (node (ref "U9") (pin "THERM2") (pinfunction "GND_THERM2") (pintype "bidirectional"))
      (node (ref "U9") (pin "THERM3") (pinfunction "GND_THERM3") (pintype "bidirectional"))
      (node (ref "U9") (pin "THERM4") (pinfunction "GND_THERM4") (pintype "bidirectional"))
      (node (ref "VR1") (pin "3") (pinfunction "2_3") (pintype "passive"))
      (node (ref "Y1") (pin "2") (pinfunction "2_2") (pintype "passive"))
      (node (ref "Y1") (pin "3") (pinfunction "2_3") (pintype "passive"))
    )
    (net (code "37") (name "GPIO_34") (class "Default")
      (node (ref "R121") (pin "1") (pinfunction "1_1") (pintype "passive"))
      (node (ref "R122") (pin "2") (pinfunction "2_2") (pintype "passive"))
      (node (ref "U5") (pin "68") (pinfunction "GPIO34/COMP2OUT/COMP3OUT_68") (pintype "bidirectional"))
    )
    (net (code "38") (name "I2C_SCL") (class "Default")
      (node (ref "R88") (pin "1") (pinfunction "1_1") (pintype "passive"))
      (node (ref "U1") (pin "17") (pinfunction "I2C_SCL_17") (pintype "bidirectional"))
      (node (ref "U13") (pin "19") (pinfunction "COM1_19") (pintype "bidirectional"))
    )
    (net (code "39") (name "I2C_SDA") (class "Default")
      (node (ref "R87") (pin "1") (pinfunction "1_1") (pintype "passive"))
      (node (ref "U1") (pin "18") (pinfunction "I2C_SDA_18") (pintype "bidirectional"))
      (node (ref "U13") (pin "20") (pinfunction "COM0_20") (pintype "bidirectional"))
    )
    (net (code "40") (name "IA_FB") (class "Default")
      (node (ref "C63") (pin "1") (pinfunction "1_1") (pintype "passive"))
      (node (ref "R47") (pin "2") (pinfunction "2_2") (pintype "passive"))
      (node (ref "R75") (pin "2") (pinfunction "2_2") (pintype "passive"))
    )
    (net (code "41") (name "IB_FB") (class "Default")
      (node (ref "C64") (pin "1") (pinfunction "1_1") (pintype "passive"))
      (node (ref "R48") (pin "2") (pinfunction "2_2") (pintype "passive"))
      (node (ref "R76") (pin "2") (pinfunction "2_2") (pintype "passive"))
    )
    (net (code "42") (name "IC_FB") (class "Default")
      (node (ref "C65") (pin "1") (pinfunction "1_1") (pintype "passive"))
      (node (ref "R49") (pin "2") (pinfunction "2_2") (pintype "passive"))
      (node (ref "R77") (pin "2") (pinfunction "2_2") (pintype "passive"))
    )
    (net (code "43") (name "LED_PWM") (class "Default")
      (node (ref "Q8") (pin "1") (pinfunction "G_1") (pintype "passive"))
      (node (ref "U1") (pin "7") (pinfunction "B5_7") (pintype "bidirectional"))
    )
    (net (code "44") (name "MODE1") (class "Default")
      (node (ref "R7") (pin "1") (pinfunction "1_1") (pintype "passive"))
      (node (ref "U6") (pin "2") (pinfunction "MODE1_2") (pintype "bidirectional"))
      (node (ref "U7") (pin "2") (pinfunction "MODE1_2") (pintype "bidirectional"))
      (node (ref "U8") (pin "2") (pinfunction "MODE1_2") (pintype "bidirectional"))
    )
    (net (code "45") (name "MODE2") (class "Default")
      (node (ref "R8") (pin "2") (pinfunction "2_2") (pintype "passive"))
      (node (ref "U6") (pin "16") (pinfunction "MODE2_16") (pintype "bidirectional"))
      (node (ref "U7") (pin "16") (pinfunction "MODE2_16") (pintype "bidirectional"))
      (node (ref "U8") (pin "16") (pinfunction "MODE2_16") (pintype "bidirectional"))
    )
    (net (code "46") (name "Net-(C43-Pad1)") (class "Default")
      (node (ref "C43") (pin "1") (pinfunction "1_1") (pintype "passive"))
      (node (ref "D5") (pin "C") (pinfunction "C_C") (pintype "passive"))
      (node (ref "L2") (pin "2") (pinfunction "2_2") (pintype "passive"))
      (node (ref "U10") (pin "50") (pinfunction "PH_50") (pintype "bidirectional"))
      (node (ref "U10") (pin "51") (pinfunction "PH_51") (pintype "bidirectional"))
    )
    (net (code "47") (name "Net-(C50-Pad1)") (class "Default")
      (node (ref "C50") (pin "1") (pinfunction "1_1") (pintype "passive"))
      (node (ref "R34") (pin "1") (pinfunction "1_1") (pintype "passive"))
    )
    (net (code "48") (name "Net-(D1-PadCATHODE)") (class "Default")
      (node (ref "D1") (pin "CATHODE") (pinfunction "CATHODE_CATHODE") (pintype "bidirectional"))
      (node (ref "R1") (pin "2") (pinfunction "2_2") (pintype "passive"))
    )
    (net (code "49") (name "Net-(D2-PadCATHODE)") (class "Default")
      (node (ref "D2") (pin "CATHODE") (pinfunction "CATHODE_CATHODE") (pintype "bidirectional"))
      (node (ref "R2") (pin "2") (pinfunction "2_2") (pintype "passive"))
    )
    (net (code "50") (name "Net-(D3-PadCATHODE)") (class "Default")
      (node (ref "D3") (pin "CATHODE") (pinfunction "CATHODE_CATHODE") (pintype "bidirectional"))
      (node (ref "R3") (pin "2") (pinfunction "2_2") (pintype "passive"))
    )
    (net (code "51") (name "Net-(D4-PadANODE)") (class "Default")
      (node (ref "D4") (pin "ANODE") (pinfunction "ANODE_ANODE") (pintype "bidirectional"))
      (node (ref "R4") (pin "1") (pinfunction "1_1") (pintype "passive"))
    )
    (net (code "52") (name "Net-(D6-PadCATHODE)") (class "Default")
      (node (ref "D6") (pin "CATHODE") (pinfunction "CATHODE_CATHODE") (pintype "bidirectional"))
      (node (ref "Q7") (pin "D") (pinfunction "D_D") (pintype "passive"))
    )
    (net (code "53") (name "Net-(J1-D+)") (class "Default")
      (node (ref "J1") (pin "3") (pinfunction "D+_3") (pintype "bidirectional"))
      (node (ref "U2") (pin "14") (pinfunction "USBDP_14") (pintype "bidirectional"))
    )
    (net (code "54") (name "Net-(J1-D-)") (class "Default")
      (node (ref "J1") (pin "2") (pinfunction "D-_2") (pintype "bidirectional"))
      (node (ref "U2") (pin "15") (pinfunction "USBDM_15") (pintype "bidirectional"))
    )
    (net (code "55") (name "Net-(J1-VBUS)") (class "Default")
      (node (ref "C10") (pin "1") (pinfunction "1_1") (pintype "passive"))
      (node (ref "J1") (pin "1") (pinfunction "VBUS_1") (pintype "bidirectional"))
      (node (ref "L1") (pin "1") (pinfunction "1_1") (pintype "passive"))
    )
    (net (code "56") (name "Net-(J5-2-PadN)") (class "Default")
      (node (ref "J5") (pin "N") (pinfunction "2_N") (pintype "passive"))
      (node (ref "J5") (pin "N2") (pinfunction "2_N2") (pintype "passive"))
      (node (ref "J9") (pin "2") (pinfunction "2_2") (pintype "passive"))
      (node (ref "Q10") (pin "D") (pinfunction "D_D") (pintype "passive"))
      (node (ref "R92") (pin "1") (pinfunction "1_1") (pintype "passive"))
    )
    (net (code "57") (name "Net-(J6-TCK)") (class "Default")
      (node (ref "J6") (pin "4") (pinfunction "TCK_4") (pintype "bidirectional"))
      (node (ref "U1") (pin "4") (pinfunction "TCK_4") (pintype "bidirectional"))
    )
    (net (code "58") (name "Net-(J6-TDI)") (class "Default")
      (node (ref "J6") (pin "8") (pinfunction "TDI_8") (pintype "bidirectional"))
      (node (ref "U1") (pin "6") (pinfunction "B6_6") (pintype "bidirectional"))
    )
    (net (code "59") (name "Net-(J6-TDO)") (class "Default")
      (node (ref "J6") (pin "6") (pinfunction "TDO_6") (pintype "bidirectional"))
      (node (ref "U1") (pin "5") (pinfunction "TDO_5") (pintype "bidirectional"))
    )
    (net (code "60") (name "Net-(J6-TMS)") (class "Default")
      (node (ref "J6") (pin "2") (pinfunction "TMS_2") (pintype "bidirectional"))
      (node (ref "U1") (pin "3") (pinfunction "TMS_3") (pintype "bidirectional"))
    )
    (net (code "61") (name "Net-(J7-RESET)") (class "Default")
      (node (ref "J7") (pin "10") (pinfunction "RESET_10") (pintype "bidirectional"))
      (node (ref "U5") (pin "12") (pinfunction "~{TRST}_12") (pintype "bidirectional"))
    )
    (net (code "62") (name "Net-(J7-TCK)") (class "Default")
      (node (ref "J7") (pin "4") (pinfunction "TCK_4") (pintype "bidirectional"))
      (node (ref "U5") (pin "67") (pinfunction "TCK/GPIO38/XCLK_I_67") (pintype "bidirectional"))
    )
    (net (code "63") (name "Net-(J7-TDI)") (class "Default")
      (node (ref "J7") (pin "8") (pinfunction "TDI_8") (pintype "bidirectional"))
      (node (ref "U5") (pin "71") (pinfunction "TDI/GPIO35_71") (pintype "bidirectional"))
    )
    (net (code "64") (name "Net-(J7-TMS)") (class "Default")
      (node (ref "J7") (pin "2") (pinfunction "TMS_2") (pintype "bidirectional"))
      (node (ref "U5") (pin "72") (pinfunction "TMS/GPIO36_72") (pintype "bidirectional"))
    )
    (net (code "65") (name "Net-(J7-VCC)") (class "Default")
      (node (ref "C72") (pin "1") (pinfunction "1_1") (pintype "passive"))
      (node (ref "C73") (pin "1") (pinfunction "1_1") (pintype "passive"))
      (node (ref "C74") (pin "1") (pinfunction "1_1") (pintype "passive"))
      (node (ref "C75") (pin "1") (pinfunction "1_1") (pintype "passive"))
      (node (ref "C76") (pin "1") (pinfunction "1_1") (pintype "passive"))
      (node (ref "C77") (pin "1") (pinfunction "1_1") (pintype "passive"))
      (node (ref "J7") (pin "1") (pinfunction "VCC_1") (pintype "bidirectional"))
      (node (ref "L3") (pin "2") (pinfunction "2_2") (pintype "passive"))
      (node (ref "U5") (pin "13") (pinfunction "VDDIO_13") (pintype "bidirectional"))
      (node (ref "U5") (pin "38") (pinfunction "VDDIO_38") (pintype "bidirectional"))
      (node (ref "U5") (pin "5") (pinfunction "VDDIO_5") (pintype "bidirectional"))
      (node (ref "U5") (pin "61") (pinfunction "VDDIO_61") (pintype "bidirectional"))
      (node (ref "U5") (pin "79") (pinfunction "VDDIO_79") (pintype "bidirectional"))
      (node (ref "U5") (pin "93") (pinfunction "VDDIO_93") (pintype "bidirectional"))
    )
    (net (code "66") (name "Net-(J10-Pad1)") (class "Default")
      (node (ref "J10") (pin "1") (pinfunction "1_1") (pintype "passive"))
      (node (ref "R109") (pin "2") (pinfunction "2_2") (pintype "passive"))
    )
    (net (code "67") (name "Net-(J10-Pad3)") (class "Default")
      (node (ref "J10") (pin "3") (pinfunction "3_3") (pintype "passive"))
      (node (ref "R111") (pin "2") (pinfunction "2_2") (pintype "passive"))
    )
    (net (code "68") (name "Net-(J10-Pad4)") (class "Default")
      (node (ref "J10") (pin "4") (pinfunction "4_4") (pintype "passive"))
      (node (ref "R113") (pin "2") (pinfunction "2_2") (pintype "passive"))
    )
    (net (code "69") (name "Net-(Q1-PadG)") (class "Default")
      (node (ref "Q1") (pin "G") (pinfunction "G_G") (pintype "passive"))
      (node (ref "R23") (pin "2") (pinfunction "2_2") (pintype "passive"))
    )
    (net (code "70") (name "Net-(Q2-PadG)") (class "Default")
      (node (ref "Q2") (pin "G") (pinfunction "G_G") (pintype "passive"))
      (node (ref "R24") (pin "2") (pinfunction "2_2") (pintype "passive"))
    )
    (net (code "71") (name "Net-(Q3-PadG)") (class "Default")
      (node (ref "Q3") (pin "G") (pinfunction "G_G") (pintype "passive"))
      (node (ref "R25") (pin "2") (pinfunction "2_2") (pintype "passive"))
    )
    (net (code "72") (name "Net-(Q4-PadG)") (class "Default")
      (node (ref "Q4") (pin "G") (pinfunction "G_G") (pintype "passive"))
      (node (ref "R26") (pin "2") (pinfunction "2_2") (pintype "passive"))
    )
    (net (code "73") (name "Net-(Q5-PadG)") (class "Default")
      (node (ref "Q5") (pin "G") (pinfunction "G_G") (pintype "passive"))
      (node (ref "R28") (pin "2") (pinfunction "2_2") (pintype "passive"))
    )
    (net (code "74") (name "Net-(Q6-PadG)") (class "Default")
      (node (ref "Q6") (pin "G") (pinfunction "G_G") (pintype "passive"))
      (node (ref "R29") (pin "2") (pinfunction "2_2") (pintype "passive"))
    )
    (net (code "75") (name "Net-(Q7-PadG)") (class "Default")
      (node (ref "Q7") (pin "G") (pinfunction "G_G") (pintype "passive"))
      (node (ref "R80") (pin "1") (pinfunction "1_1") (pintype "passive"))
    )
    (net (code "76") (name "Net-(Q7-S-PadS1)") (class "Default")
      (node (ref "Q7") (pin "S1") (pinfunction "S_S1") (pintype "passive"))
      (node (ref "Q7") (pin "S2") (pinfunction "S_S2") (pintype "passive"))
      (node (ref "Q7") (pin "S3") (pinfunction "S_S3") (pintype "passive"))
      (node (ref "R79") (pin "2") (pinfunction "2_2") (pintype "passive"))
      (node (ref "R81") (pin "1") (pinfunction "1_1") (pintype "passive"))
    )
    (net (code "77") (name "Net-(Q8-D)") (class "Default")
      (node (ref "Q8") (pin "3") (pinfunction "D_3") (pintype "passive"))
      (node (ref "U12") (pin "3") (pinfunction "+IN_3") (pintype "input"))
      (node (ref "VR1") (pin "2") (pinfunction "WIPER_2") (pintype "passive"))
    )
    (net (code "78") (name "Net-(Q9-D)") (class "Default")
      (node (ref "Q9") (pin "3") (pinfunction "D_3") (pintype "passive"))
      (node (ref "R89") (pin "1") (pinfunction "1_1") (pintype "passive"))
      (node (ref "U3") (pin "3") (pinfunction "EN_3") (pintype "bidirectional"))
    )
    (net (code "79") (name "Net-(Q9-G)") (class "Default")
      (node (ref "Q9") (pin "1") (pinfunction "G_1") (pintype "passive"))
      (node (ref "R90") (pin "1") (pinfunction "1_1") (pintype "passive"))
    )
    (net (code "80") (name "Net-(Q11-D)") (class "Default")
      (node (ref "J4") (pin "2") (pinfunction "2_2") (pintype "passive"))
      (node (ref "Q11") (pin "3") (pinfunction "D_3") (pintype "passive"))
      (node (ref "R91") (pin "1") (pinfunction "1_1") (pintype "passive"))
    )
    (net (code "81") (name "Net-(R22-1)") (class "Default")
      (node (ref "Q2") (pin "S1") (pinfunction "S_S1") (pintype "passive"))
      (node (ref "Q2") (pin "S2") (pinfunction "S_S2") (pintype "passive"))
      (node (ref "Q2") (pin "S3") (pinfunction "S_S3") (pintype "passive"))
      (node (ref "R22") (pin "I1") (pinfunction "1_I1") (pintype "passive"))
      (node (ref "U10") (pin "44") (pinfunction "SL_A_44") (pintype "bidirectional"))
    )
    (net (code "82") (name "Net-(R27-1)") (class "Default")
      (node (ref "Q4") (pin "S1") (pinfunction "S_S1") (pintype "passive"))
      (node (ref "Q4") (pin "S2") (pinfunction "S_S2") (pintype "passive"))
      (node (ref "Q4") (pin "S3") (pinfunction "S_S3") (pintype "passive"))
      (node (ref "R27") (pin "I1") (pinfunction "1_I1") (pintype "passive"))
      (node (ref "U10") (pin "39") (pinfunction "SL_B_39") (pintype "bidirectional"))
    )
    (net (code "83") (name "Net-(R30-1)") (class "Default")
      (node (ref "Q6") (pin "S1") (pinfunction "S_S1") (pintype "passive"))
      (node (ref "Q6") (pin "S2") (pinfunction "S_S2") (pintype "passive"))
      (node (ref "Q6") (pin "S3") (pinfunction "S_S3") (pintype "passive"))
      (node (ref "R30") (pin "I1") (pinfunction "1_I1") (pintype "passive"))
      (node (ref "U10") (pin "34") (pinfunction "SL_C_34") (pintype "bidirectional"))
    )
    (net (code "84") (name "Net-(R82-Pad2)") (class "Default")
      (node (ref "R82") (pin "2") (pinfunction "2_2") (pintype "passive"))
      (node (ref "VR1") (pin "1") (pinfunction "1_1") (pintype "passive"))
    )
    (net (code "85") (name "Net-(U1-ADC3)") (class "Default")
      (node (ref "C96") (pin "1") (pinfunction "1_1") (pintype "passive"))
      (node (ref "R123") (pin "1") (pinfunction "1_1") (pintype "passive"))
      (node (ref "U1") (pin "25") (pinfunction "ADC3_25") (pintype "bidirectional"))
    )
    (net (code "86") (name "Net-(U1-B3)") (class "Default")
      (node (ref "R106") (pin "2") (pinfunction "2_2") (pintype "passive"))
      (node (ref "U1") (pin "9") (pinfunction "B3_9") (pintype "bidirectional"))
    )
    (net (code "87") (name "Net-(U1-B4)") (class "Default")
      (node (ref "R105") (pin "2") (pinfunction "2_2") (pintype "passive"))
      (node (ref "U1") (pin "8") (pinfunction "B4_8") (pintype "bidirectional"))
    )
    (net (code "88") (name "Net-(U1-C0)") (class "Default")
      (node (ref "R108") (pin "2") (pinfunction "2_2") (pintype "passive"))
      (node (ref "U1") (pin "21") (pinfunction "C0_21") (pintype "bidirectional"))
    )
    (net (code "89") (name "Net-(U1-C1)") (class "Default")
      (node (ref "R107") (pin "2") (pinfunction "2_2") (pintype "passive"))
      (node (ref "U1") (pin "20") (pinfunction "C1_20") (pintype "bidirectional"))
    )
    (net (code "90") (name "Net-(U1-VCC)") (class "Default")
      (node (ref "C94") (pin "1") (pinfunction "1_1") (pintype "passive"))
      (node (ref "L5") (pin "2") (pinfunction "2_2") (pintype "passive"))
      (node (ref "U1") (pin "1") (pinfunction "VCC_1") (pintype "bidirectional"))
    )
    (net (code "91") (name "Net-(U2-CBUS0)") (class "Default")
      (node (ref "R1") (pin "1") (pinfunction "1_1") (pintype "passive"))
      (node (ref "U2") (pin "22") (pinfunction "CBUS0_22") (pintype "bidirectional"))
    )
    (net (code "92") (name "Net-(U2-CBUS1)") (class "Default")
      (node (ref "R2") (pin "1") (pinfunction "1_1") (pintype "passive"))
      (node (ref "U2") (pin "21") (pinfunction "CBUS1_21") (pintype "bidirectional"))
    )
    (net (code "93") (name "Net-(U3-NR)") (class "Default")
      (node (ref "C3") (pin "1") (pinfunction "1_1") (pintype "passive"))
      (node (ref "U3") (pin "4") (pinfunction "NR_4") (pintype "bidirectional"))
    )
    (net (code "94") (name "Net-(U4-PROG)") (class "Default")
      (node (ref "R5") (pin "2") (pinfunction "2_2") (pintype "passive"))
      (node (ref "U4") (pin "5") (pinfunction "PROG_5") (pintype "bidirectional"))
    )
    (net (code "95") (name "Net-(U4-STAT)") (class "Default")
      (node (ref "D4") (pin "CATHODE") (pinfunction "CATHODE_CATHODE") (pintype "bidirectional"))
      (node (ref "U4") (pin "1") (pinfunction "STAT_1") (pintype "bidirectional"))
    )
    (net (code "96") (name "Net-(U5A-ADC_INA3)") (class "Default")
      (node (ref "R47") (pin "1") (pinfunction "1_1") (pintype "passive"))
      (node (ref "U5") (pin "20") (pinfunction "ADC_INA3_20") (pintype "bidirectional"))
    )
    (net (code "97") (name "Net-(U5A-ADC_INA4{slash}COMP2A{slash}AIO4)") (class "Default")
      (node (ref "R49") (pin "1") (pinfunction "1_1") (pintype "passive"))
      (node (ref "U5") (pin "19") (pinfunction "ADC_INA4/COMP2A/AIO4_19") (pintype "bidirectional"))
    )
    (net (code "98") (name "Net-(U5A-ADC_INA5)") (class "Default")
      (node (ref "R45") (pin "1") (pinfunction "1_1") (pintype "passive"))
      (node (ref "U5") (pin "18") (pinfunction "ADC_INA5_18") (pintype "bidirectional"))
    )
    (net (code "99") (name "Net-(U5A-ADC_INA6{slash}COMP3A{slash}AIO6)") (class "Default")
      (node (ref "R96") (pin "1") (pinfunction "1_1") (pintype "passive"))
      (node (ref "U5") (pin "17") (pinfunction "ADC_INA6/COMP3A/AIO6_17") (pintype "bidirectional"))
    )
    (net (code "100") (name "Net-(U5A-ADC_INB0)") (class "Default")
      (node (ref "R95") (pin "1") (pinfunction "1_1") (pintype "passive"))
      (node (ref "U5") (pin "28") (pinfunction "ADC_INB0_28") (pintype "bidirectional"))
    )
    (net (code "101") (name "Net-(U5A-ADC_INB1)") (class "Default")
      (node (ref "R94") (pin "1") (pinfunction "1_1") (pintype "passive"))
      (node (ref "U5") (pin "29") (pinfunction "ADC_INB1_29") (pintype "bidirectional"))
    )
    (net (code "102") (name "Net-(U5A-ADC_INB2{slash}COMP1B{slash}AIO10)") (class "Default")
      (node (ref "R93") (pin "1") (pinfunction "1_1") (pintype "passive"))
      (node (ref "U5") (pin "30") (pinfunction "ADC_INB2/COMP1B/AIO10_30") (pintype "bidirectional"))
    )
    (net (code "103") (name "Net-(U5A-ADC_INB3)") (class "Default")
      (node (ref "R48") (pin "1") (pinfunction "1_1") (pintype "passive"))
      (node (ref "U5") (pin "31") (pinfunction "ADC_INB3_31") (pintype "bidirectional"))
    )
    (net (code "104") (name "Net-(U5A-ADC_INB4{slash}COMP2B{slash}AIO12)") (class "Default")
      (node (ref "R44") (pin "1") (pinfunction "1_1") (pintype "passive"))
      (node (ref "U5") (pin "32") (pinfunction "ADC_INB4/COMP2B/AIO12_32") (pintype "bidirectional"))
    )
    (net (code "105") (name "Net-(U5A-ADC_INB5)") (class "Default")
      (node (ref "R46") (pin "1") (pinfunction "1_1") (pintype "passive"))
      (node (ref "U5") (pin "33") (pinfunction "ADC_INB5_33") (pintype "bidirectional"))
    )
    (net (code "106") (name "Net-(U5A-ADC_INB7)") (class "Default")
      (node (ref "R43") (pin "1") (pinfunction "1_1") (pintype "passive"))
      (node (ref "U5") (pin "35") (pinfunction "ADC_INB7_35") (pintype "bidirectional"))
    )
    (net (code "107") (name "Net-(U5A-VDD1)") (class "Default")
      (node (ref "C66") (pin "1") (pinfunction "1_1") (pintype "passive"))
      (node (ref "U5") (pin "14") (pinfunction "VDD1_14") (pintype "bidirectional"))
    )
    (net (code "108") (name "Net-(U5A-VDD2)") (class "Default")
      (node (ref "C67") (pin "1") (pinfunction "1_1") (pintype "passive"))
      (node (ref "U5") (pin "37") (pinfunction "VDD2_37") (pintype "bidirectional"))
    )
    (net (code "109") (name "Net-(U5A-VDD3)") (class "Default")
      (node (ref "C68") (pin "1") (pinfunction "1_1") (pintype "passive"))
      (node (ref "U5") (pin "63") (pinfunction "VDD3_63") (pintype "bidirectional"))
    )
    (net (code "110") (name "Net-(U5A-VDD4)") (class "Default")
      (node (ref "C69") (pin "1") (pinfunction "1_1") (pintype "passive"))
      (node (ref "U5") (pin "81") (pinfunction "VDD4_81") (pintype "bidirectional"))
    )
    (net (code "111") (name "Net-(U5A-VDD5)") (class "Default")
      (node (ref "C70") (pin "1") (pinfunction "1_1") (pintype "passive"))
      (node (ref "U5") (pin "91") (pinfunction "VDD5_91") (pintype "bidirectional"))
    )
    (net (code "112") (name "Net-(U5A-VDD6)") (class "Default")
      (node (ref "C71") (pin "1") (pinfunction "1_1") (pintype "passive"))
      (node (ref "U5") (pin "3") (pinfunction "VDD6_3") (pintype "bidirectional"))
    )
    (net (code "113") (name "Net-(U5A-VDDA)") (class "Default")
      (node (ref "C78") (pin "1") (pinfunction "1_1") (pintype "passive"))
      (node (ref "L4") (pin "2") (pinfunction "2_2") (pintype "passive"))
      (node (ref "U5") (pin "25") (pinfunction "VDDA_25") (pintype "bidirectional"))
    )
    (net (code "114") (name "Net-(U5B-GPIO0{slash}EPWM1A)") (class "Default")
      (node (ref "R101") (pin "2") (pinfunction "2_2") (pintype "passive"))
      (node (ref "U5") (pin "87") (pinfunction "GPIO0/EPWM1A_87") (pintype "bidirectional"))
    )
    (net (code "115") (name "Net-(U5B-GPIO1{slash}EPWM1B{slash}COMP1OUT)") (class "Default")
      (node (ref "R104") (pin "2") (pinfunction "2_2") (pintype "passive"))
      (node (ref "U5") (pin "86") (pinfunction "GPIO1/EPWM1B/COMP1OUT_86") (pintype "bidirectional"))
    )
    (net (code "116") (name "Net-(U5B-GPIO2{slash}EPWM2A)") (class "Default")
      (node (ref "R103") (pin "2") (pinfunction "2_2") (pintype "passive"))
      (node (ref "U5") (pin "84") (pinfunction "GPIO2/EPWM2A_84") (pintype "bidirectional"))
    )
    (net (code "117") (name "Net-(U5B-GPIO3{slash}EPWM2B{slash}SPISOMIA{slash}COMP2OUT)") (class "Default")
      (node (ref "R102") (pin "2") (pinfunction "2_2") (pintype "passive"))
      (node (ref "U5") (pin "83") (pinfunction "GPIO3/EPWM2B/SPISOMIA/COMP2OUT_83") (pintype "bidirectional"))
    )
    (net (code "118") (name "Net-(U5B-GPIO6{slash}EPWM4A{slash}EPWMSYNCI{slash}EPWMSYNCO)") (class "Default")
      (node (ref "R50") (pin "2") (pinfunction "2_2") (pintype "passive"))
      (node (ref "U5") (pin "58") (pinfunction "GPIO6/EPWM4A/EPWMSYNCI/EPWMSYNCO_58") (pintype "bidirectional"))
    )
    (net (code "119") (name "Net-(U5B-GPIO7{slash}EPWM4B{slash}SCIRXDA{slash}ECAP2)") (class "Default")
      (node (ref "R51") (pin "2") (pinfunction "2_2") (pintype "passive"))
      (node (ref "U5") (pin "57") (pinfunction "GPIO7/EPWM4B/SCIRXDA/ECAP2_57") (pintype "bidirectional"))
    )
    (net (code "120") (name "Net-(U5B-GPIO8{slash}EPWM5A{slash}~{ADCSOCAO})") (class "Default")
      (node (ref "R52") (pin "2") (pinfunction "2_2") (pintype "passive"))
      (node (ref "U5") (pin "54") (pinfunction "GPIO8/EPWM5A/~{ADCSOCAO}_54") (pintype "bidirectional"))
    )
    (net (code "121") (name "Net-(U5B-GPIO9{slash}EPWM5B{slash}SCI_TXDB{slash}ECAP3)") (class "Default")
      (node (ref "R53") (pin "2") (pinfunction "2_2") (pintype "passive"))
      (node (ref "U5") (pin "49") (pinfunction "GPIO9/EPWM5B/SCI_TXDB/ECAP3_49") (pintype "bidirectional"))
    )
    (net (code "122") (name "Net-(U5B-GPIO10{slash}EPWM6A{slash}~{ADCSOCBO})") (class "Default")
      (node (ref "R54") (pin "2") (pinfunction "2_2") (pintype "passive"))
      (node (ref "U5") (pin "74") (pinfunction "GPIO10/EPWM6A/~{ADCSOCBO}_74") (pintype "bidirectional"))
    )
    (net (code "123") (name "Net-(U5B-GPIO11{slash}EPWM6B{slash}SCI_RXDB{slash}ECAP1)") (class "Default")
      (node (ref "R55") (pin "2") (pinfunction "2_2") (pintype "passive"))
      (node (ref "U5") (pin "73") (pinfunction "GPIO11/EPWM6B/SCI_RXDB/ECAP1_73") (pintype "bidirectional"))
    )
    (net (code "124") (name "Net-(U5B-GPIO14{slash}~{TZ3}{slash}SCITXDB{slash}SPICLKB)") (class "Default")
      (node (ref "R41") (pin "2") (pinfunction "2_2") (pintype "passive"))
      (node (ref "U5") (pin "96") (pinfunction "GPIO14/~{TZ3}/SCITXDB/SPICLKB_96") (pintype "bidirectional"))
    )
    (net (code "125") (name "Net-(U5B-GPIO24{slash}ECAP1{slash}EQEP2A{slash}SPISIMOB)") (class "Default")
      (node (ref "R57") (pin "2") (pinfunction "2_2") (pintype "passive"))
      (node (ref "U5") (pin "97") (pinfunction "GPIO24/ECAP1/EQEP2A/SPISIMOB_97") (pintype "bidirectional"))
    )
    (net (code "126") (name "Net-(U5B-GPIO25{slash}ECAP2{slash}EQEP2B{slash}SPISOMIB)") (class "Default")
      (node (ref "R58") (pin "2") (pinfunction "2_2") (pintype "passive"))
      (node (ref "U5") (pin "39") (pinfunction "GPIO25/ECAP2/EQEP2B/SPISOMIB_39") (pintype "bidirectional"))
    )
    (net (code "127") (name "Net-(U5B-GPIO27{slash}HRCAP2{slash}EQEP2S{slash}~{SPISTEB}{slash}USB0DM)") (class "Default")
      (node (ref "R56") (pin "1") (pinfunction "1_1") (pintype "passive"))
      (node (ref "U5") (pin "77") (pinfunction "GPIO27/HRCAP2/EQEP2S/~{SPISTEB}/USB0DM_77") (pintype "bidirectional"))
    )
    (net (code "128") (name "Net-(U5B-GPIO28{slash}SCI_RXDA{slash}SDAA{slash}~{TZ2})") (class "Default")
      (node (ref "R40") (pin "2") (pinfunction "2_2") (pintype "passive"))
      (node (ref "U5") (pin "50") (pinfunction "GPIO28/SCI_RXDA/SDAA/~{TZ2}_50") (pintype "bidirectional"))
    )
    (net (code "129") (name "Net-(U5B-GPIO29{slash}SCI_TXDA{slash}SCLA{slash}~{TZ3})") (class "Default")
      (node (ref "R42") (pin "1") (pinfunction "1_1") (pintype "passive"))
      (node (ref "U5") (pin "43") (pinfunction "GPIO29/SCI_TXDA/SCLA/~{TZ3}_43") (pintype "bidirectional"))
    )
    (net (code "130") (name "Net-(U5B-GPIO31{slash}CAN_TXA{slash}EQEP2S{slash}EPWM8A)") (class "Default")
      (node (ref "R126") (pin "1") (pinfunction "1_1") (pintype "passive"))
      (node (ref "U5") (pin "40") (pinfunction "GPIO31/CAN_TXA/EQEP2S/EPWM8A_40") (pintype "bidirectional"))
    )
    (net (code "131") (name "Net-(U5B-GPIO50{slash}EQEP1A{slash}MDXA{slash}~{TZ1})") (class "Default")
      (node (ref "R125") (pin "1") (pinfunction "1_1") (pintype "passive"))
      (node (ref "U5") (pin "42") (pinfunction "GPIO50/EQEP1A/MDXA/~{TZ1}_42") (pintype "bidirectional"))
    )
    (net (code "132") (name "Net-(U5B-GPIO51{slash}EQEP1B{slash}MDRA{slash}~{TZ2})") (class "Default")
      (node (ref "R124") (pin "1") (pinfunction "1_1") (pintype "passive"))
      (node (ref "U5") (pin "48") (pinfunction "GPIO51/EQEP1B/MDRA/~{TZ2}_48") (pintype "bidirectional"))
    )
    (net (code "133") (name "Net-(U5B-GPIO52{slash}EQEP1S{slash}MCLKXA{slash}~{TZ3})") (class "Default")
      (node (ref "R59") (pin "1") (pinfunction "1_1") (pintype "passive"))
      (node (ref "U5") (pin "53") (pinfunction "GPIO52/EQEP1S/MCLKXA/~{TZ3}_53") (pintype "bidirectional"))
    )
    (net (code "134") (name "Net-(U5B-GPIO53{slash}EQEP1I{slash}MFSXA)") (class "Default")
      (node (ref "R60") (pin "1") (pinfunction "1_1") (pintype "passive"))
      (node (ref "U5") (pin "65") (pinfunction "GPIO53/EQEP1I/MFSXA_65") (pintype "bidirectional"))
    )
    (net (code "135") (name "Net-(U5B-GPIO54{slash}SPISIMOA{slash}EQEP2A{slash}HRCAP1)") (class "Default")
      (node (ref "R115") (pin "1") (pinfunction "1_1") (pintype "passive"))
      (node (ref "U5") (pin "69") (pinfunction "GPIO54/SPISIMOA/EQEP2A/HRCAP1_69") (pintype "bidirectional"))
    )
    (net (code "136") (name "Net-(U5B-GPIO55{slash}SPISOMIA{slash}EQEP2B{slash}HRCAP2)") (class "Default")
      (node (ref "R116") (pin "1") (pinfunction "1_1") (pintype "passive"))
      (node (ref "U5") (pin "75") (pinfunction "GPIO55/SPISOMIA/EQEP2B/HRCAP2_75") (pintype "bidirectional"))
    )
    (net (code "137") (name "Net-(U5B-GPIO56{slash}SPICLKA{slash}EQEP2I{slash}HRCAP3)") (class "Default")
      (node (ref "R118") (pin "1") (pinfunction "1_1") (pintype "passive"))
      (node (ref "U5") (pin "85") (pinfunction "GPIO56/SPICLKA/EQEP2I/HRCAP3_85") (pintype "bidirectional"))
    )
    (net (code "138") (name "Net-(U5B-GPIO57{slash}~{SPISTEA}{slash}EQEP2S{slash}HRCAP4)") (class "Default")
      (node (ref "R117") (pin "1") (pinfunction "1_1") (pintype "passive"))
      (node (ref "U5") (pin "89") (pinfunction "GPIO57/~{SPISTEA}/EQEP2S/HRCAP4_89") (pintype "bidirectional"))
    )
    (net (code "139") (name "Net-(U6-CP1)") (class "Default")
      (node (ref "C11") (pin "1") (pinfunction "1_1") (pintype "passive"))
      (node (ref "U6") (pin "11") (pinfunction "CP1_11") (pintype "bidirectional"))
    )
    (net (code "140") (name "Net-(U6-CP2)") (class "Default")
      (node (ref "C11") (pin "2") (pinfunction "2_2") (pintype "passive"))
      (node (ref "U6") (pin "12") (pinfunction "CP2_12") (pintype "bidirectional"))
    )
    (net (code "141") (name "Net-(U6-OUT+)") (class "Default")
      (node (ref "J2") (pin "1") (pinfunction "1_1") (pintype "passive"))
      (node (ref "U6") (pin "7") (pinfunction "OUT+_7") (pintype "bidirectional"))
    )
    (net (code "142") (name "Net-(U6-OUT-)") (class "Default")
      (node (ref "J2") (pin "2") (pinfunction "2_2") (pintype "passive"))
      (node (ref "U6") (pin "10") (pinfunction "OUT-_10") (pintype "bidirectional"))
    )
    (net (code "143") (name "Net-(U6-SENSE)") (class "Default")
      (node (ref "R6") (pin "2") (pinfunction "2_2") (pintype "passive"))
      (node (ref "U6") (pin "8") (pinfunction "SENSE_8") (pintype "bidirectional"))
    )
    (net (code "144") (name "Net-(U6-VCP)") (class "Default")
      (node (ref "C12") (pin "2") (pinfunction "2_2") (pintype "passive"))
      (node (ref "U6") (pin "14") (pinfunction "VCP_14") (pintype "bidirectional"))
    )
    (net (code "145") (name "Net-(U6-VPROPI)") (class "Default")
      (node (ref "R10") (pin "2") (pinfunction "2_2") (pintype "passive"))
      (node (ref "U6") (pin "15") (pinfunction "VPROPI_15") (pintype "bidirectional"))
    )
    (net (code "146") (name "Net-(U6-~{SLEEP})") (class "Default")
      (node (ref "R99") (pin "1") (pinfunction "1_1") (pintype "passive"))
      (node (ref "U6") (pin "5") (pinfunction "~{SLEEP}_5") (pintype "bidirectional"))
    )
    (net (code "147") (name "Net-(U7-CP1)") (class "Default")
      (node (ref "C14") (pin "1") (pinfunction "1_1") (pintype "passive"))
      (node (ref "U7") (pin "11") (pinfunction "CP1_11") (pintype "bidirectional"))
    )
    (net (code "148") (name "Net-(U7-CP2)") (class "Default")
      (node (ref "C14") (pin "2") (pinfunction "2_2") (pintype "passive"))
      (node (ref "U7") (pin "12") (pinfunction "CP2_12") (pintype "bidirectional"))
    )
    (net (code "149") (name "Net-(U7-OUT+)") (class "Default")
      (node (ref "J2") (pin "3") (pinfunction "3_3") (pintype "passive"))
      (node (ref "U7") (pin "7") (pinfunction "OUT+_7") (pintype "bidirectional"))
    )
    (net (code "150") (name "Net-(U7-OUT-)") (class "Default")
      (node (ref "J2") (pin "4") (pinfunction "4_4") (pintype "passive"))
      (node (ref "U7") (pin "10") (pinfunction "OUT-_10") (pintype "bidirectional"))
    )
    (net (code "151") (name "Net-(U7-SENSE)") (class "Default")
      (node (ref "R12") (pin "2") (pinfunction "2_2") (pintype "passive"))
      (node (ref "U7") (pin "8") (pinfunction "SENSE_8") (pintype "bidirectional"))
    )
    (net (code "152") (name "Net-(U7-VCP)") (class "Default")
      (node (ref "C15") (pin "2") (pinfunction "2_2") (pintype "passive"))
      (node (ref "U7") (pin "14") (pinfunction "VCP_14") (pintype "bidirectional"))
    )
    (net (code "153") (name "Net-(U7-VPROPI)") (class "Default")
      (node (ref "R11") (pin "2") (pinfunction "2_2") (pintype "passive"))
      (node (ref "U7") (pin "15") (pinfunction "VPROPI_15") (pintype "bidirectional"))
    )
    (net (code "154") (name "Net-(U7-~{SLEEP})") (class "Default")
      (node (ref "R97") (pin "1") (pinfunction "1_1") (pintype "passive"))
      (node (ref "U7") (pin "5") (pinfunction "~{SLEEP}_5") (pintype "bidirectional"))
    )
    (net (code "155") (name "Net-(U8-CP1)") (class "Default")
      (node (ref "C17") (pin "1") (pinfunction "1_1") (pintype "passive"))
      (node (ref "U8") (pin "11") (pinfunction "CP1_11") (pintype "bidirectional"))
    )
    (net (code "156") (name "Net-(U8-CP2)") (class "Default")
      (node (ref "C17") (pin "2") (pinfunction "2_2") (pintype "passive"))
      (node (ref "U8") (pin "12") (pinfunction "CP2_12") (pintype "bidirectional"))
    )
    (net (code "157") (name "Net-(U8-OUT+)") (class "Default")
      (node (ref "J2") (pin "5") (pinfunction "5_5") (pintype "passive"))
      (node (ref "U8") (pin "7") (pinfunction "OUT+_7") (pintype "bidirectional"))
    )
    (net (code "158") (name "Net-(U8-OUT-)") (class "Default")
      (node (ref "J2") (pin "6") (pinfunction "6_6") (pintype "passive"))
      (node (ref "U8") (pin "10") (pinfunction "OUT-_10") (pintype "bidirectional"))
    )
    (net (code "159") (name "Net-(U8-SENSE)") (class "Default")
      (node (ref "R16") (pin "2") (pinfunction "2_2") (pintype "passive"))
      (node (ref "U8") (pin "8") (pinfunction "SENSE_8") (pintype "bidirectional"))
    )
    (net (code "160") (name "Net-(U8-VCP)") (class "Default")
      (node (ref "C18") (pin "2") (pinfunction "2_2") (pintype "passive"))
      (node (ref "U8") (pin "14") (pinfunction "VCP_14") (pintype "bidirectional"))
    )
    (net (code "161") (name "Net-(U8-VPROPI)") (class "Default")
      (node (ref "R14") (pin "2") (pinfunction "2_2") (pintype "passive"))
      (node (ref "U8") (pin "15") (pinfunction "VPROPI_15") (pintype "bidirectional"))
    )
    (net (code "162") (name "Net-(U8-~{SLEEP})") (class "Default")
      (node (ref "R98") (pin "1") (pinfunction "1_1") (pintype "passive"))
      (node (ref "U8") (pin "5") (pinfunction "~{SLEEP}_5") (pintype "bidirectional"))
    )
    (net (code "163") (name "Net-(U9-CP1)") (class "Default")
      (node (ref "C23") (pin "1") (pinfunction "1_1") (pintype "passive"))
      (node (ref "U9") (pin "11") (pinfunction "CP1_11") (pintype "bidirectional"))
    )
    (net (code "164") (name "Net-(U9-CP2)") (class "Default")
      (node (ref "C23") (pin "2") (pinfunction "2_2") (pintype "passive"))
      (node (ref "U9") (pin "12") (pinfunction "CP2_12") (pintype "bidirectional"))
    )
    (net (code "165") (name "Net-(U9-OUT+)") (class "Default")
      (node (ref "J3") (pin "1") (pinfunction "1_1") (pintype "passive"))
      (node (ref "U9") (pin "7") (pinfunction "OUT+_7") (pintype "bidirectional"))
    )
    (net (code "166") (name "Net-(U9-OUT-)") (class "Default")
      (node (ref "J3") (pin "2") (pinfunction "2_2") (pintype "passive"))
      (node (ref "U9") (pin "10") (pinfunction "OUT-_10") (pintype "bidirectional"))
    )
    (net (code "167") (name "Net-(U9-SENSE)") (class "Default")
      (node (ref "R19") (pin "2") (pinfunction "2_2") (pintype "passive"))
      (node (ref "U9") (pin "8") (pinfunction "SENSE_8") (pintype "bidirectional"))
    )
    (net (code "168") (name "Net-(U9-VCP)") (class "Default")
      (node (ref "C24") (pin "2") (pinfunction "2_2") (pintype "passive"))
      (node (ref "U9") (pin "14") (pinfunction "VCP_14") (pintype "bidirectional"))
    )
    (net (code "169") (name "Net-(U9-VPROPI)") (class "Default")
      (node (ref "R21") (pin "2") (pinfunction "2_2") (pintype "passive"))
      (node (ref "U9") (pin "15") (pinfunction "VPROPI_15") (pintype "bidirectional"))
    )
    (net (code "170") (name "Net-(U9-~{SLEEP})") (class "Default")
      (node (ref "R100") (pin "1") (pinfunction "1_1") (pintype "passive"))
      (node (ref "U9") (pin "5") (pinfunction "~{SLEEP}_5") (pintype "bidirectional"))
    )
    (net (code "171") (name "Net-(U10A-BST_A)") (class "Default")
      (node (ref "C29") (pin "1") (pinfunction "1_1") (pintype "passive"))
      (node (ref "U10") (pin "48") (pinfunction "BST_A_48") (pintype "bidirectional"))
    )
    (net (code "172") (name "Net-(U10A-GH_A)") (class "Default")
      (node (ref "R23") (pin "1") (pinfunction "1_1") (pintype "passive"))
      (node (ref "U10") (pin "47") (pinfunction "GH_A_47") (pintype "bidirectional"))
    )
    (net (code "173") (name "Net-(U10A-GL_A)") (class "Default")
      (node (ref "R24") (pin "1") (pinfunction "1_1") (pintype "passive"))
      (node (ref "U10") (pin "45") (pinfunction "GL_A_45") (pintype "bidirectional"))
    )
    (net (code "174") (name "Net-(U10B-BST_B)") (class "Default")
      (node (ref "C30") (pin "1") (pinfunction "1_1") (pintype "passive"))
      (node (ref "U10") (pin "43") (pinfunction "BST_B_43") (pintype "bidirectional"))
    )
    (net (code "175") (name "Net-(U10B-GH_B)") (class "Default")
      (node (ref "R25") (pin "1") (pinfunction "1_1") (pintype "passive"))
      (node (ref "U10") (pin "42") (pinfunction "GH_B_42") (pintype "bidirectional"))
    )
    (net (code "176") (name "Net-(U10B-GL_B)") (class "Default")
      (node (ref "R26") (pin "1") (pinfunction "1_1") (pintype "passive"))
      (node (ref "U10") (pin "40") (pinfunction "GL_B_40") (pintype "bidirectional"))
    )
    (net (code "177") (name "Net-(U10C-BST_C)") (class "Default")
      (node (ref "C31") (pin "1") (pinfunction "1_1") (pintype "passive"))
      (node (ref "U10") (pin "38") (pinfunction "BST_C_38") (pintype "bidirectional"))
    )
    (net (code "178") (name "Net-(U10C-GH_C)") (class "Default")
      (node (ref "R28") (pin "1") (pinfunction "1_1") (pintype "passive"))
      (node (ref "U10") (pin "37") (pinfunction "GH_C_37") (pintype "bidirectional"))
    )
    (net (code "179") (name "Net-(U10C-GL_C)") (class "Default")
      (node (ref "R29") (pin "1") (pinfunction "1_1") (pintype "passive"))
      (node (ref "U10") (pin "35") (pinfunction "GL_C_35") (pintype "bidirectional"))
    )
    (net (code "180") (name "Net-(U10D-AVDD)") (class "Default")
      (node (ref "C37") (pin "1") (pinfunction "1_1") (pintype "passive"))
      (node (ref "U10") (pin "27") (pinfunction "AVDD_27") (pintype "bidirectional"))
    )
    (net (code "181") (name "Net-(U10D-CP1)") (class "Default")
      (node (ref "C36") (pin "1") (pinfunction "1_1") (pintype "passive"))
      (node (ref "U10") (pin "14") (pinfunction "CP1_14") (pintype "bidirectional"))
    )
    (net (code "182") (name "Net-(U10D-CP2)") (class "Default")
      (node (ref "C36") (pin "2") (pinfunction "2_2") (pintype "passive"))
      (node (ref "U10") (pin "15") (pinfunction "CP2_15") (pintype "bidirectional"))
    )
    (net (code "183") (name "Net-(U10D-DTC)") (class "Default")
      (node (ref "R31") (pin "2") (pinfunction "2_2") (pintype "passive"))
      (node (ref "U10") (pin "7") (pinfunction "DTC_7") (pintype "bidirectional"))
    )
    (net (code "184") (name "Net-(U10D-DVDD)") (class "Default")
      (node (ref "C38") (pin "1") (pinfunction "1_1") (pintype "passive"))
      (node (ref "U10") (pin "23") (pinfunction "DVDD_23") (pintype "bidirectional"))
    )
    (net (code "185") (name "Net-(U10D-GVDD)") (class "Default")
      (node (ref "C45") (pin "1") (pinfunction "1_1") (pintype "passive"))
      (node (ref "U10") (pin "13") (pinfunction "GVDD_13") (pintype "bidirectional"))
    )
    (net (code "186") (name "Net-(U10D-SO1)") (class "Default")
      (node (ref "R75") (pin "1") (pinfunction "1_1") (pintype "passive"))
      (node (ref "U10") (pin "25") (pinfunction "SO1_25") (pintype "bidirectional"))
    )
    (net (code "187") (name "Net-(U10D-SO2)") (class "Default")
      (node (ref "R76") (pin "1") (pinfunction "1_1") (pintype "passive"))
      (node (ref "U10") (pin "26") (pinfunction "SO2_26") (pintype "bidirectional"))
    )
    (net (code "188") (name "Net-(U10E-BST_BK)") (class "Default")
      (node (ref "C43") (pin "2") (pinfunction "2_2") (pintype "passive"))
      (node (ref "U10") (pin "52") (pinfunction "BST_BK_52") (pintype "bidirectional"))
    )
    (net (code "189") (name "Net-(U10E-COMP)") (class "Default")
      (node (ref "C51") (pin "1") (pinfunction "1_1") (pintype "passive"))
      (node (ref "R34") (pin "2") (pinfunction "2_2") (pintype "passive"))
      (node (ref "U10") (pin "2") (pinfunction "COMP_2") (pintype "bidirectional"))
    )
    (net (code "190") (name "Net-(U10E-PWRGD)") (class "Default")
      (node (ref "R33") (pin "1") (pinfunction "1_1") (pintype "passive"))
      (node (ref "U10") (pin "4") (pinfunction "PWRGD_4") (pintype "bidirectional"))
    )
    (net (code "191") (name "Net-(U10E-RT_CLK)") (class "Default")
      (node (ref "R32") (pin "2") (pinfunction "2_2") (pintype "passive"))
      (node (ref "U10") (pin "1") (pinfunction "RT_CLK_1") (pintype "bidirectional"))
    )
    (net (code "192") (name "Net-(U10E-SS_TR)") (class "Default")
      (node (ref "C46") (pin "1") (pinfunction "1_1") (pintype "passive"))
      (node (ref "U10") (pin "56") (pinfunction "SS_TR_56") (pintype "bidirectional"))
    )
    (net (code "193") (name "Net-(U10E-VSENSE)") (class "Default")
      (node (ref "R35") (pin "1") (pinfunction "1_1") (pintype "passive"))
      (node (ref "R36") (pin "2") (pinfunction "2_2") (pintype "passive"))
      (node (ref "U10") (pin "3") (pinfunction "VSENSE_3") (pintype "bidirectional"))
    )
    (net (code "194") (name "Net-(U11A-+IN)") (class "Default")
      (node (ref "C57") (pin "1") (pinfunction "1_1") (pintype "passive"))
      (node (ref "R61") (pin "2") (pinfunction "2_2") (pintype "passive"))
      (node (ref "R63") (pin "2") (pinfunction "2_2") (pintype "passive"))
      (node (ref "U11") (pin "3") (pinfunction "+IN_3") (pintype "input"))
    )
    (net (code "195") (name "Net-(U11A--IN)") (class "Default")
      (node (ref "R62") (pin "2") (pinfunction "2_2") (pintype "passive"))
      (node (ref "R64") (pin "1") (pinfunction "1_1") (pintype "passive"))
      (node (ref "U11") (pin "2") (pinfunction "-IN_2") (pintype "input"))
    )
    (net (code "196") (name "Net-(U11A-OUT)") (class "Default")
      (node (ref "R64") (pin "2") (pinfunction "2_2") (pintype "passive"))
      (node (ref "R77") (pin "1") (pinfunction "1_1") (pintype "passive"))
      (node (ref "U11") (pin "1") (pinfunction "OUT_1") (pintype "output"))
    )
    (net (code "197") (name "Net-(U11B-+IN)") (class "Default")
      (node (ref "R65") (pin "1") (pinfunction "1_1") (pintype "passive"))
      (node (ref "R66") (pin "2") (pinfunction "2_2") (pintype "passive"))
      (node (ref "U11") (pin "5") (pinfunction "+IN_5") (pintype "input"))
    )
    (net (code "198") (name "Net-(U11B--IN)") (class "Default")
      (node (ref "R61") (pin "1") (pinfunction "1_1") (pintype "passive"))
      (node (ref "U11") (pin "6") (pinfunction "-IN_6") (pintype "input"))
      (node (ref "U11") (pin "7") (pinfunction "OUT_7") (pintype "output"))
    )
    (net (code "199") (name "Net-(U12--IN)") (class "Default")
      (node (ref "R81") (pin "2") (pinfunction "2_2") (pintype "passive"))
      (node (ref "U12") (pin "4") (pinfunction "-IN_4") (pintype "input"))
    )
    (net (code "200") (name "Net-(U12-OUT)") (class "Default")
      (node (ref "R80") (pin "2") (pinfunction "2_2") (pintype "passive"))
      (node (ref "U12") (pin "1") (pinfunction "OUT_1") (pintype "output"))
    )
    (net (code "201") (name "Net-(U13-CAP)") (class "Default")
      (node (ref "C88") (pin "2") (pinfunction "2_2") (pintype "passive"))
      (node (ref "U13") (pin "9") (pinfunction "CAP_9") (pintype "bidirectional"))
    )
    (net (code "202") (name "Net-(U13-COM3)") (class "Default")
      (node (ref "R85") (pin "2") (pinfunction "2_2") (pintype "passive"))
      (node (ref "U13") (pin "17") (pinfunction "COM3_17") (pintype "bidirectional"))
    )
    (net (code "203") (name "Net-(U13-PS0)") (class "Default")
      (node (ref "R83") (pin "2") (pinfunction "2_2") (pintype "passive"))
      (node (ref "U13") (pin "6") (pinfunction "PS0_6") (pintype "bidirectional"))
    )
    (net (code "204") (name "Net-(U13-PS1)") (class "Default")
      (node (ref "R84") (pin "2") (pinfunction "2_2") (pintype "passive"))
      (node (ref "U13") (pin "5") (pinfunction "PS1_5") (pintype "bidirectional"))
    )
    (net (code "205") (name "Net-(U13-XIN32)") (class "Default")
      (node (ref "C92") (pin "1") (pinfunction "1_1") (pintype "passive"))
      (node (ref "U13") (pin "27") (pinfunction "XIN32_27") (pintype "bidirectional"))
      (node (ref "Y1") (pin "4") (pinfunction "3_4") (pintype "passive"))
    )
    (net (code "206") (name "Net-(U13-XOUT32)") (class "Default")
      (node (ref "C91") (pin "1") (pinfunction "1_1") (pintype "passive"))
      (node (ref "U13") (pin "26") (pinfunction "XOUT32_26") (pintype "bidirectional"))
      (node (ref "Y1") (pin "1") (pinfunction "1_1") (pintype "passive"))
    )
    (net (code "207") (name "Net-(U13-~{BOOT_LOAD_PIN})") (class "Default")
      (node (ref "R86") (pin "1") (pinfunction "1_1") (pintype "passive"))
      (node (ref "U13") (pin "4") (pinfunction "~{BOOT_LOAD_PIN}_4") (pintype "bidirectional"))
    )
    (net (code "208") (name "PHASE1") (class "Default")
      (node (ref "R124") (pin "2") (pinfunction "2_2") (pintype "passive"))
      (node (ref "U6") (pin "3") (pinfunction "PHASE_3") (pintype "bidirectional"))
    )
    (net (code "209") (name "PHASE2") (class "Default")
      (node (ref "R125") (pin "2") (pinfunction "2_2") (pintype "passive"))
      (node (ref "U7") (pin "3") (pinfunction "PHASE_3") (pintype "bidirectional"))
    )
    (net (code "210") (name "PHASE3") (class "Default")
      (node (ref "R126") (pin "2") (pinfunction "2_2") (pintype "passive"))
      (node (ref "U8") (pin "3") (pinfunction "PHASE_3") (pintype "bidirectional"))
    )
    (net (code "211") (name "PICCOLO_TDO") (class "Default")
      (node (ref "J7") (pin "6") (pinfunction "TDO_6") (pintype "bidirectional"))
      (node (ref "R119") (pin "1") (pinfunction "1_1") (pintype "passive"))
      (node (ref "R120") (pin "2") (pinfunction "2_2") (pintype "passive"))
      (node (ref "U5") (pin "70") (pinfunction "TDO/GPIO37_70") (pintype "bidirectional"))
    )
    (net (code "212") (name "PWM_AH") (class "Default")
      (node (ref "R50") (pin "1") (pinfunction "1_1") (pintype "passive"))
      (node (ref "U10") (pin "17") (pinfunction "INH_A_17") (pintype "bidirectional"))
    )
    (net (code "213") (name "PWM_AL") (class "Default")
      (node (ref "R51") (pin "1") (pinfunction "1_1") (pintype "passive"))
      (node (ref "U10") (pin "18") (pinfunction "INL_A_18") (pintype "bidirectional"))
    )
    (net (code "214") (name "PWM_BH") (class "Default")
      (node (ref "R52") (pin "1") (pinfunction "1_1") (pintype "passive"))
      (node (ref "U10") (pin "19") (pinfunction "INH_B_19") (pintype "bidirectional"))
    )
    (net (code "215") (name "PWM_BL") (class "Default")
      (node (ref "R53") (pin "1") (pinfunction "1_1") (pintype "passive"))
      (node (ref "U10") (pin "20") (pinfunction "INL_B_20") (pintype "bidirectional"))
    )
    (net (code "216") (name "PWM_CH") (class "Default")
      (node (ref "R54") (pin "1") (pinfunction "1_1") (pintype "passive"))
      (node (ref "U10") (pin "21") (pinfunction "INH_C_21") (pintype "bidirectional"))
    )
    (net (code "217") (name "PWM_CL") (class "Default")
      (node (ref "R55") (pin "1") (pinfunction "1_1") (pintype "passive"))
      (node (ref "U10") (pin "22") (pinfunction "INL_C_22") (pintype "bidirectional"))
    )
    (net (code "218") (name "SH_A") (class "Default")
      (node (ref "C29") (pin "2") (pinfunction "2_2") (pintype "passive"))
      (node (ref "J8") (pin "1") (pinfunction "1_1") (pintype "passive"))
      (node (ref "Q1") (pin "S1") (pinfunction "S_S1") (pintype "passive"))
      (node (ref "Q1") (pin "S2") (pinfunction "S_S2") (pintype "passive"))
      (node (ref "Q1") (pin "S3") (pinfunction "S_S3") (pintype "passive"))
      (node (ref "Q2") (pin "D") (pinfunction "D_D") (pintype "passive"))
      (node (ref "R67") (pin "1") (pinfunction "1_1") (pintype "passive"))
      (node (ref "U10") (pin "46") (pinfunction "SH_A_46") (pintype "bidirectional"))
    )
    (net (code "219") (name "SH_B") (class "Default")
      (node (ref "C30") (pin "2") (pinfunction "2_2") (pintype "passive"))
      (node (ref "J8") (pin "2") (pinfunction "2_2") (pintype "passive"))
      (node (ref "Q3") (pin "S1") (pinfunction "S_S1") (pintype "passive"))
      (node (ref "Q3") (pin "S2") (pinfunction "S_S2") (pintype "passive"))
      (node (ref "Q3") (pin "S3") (pinfunction "S_S3") (pintype "passive"))
      (node (ref "Q4") (pin "D") (pinfunction "D_D") (pintype "passive"))
      (node (ref "R69") (pin "1") (pinfunction "1_1") (pintype "passive"))
      (node (ref "U10") (pin "41") (pinfunction "SH_B_41") (pintype "bidirectional"))
    )
    (net (code "220") (name "SH_C") (class "Default")
      (node (ref "C31") (pin "2") (pinfunction "2_2") (pintype "passive"))
      (node (ref "J8") (pin "3") (pinfunction "3_3") (pintype "passive"))
      (node (ref "Q5") (pin "S1") (pinfunction "S_S1") (pintype "passive"))
      (node (ref "Q5") (pin "S2") (pinfunction "S_S2") (pintype "passive"))
      (node (ref "Q5") (pin "S3") (pinfunction "S_S3") (pintype "passive"))
      (node (ref "Q6") (pin "D") (pinfunction "D_D") (pintype "passive"))
      (node (ref "R71") (pin "1") (pinfunction "1_1") (pintype "passive"))
      (node (ref "U10") (pin "36") (pinfunction "SH_C_36") (pintype "bidirectional"))
    )
    (net (code "221") (name "SPI_MISO") (class "Default")
      (node (ref "R116") (pin "2") (pinfunction "2_2") (pintype "passive"))
      (node (ref "U1") (pin "14") (pinfunction "SPI_MISO_14") (pintype "bidirectional"))
    )
    (net (code "222") (name "SPI_MOSI") (class "Default")
      (node (ref "R115") (pin "2") (pinfunction "2_2") (pintype "passive"))
      (node (ref "U1") (pin "15") (pinfunction "SPI_MOSI_15") (pintype "bidirectional"))
    )
    (net (code "223") (name "SPI_SCK") (class "Default")
      (node (ref "R118") (pin "2") (pinfunction "2_2") (pintype "passive"))
      (node (ref "U1") (pin "16") (pinfunction "SPI_SCK_16") (pintype "bidirectional"))
    )
    (net (code "224") (name "VA_FB") (class "Default")
      (node (ref "C59") (pin "1") (pinfunction "1_1") (pintype "passive"))
      (node (ref "R44") (pin "2") (pinfunction "2_2") (pintype "passive"))
      (node (ref "R67") (pin "2") (pinfunction "2_2") (pintype "passive"))
      (node (ref "R68") (pin "2") (pinfunction "2_2") (pintype "passive"))
    )
    (net (code "225") (name "VBAT") (class "Default")
      (node (ref "C1") (pin "1") (pinfunction "1_1") (pintype "passive"))
      (node (ref "C55") (pin "1") (pinfunction "1_1") (pintype "passive"))
      (node (ref "C9") (pin "1") (pinfunction "1_1") (pintype "passive"))
      (node (ref "J4") (pin "1") (pinfunction "1_1") (pintype "passive"))
      (node (ref "Q11") (pin "1") (pinfunction "G_1") (pintype "passive"))
      (node (ref "R89") (pin "2") (pinfunction "2_2") (pintype "passive"))
      (node (ref "U3") (pin "1") (pinfunction "IN_1") (pintype "bidirectional"))
      (node (ref "U4") (pin "3") (pinfunction "VBAT_3") (pintype "bidirectional"))
    )
    (net (code "226") (name "VB_FB") (class "Default")
      (node (ref "C60") (pin "1") (pinfunction "1_1") (pintype "passive"))
      (node (ref "R45") (pin "2") (pinfunction "2_2") (pintype "passive"))
      (node (ref "R69") (pin "2") (pinfunction "2_2") (pintype "passive"))
      (node (ref "R70") (pin "2") (pinfunction "2_2") (pintype "passive"))
    )
    (net (code "227") (name "VC_FB") (class "Default")
      (node (ref "C61") (pin "1") (pinfunction "1_1") (pintype "passive"))
      (node (ref "R46") (pin "2") (pinfunction "2_2") (pintype "passive"))
      (node (ref "R71") (pin "2") (pinfunction "2_2") (pintype "passive"))
      (node (ref "R72") (pin "2") (pinfunction "2_2") (pintype "passive"))
    )
    (net (code "228") (name "VPROPI1") (class "Default")
      (node (ref "C20") (pin "1") (pinfunction "1_1") (pintype "passive"))
      (node (ref "R10") (pin "1") (pinfunction "1_1") (pintype "passive"))
      (node (ref "R95") (pin "2") (pinfunction "2_2") (pintype "passive"))
    )
    (net (code "229") (name "VPROPI2") (class "Default")
      (node (ref "C21") (pin "1") (pinfunction "1_1") (pintype "passive"))
      (node (ref "R11") (pin "1") (pinfunction "1_1") (pintype "passive"))
      (node (ref "R94") (pin "2") (pinfunction "2_2") (pintype "passive"))
    )
    (net (code "230") (name "VPROPI3") (class "Default")
      (node (ref "C22") (pin "1") (pinfunction "1_1") (pintype "passive"))
      (node (ref "R14") (pin "1") (pinfunction "1_1") (pintype "passive"))
      (node (ref "R93") (pin "2") (pinfunction "2_2") (pintype "passive"))
    )
    (net (code "231") (name "unconnected-(J1-ID-Pad4)") (class "Default")
      (node (ref "J1") (pin "4") (pinfunction "ID_4") (pintype "bidirectional"))
    )
    (net (code "232") (name "unconnected-(S2A-3-PadB1)") (class "Default")
      (node (ref "S2") (pin "B1") (pinfunction "3_B1") (pintype "bidirectional"))
    )
    (net (code "233") (name "unconnected-(S2B-3-PadB2)") (class "Default")
      (node (ref "S2") (pin "B2") (pinfunction "3_B2") (pintype "bidirectional"))
    )
    (net (code "234") (name "unconnected-(U1-ADC6-Pad28)") (class "Default")
      (node (ref "U1") (pin "28") (pinfunction "ADC6_28") (pintype "bidirectional"))
    )
    (net (code "235") (name "unconnected-(U1-ADC7-Pad29)") (class "Default")
      (node (ref "U1") (pin "29") (pinfunction "ADC7_29") (pintype "bidirectional"))
    )
    (net (code "236") (name "unconnected-(U1-BATTERY-Pad31)") (class "Default")
      (node (ref "U1") (pin "31") (pinfunction "BATTERY_31") (pintype "bidirectional"))
    )
    (net (code "237") (name "unconnected-(U1-DGND_USB-Pad10)") (class "Default")
      (node (ref "U1") (pin "10") (pinfunction "DGND_USB_10") (pintype "bidirectional"))
    )
    (net (code "238") (name "unconnected-(U1-DVDD_USB-Pad13)") (class "Default")
      (node (ref "U1") (pin "13") (pinfunction "DVDD_USB_13") (pintype "bidirectional"))
    )
    (net (code "239") (name "unconnected-(U1-UNUSED-Pad2)") (class "Default")
      (node (ref "U1") (pin "2") (pinfunction "UNUSED_2") (pintype "bidirectional"))
    )
    (net (code "240") (name "unconnected-(U1-USB_N-Pad12)") (class "Default")
      (node (ref "U1") (pin "12") (pinfunction "USB_N_12") (pintype "bidirectional"))
    )
    (net (code "241") (name "unconnected-(U1-USB_P-Pad11)") (class "Default")
      (node (ref "U1") (pin "11") (pinfunction "USB_P_11") (pintype "bidirectional"))
    )
    (net (code "242") (name "unconnected-(U2-3V3OUT-Pad16)") (class "Default")
      (node (ref "U2") (pin "16") (pinfunction "3V3OUT_16") (pintype "bidirectional"))
    )
    (net (code "243") (name "unconnected-(U2-CBUS2-Pad10)") (class "Default")
      (node (ref "U2") (pin "10") (pinfunction "CBUS2_10") (pintype "bidirectional"))
    )
    (net (code "244") (name "unconnected-(U2-CBUS3-Pad11)") (class "Default")
      (node (ref "U2") (pin "11") (pinfunction "CBUS3_11") (pintype "bidirectional"))
    )
    (net (code "245") (name "unconnected-(U2-CBUS4-Pad9)") (class "Default")
      (node (ref "U2") (pin "9") (pinfunction "CBUS4_9") (pintype "bidirectional"))
    )
    (net (code "246") (name "unconnected-(U2-OSCI-Pad27)") (class "Default")
      (node (ref "U2") (pin "27") (pinfunction "OSCI_27") (pintype "bidirectional"))
    )
    (net (code "247") (name "unconnected-(U2-OSCO-Pad28)") (class "Default")
      (node (ref "U2") (pin "28") (pinfunction "OSCO_28") (pintype "bidirectional"))
    )
    (net (code "248") (name "unconnected-(U2-~{CTS}-Pad8)") (class "Default")
      (node (ref "U2") (pin "8") (pinfunction "~{CTS}_8") (pintype "bidirectional"))
    )
    (net (code "249") (name "unconnected-(U2-~{DCD}-Pad7)") (class "Default")
      (node (ref "U2") (pin "7") (pinfunction "~{DCD}_7") (pintype "bidirectional"))
    )
    (net (code "250") (name "unconnected-(U2-~{DSR}-Pad6)") (class "Default")
      (node (ref "U2") (pin "6") (pinfunction "~{DSR}_6") (pintype "bidirectional"))
    )
    (net (code "251") (name "unconnected-(U2-~{RESET}-Pad18)") (class "Default")
      (node (ref "U2") (pin "18") (pinfunction "~{RESET}_18") (pintype "bidirectional"))
    )
    (net (code "252") (name "unconnected-(U2-~{RI}-Pad3)") (class "Default")
      (node (ref "U2") (pin "3") (pinfunction "~{RI}_3") (pintype "bidirectional"))
    )
    (net (code "253") (name "unconnected-(U5A-ADC_INA0-Pad23)") (class "Default")
      (node (ref "U5") (pin "23") (pinfunction "ADC_INA0_23") (pintype "bidirectional"))
    )
    (net (code "254") (name "unconnected-(U5A-ADC_INA1-Pad22)") (class "Default")
      (node (ref "U5") (pin "22") (pinfunction "ADC_INA1_22") (pintype "bidirectional"))
    )
    (net (code "255") (name "unconnected-(U5A-ADC_INA2{slash}COMP1A{slash}AIO2-Pad21)") (class "Default")
      (node (ref "U5") (pin "21") (pinfunction "ADC_INA2/COMP1A/AIO2_21") (pintype "bidirectional"))
    )
    (net (code "256") (name "unconnected-(U5A-ADC_INA7-Pad16)") (class "Default")
      (node (ref "U5") (pin "16") (pinfunction "ADC_INA7_16") (pintype "bidirectional"))
    )
    (net (code "257") (name "unconnected-(U5A-ADC_INB6{slash}COMP3B{slash}AIO14-Pad34)") (class "Default")
      (node (ref "U5") (pin "34") (pinfunction "ADC_INB6/COMP3B/AIO14_34") (pintype "bidirectional"))
    )
    (net (code "258") (name "unconnected-(U5A-TEST2-Pad45)") (class "Default")
      (node (ref "U5") (pin "45") (pinfunction "TEST2_45") (pintype "bidirectional"))
    )
    (net (code "259") (name "unconnected-(U5A-VREFHI-Pad24)") (class "Default")
      (node (ref "U5") (pin "24") (pinfunction "VREFHI_24") (pintype "bidirectional"))
    )
    (net (code "260") (name "unconnected-(U5A-X1-Pad60)") (class "Default")
      (node (ref "U5") (pin "60") (pinfunction "X1_60") (pintype "bidirectional"))
    )
    (net (code "261") (name "unconnected-(U5A-X2-Pad59)") (class "Default")
      (node (ref "U5") (pin "59") (pinfunction "X2_59") (pintype "bidirectional"))
    )
    (net (code "262") (name "unconnected-(U5A-XCLK_I{slash}GPIO19{slash}~{SPISTEA}{slash}SCI_RXDB{slash}ECAP1-Pad64)") (class "Default")
      (node (ref "U5") (pin "64") (pinfunction "XCLK_I/GPIO19/~{SPISTEA}/SCI_RXDB/ECAP1_64") (pintype "bidirectional"))
    )
    (net (code "263") (name "unconnected-(U5A-XCLK_O{slash}GPIO18{slash}SPICLK_A{slash}SCI_TXDB-Pad51)") (class "Default")
      (node (ref "U5") (pin "51") (pinfunction "XCLK_O/GPIO18/SPICLK_A/SCI_TXDB_51") (pintype "bidirectional"))
    )
    (net (code "264") (name "unconnected-(U5B-GPIO4{slash}EPWM3A-Pad9)") (class "Default")
      (node (ref "U5") (pin "9") (pinfunction "GPIO4/EPWM3A_9") (pintype "bidirectional"))
    )
    (net (code "265") (name "unconnected-(U5B-GPIO5{slash}EPWM3B{slash}SPISIMOA{slash}ECAP1-Pad10)") (class "Default")
      (node (ref "U5") (pin "10") (pinfunction "GPIO5/EPWM3B/SPISIMOA/ECAP1_10") (pintype "bidirectional"))
    )
    (net (code "266") (name "unconnected-(U5B-GPIO12{slash}~{TZ1}{slash}SCITXDA{slash}SPISIMOB-Pad44)") (class "Default")
      (node (ref "U5") (pin "44") (pinfunction "GPIO12/~{TZ1}/SCITXDA/SPISIMOB_44") (pintype "bidirectional"))
    )
    (net (code "267") (name "unconnected-(U5B-GPIO13{slash}~{TZ2}{slash}SPISOMIB-Pad95)") (class "Default")
      (node (ref "U5") (pin "95") (pinfunction "GPIO13/~{TZ2}/SPISOMIB_95") (pintype "bidirectional"))
    )
    (net (code "268") (name "unconnected-(U5B-GPIO15{slash}ECAP2{slash}SCI_RXDB{slash}~{SPISTEB}-Pad88)") (class "Default")
      (node (ref "U5") (pin "88") (pinfunction "GPIO15/ECAP2/SCI_RXDB/~{SPISTEB}_88") (pintype "bidirectional"))
    )
    (net (code "269") (name "unconnected-(U5B-GPIO16{slash}SPI_SIMO_A{slash}~{TZ2}-Pad55)") (class "Default")
      (node (ref "U5") (pin "55") (pinfunction "GPIO16/SPI_SIMO_A/~{TZ2}_55") (pintype "bidirectional"))
    )
    (net (code "270") (name "unconnected-(U5B-GPIO17{slash}SPI_SOMI_A{slash}~{TZ3}-Pad52)") (class "Default")
      (node (ref "U5") (pin "52") (pinfunction "GPIO17/SPI_SOMI_A/~{TZ3}_52") (pintype "bidirectional"))
    )
    (net (code "271") (name "unconnected-(U5B-GPIO22{slash}EQEP1S{slash}MCLKXA{slash}SCITXDB-Pad98)") (class "Default")
      (node (ref "U5") (pin "98") (pinfunction "GPIO22/EQEP1S/MCLKXA/SCITXDB_98") (pintype "bidirectional"))
    )
    (net (code "272") (name "unconnected-(U5B-GPIO26{slash}ECAP3{slash}EQEP2I{slash}SPICLKB{slash}USB0DP-Pad78)") (class "Default")
      (node (ref "U5") (pin "78") (pinfunction "GPIO26/ECAP3/EQEP2I/SPICLKB/USB0DP_78") (pintype "bidirectional"))
    )
    (net (code "273") (name "unconnected-(U5B-GPIO30{slash}CAN_RXA{slash}EQEP2I{slash}EPWM7A-Pad41)") (class "Default")
      (node (ref "U5") (pin "41") (pinfunction "GPIO30/CAN_RXA/EQEP2I/EPWM7A_41") (pintype "bidirectional"))
    )
    (net (code "274") (name "unconnected-(U5B-GPIO32{slash}SDA_A{slash}EPWMSYNCI{slash}~{ADCSOCAO}-Pad99)") (class "Default")
      (node (ref "U5") (pin "99") (pinfunction "GPIO32/SDA_A/EPWMSYNCI/~{ADCSOCAO}_99") (pintype "bidirectional"))
    )
    (net (code "275") (name "unconnected-(U5B-GPIO33{slash}SCL_A{slash}EPWMSYNCO{slash}~{ADCSOCBO}-Pad100)") (class "Default")
      (node (ref "U5") (pin "100") (pinfunction "GPIO33/SCL_A/EPWMSYNCO/~{ADCSOCBO}_100") (pintype "bidirectional"))
    )
    (net (code "276") (name "unconnected-(U5B-GPIO39-Pad66)") (class "Default")
      (node (ref "U5") (pin "66") (pinfunction "GPIO39_66") (pintype "bidirectional"))
    )
    (net (code "277") (name "unconnected-(U5B-GPIO40{slash}EPWM7A{slash}SCI_TXDB-Pad82)") (class "Default")
      (node (ref "U5") (pin "82") (pinfunction "GPIO40/EPWM7A/SCI_TXDB_82") (pintype "bidirectional"))
    )
    (net (code "278") (name "unconnected-(U5B-GPIO41{slash}EPWM7B{slash}SCI_RXDB-Pad76)") (class "Default")
      (node (ref "U5") (pin "76") (pinfunction "GPIO41/EPWM7B/SCI_RXDB_76") (pintype "bidirectional"))
    )
    (net (code "279") (name "unconnected-(U5B-GPIO42{slash}EPWM8A{slash}~{TZ1}{slash}COMP1OUT-Pad1)") (class "Default")
      (node (ref "U5") (pin "1") (pinfunction "GPIO42/EPWM8A/~{TZ1}/COMP1OUT_1") (pintype "bidirectional"))
    )
    (net (code "280") (name "unconnected-(U5B-GPIO43{slash}EPWM8B{slash}~{TZ2}{slash}COMP2OUT-Pad8)") (class "Default")
      (node (ref "U5") (pin "8") (pinfunction "GPIO43/EPWM8B/~{TZ2}/COMP2OUT_8") (pintype "bidirectional"))
    )
    (net (code "281") (name "unconnected-(U5B-GPIO44{slash}MFSRA{slash}SCIRXDB{slash}EPWM7B-Pad56)") (class "Default")
      (node (ref "U5") (pin "56") (pinfunction "GPIO44/MFSRA/SCIRXDB/EPWM7B_56") (pintype "bidirectional"))
    )
    (net (code "282") (name "unconnected-(U5B-GPIO58{slash}MCLKRA{slash}SCI_TXDB{slash}EPWM7A-Pad94)") (class "Default")
      (node (ref "U5") (pin "94") (pinfunction "GPIO58/MCLKRA/SCI_TXDB/EPWM7A_94") (pintype "bidirectional"))
    )
    (net (code "283") (name "unconnected-(U10E-EN_BUCK-Pad55)") (class "Default")
      (node (ref "U10") (pin "55") (pinfunction "EN_BUCK_55") (pintype "bidirectional"))
    )
    (net (code "284") (name "unconnected-(U13-INT-Pad14)") (class "Default")
      (node (ref "U13") (pin "14") (pinfunction "INT_14") (pintype "bidirectional"))
    )
    (net (code "285") (name "~{ATUM_RESET}") (class "Default")
      (node (ref "J6") (pin "10") (pinfunction "RESET_10") (pintype "bidirectional"))
      (node (ref "S2") (pin "A1") (pinfunction "1_A1") (pintype "bidirectional"))
      (node (ref "U1") (pin "30") (pinfunction "~{RESET}_30") (pintype "bidirectional"))
    )
    (net (code "286") (name "~{AUX_FAULT}") (class "Default")
      (node (ref "R20") (pin "1") (pinfunction "1_1") (pintype "passive"))
      (node (ref "U9") (pin "1") (pinfunction "~{FAULT}_1") (pintype "bidirectional"))
    )
    (net (code "287") (name "~{DRV_CS}") (class "Default")
      (node (ref "R56") (pin "2") (pinfunction "2_2") (pintype "passive"))
      (node (ref "U10") (pin "8") (pinfunction "~{SCS}_8") (pintype "bidirectional"))
    )
    (net (code "288") (name "~{DTR_FTDI}") (class "Default")
      (node (ref "S2") (pin "COM2") (pinfunction "2_COM2") (pintype "bidirectional"))
      (node (ref "U2") (pin "31") (pinfunction "~{DTR}_31") (pintype "bidirectional"))
    )
    (net (code "289") (name "~{FAULT}") (class "Default")
      (node (ref "R38") (pin "1") (pinfunction "1_1") (pintype "passive"))
      (node (ref "R40") (pin "1") (pinfunction "1_1") (pintype "passive"))
      (node (ref "U10") (pin "6") (pinfunction "~{FAULT}_6") (pintype "bidirectional"))
    )
    (net (code "290") (name "~{OCTW}") (class "Default")
      (node (ref "R37") (pin "1") (pinfunction "1_1") (pintype "passive"))
      (node (ref "R42") (pin "2") (pinfunction "2_2") (pintype "passive"))
      (node (ref "U10") (pin "5") (pinfunction "~{OCTW}_5") (pintype "bidirectional"))
    )
    (net (code "291") (name "~{PICCOLO_RESET}") (class "Default")
      (node (ref "C81") (pin "1") (pinfunction "1_1") (pintype "passive"))
      (node (ref "R78") (pin "1") (pinfunction "1_1") (pintype "passive"))
      (node (ref "S1") (pin "2") (pinfunction "4_2") (pintype "passive"))
      (node (ref "S1") (pin "4") (pinfunction "3_4") (pintype "passive"))
      (node (ref "U5") (pin "11") (pinfunction "~{XRS}_11") (pintype "bidirectional"))
    )
    (net (code "292") (name "~{RTS_FTDI}") (class "Default")
      (node (ref "S2") (pin "COM1") (pinfunction "2_COM1") (pintype "bidirectional"))
      (node (ref "U2") (pin "32") (pinfunction "~{RTS}_32") (pintype "bidirectional"))
    )
    (net (code "293") (name "~{SPI_CS}") (class "Default")
      (node (ref "R117") (pin "2") (pinfunction "2_2") (pintype "passive"))
      (node (ref "U1") (pin "19") (pinfunction "C2_19") (pintype "bidirectional"))
    )
  )
)
